# WMHS_MIT_Invy_Circuit_Board.net
KiCad netlist of a schematic drawn in EAGLE
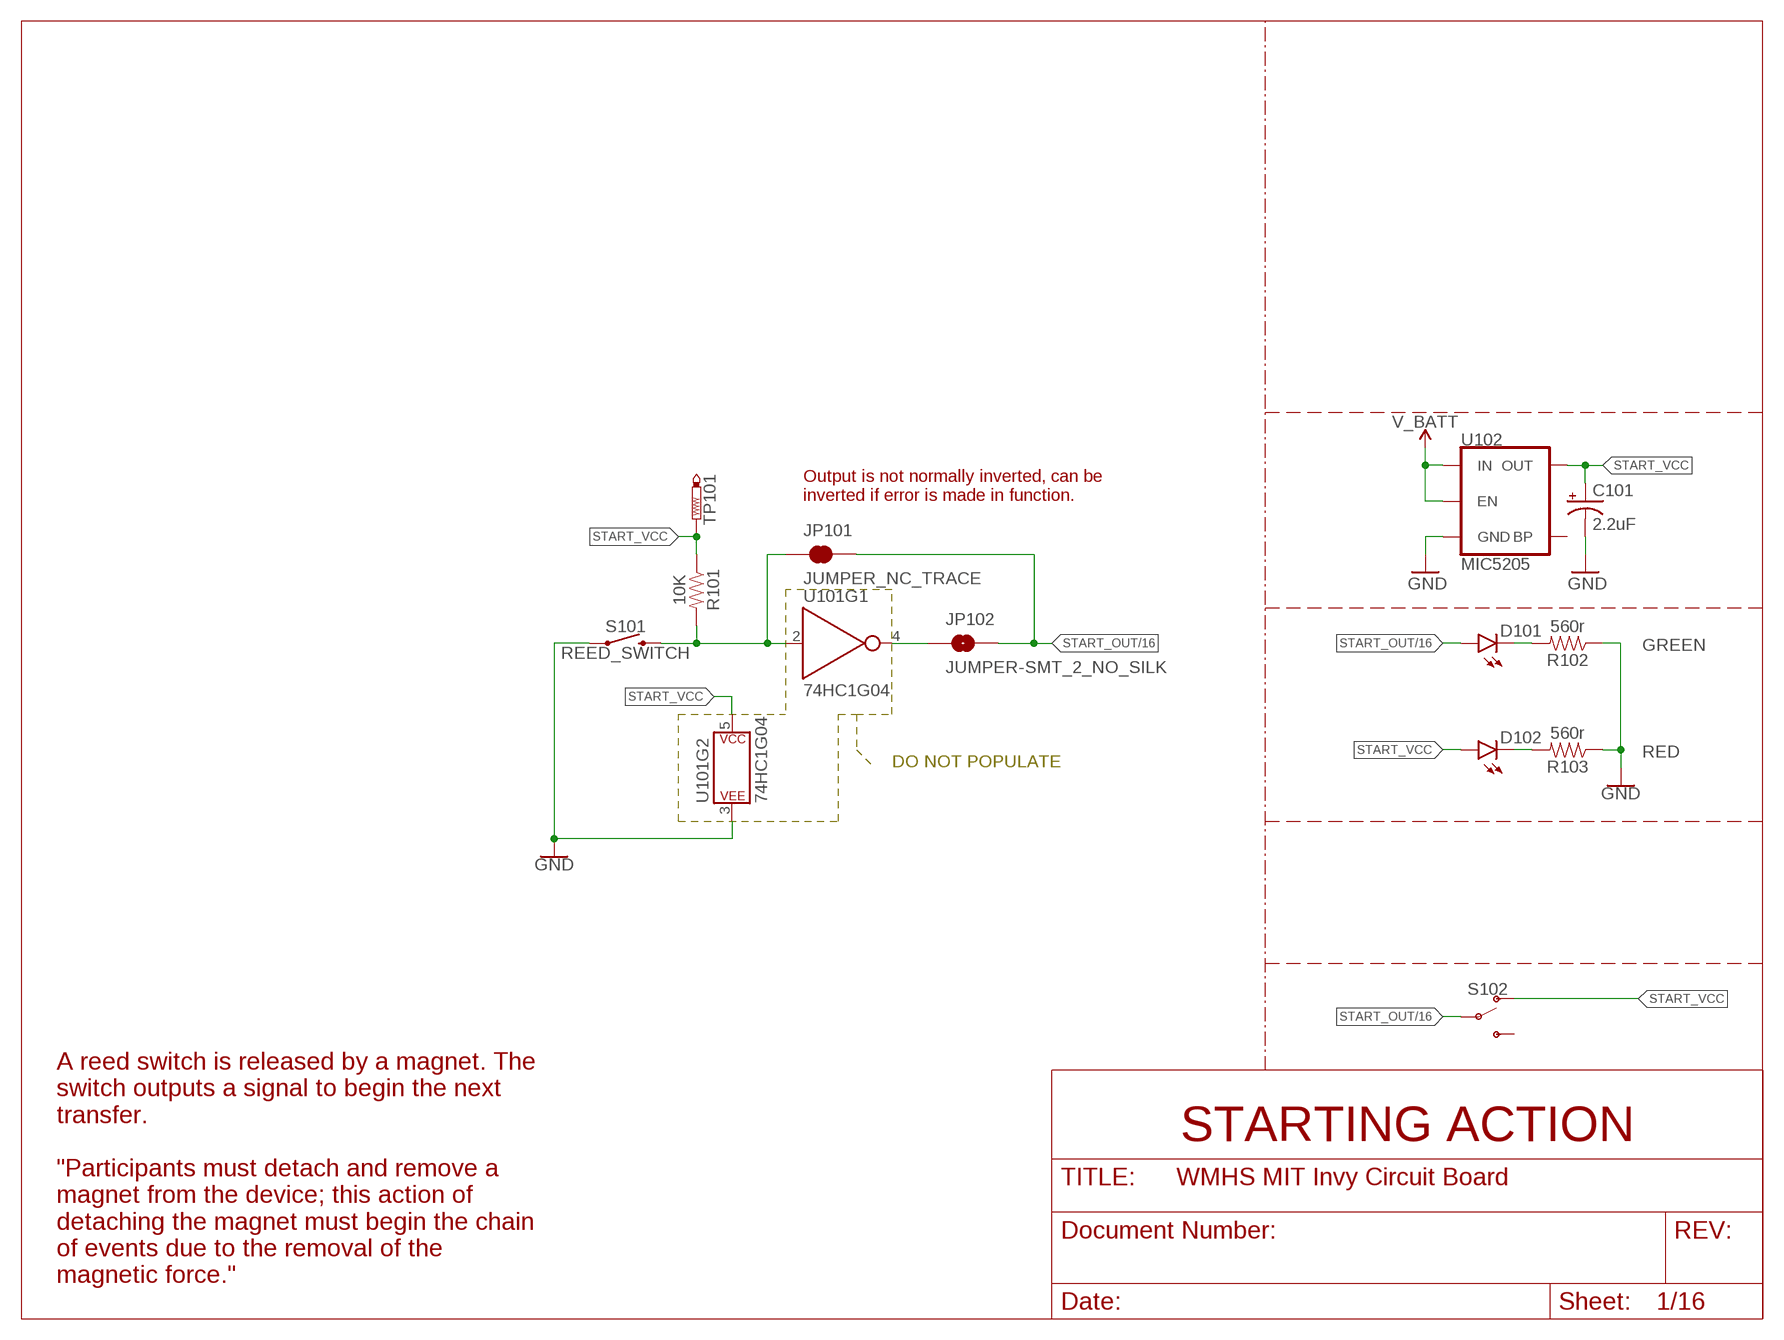
[diagram p0: schematic, sheet 1]
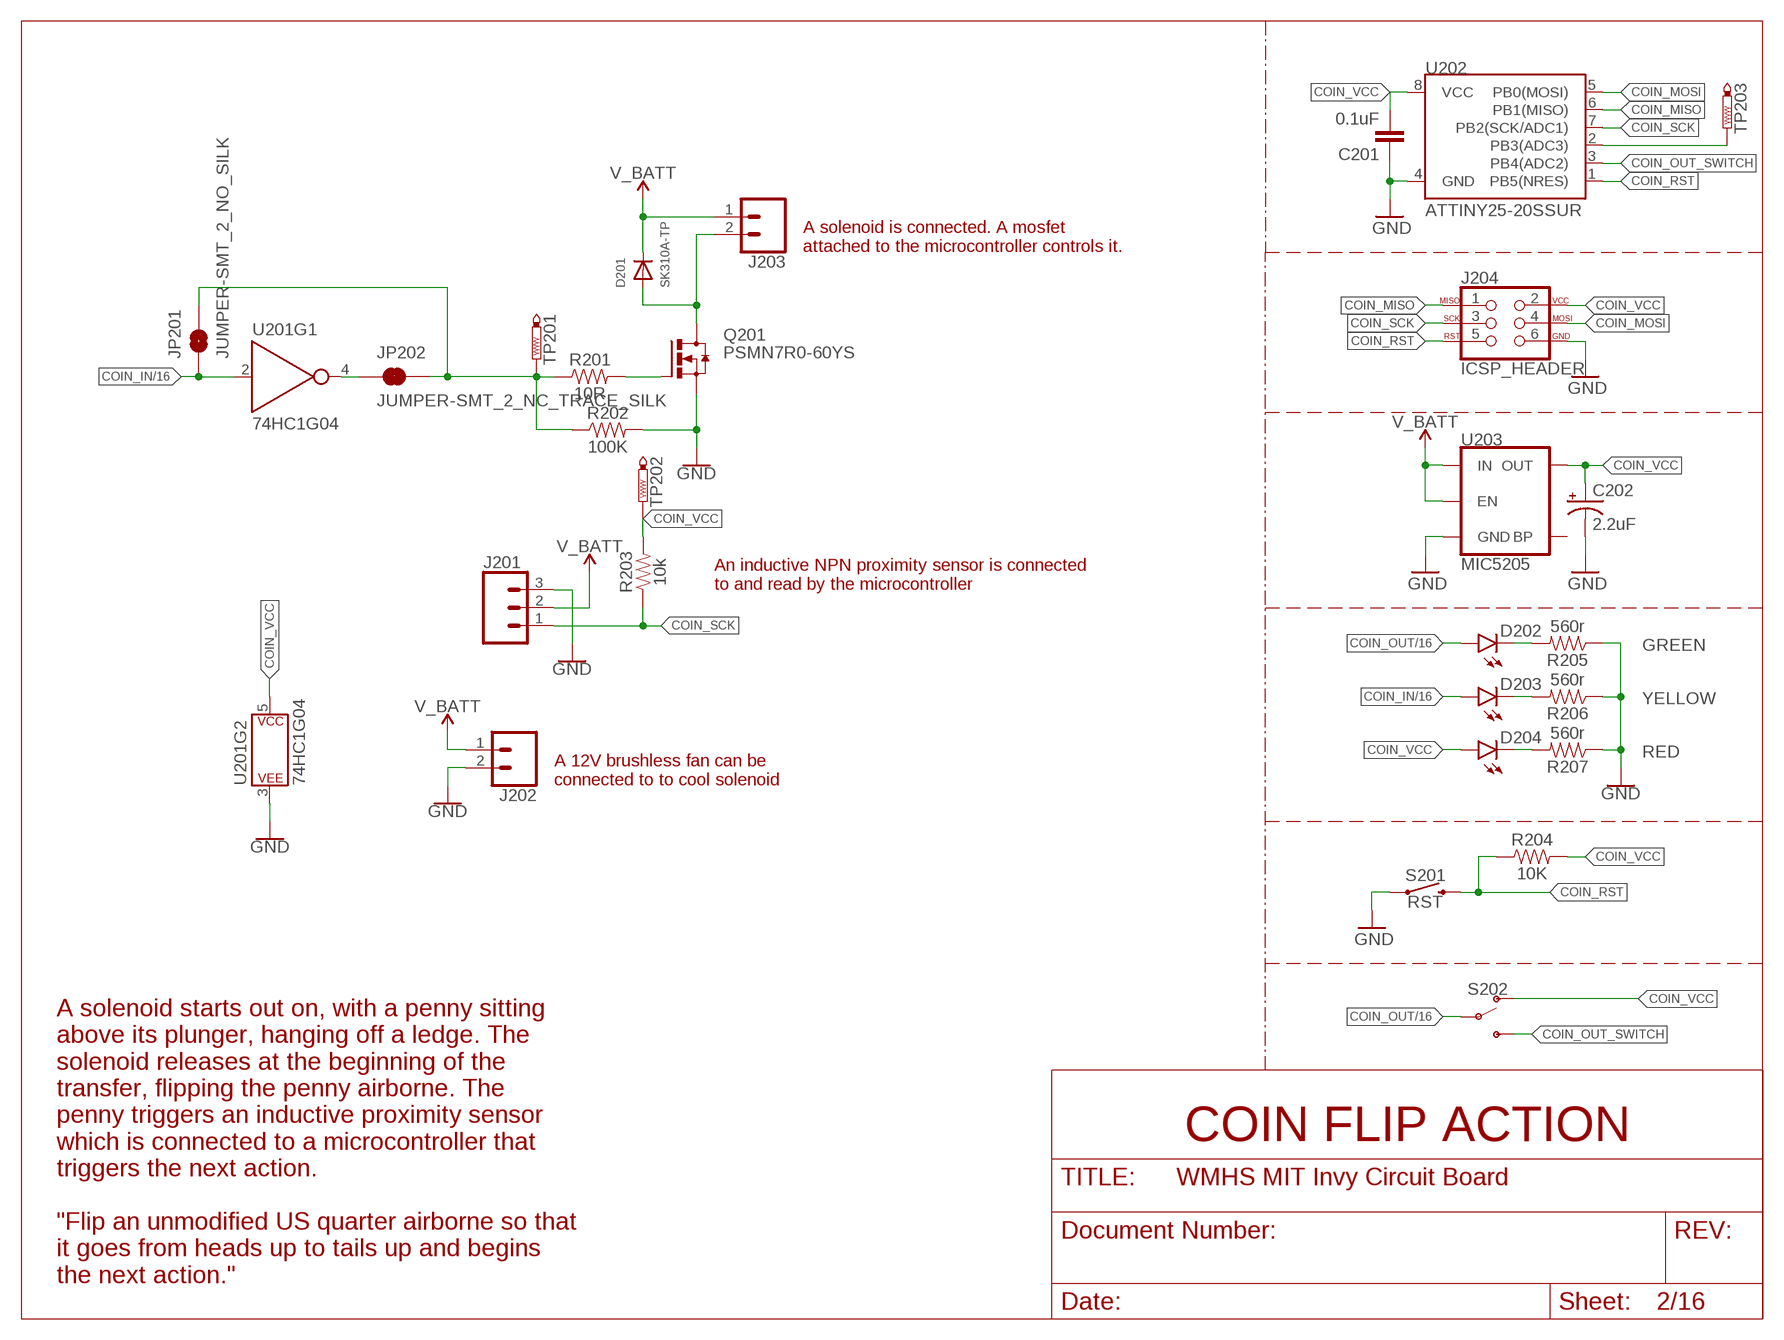
[diagram p1: schematic, sheet 2]
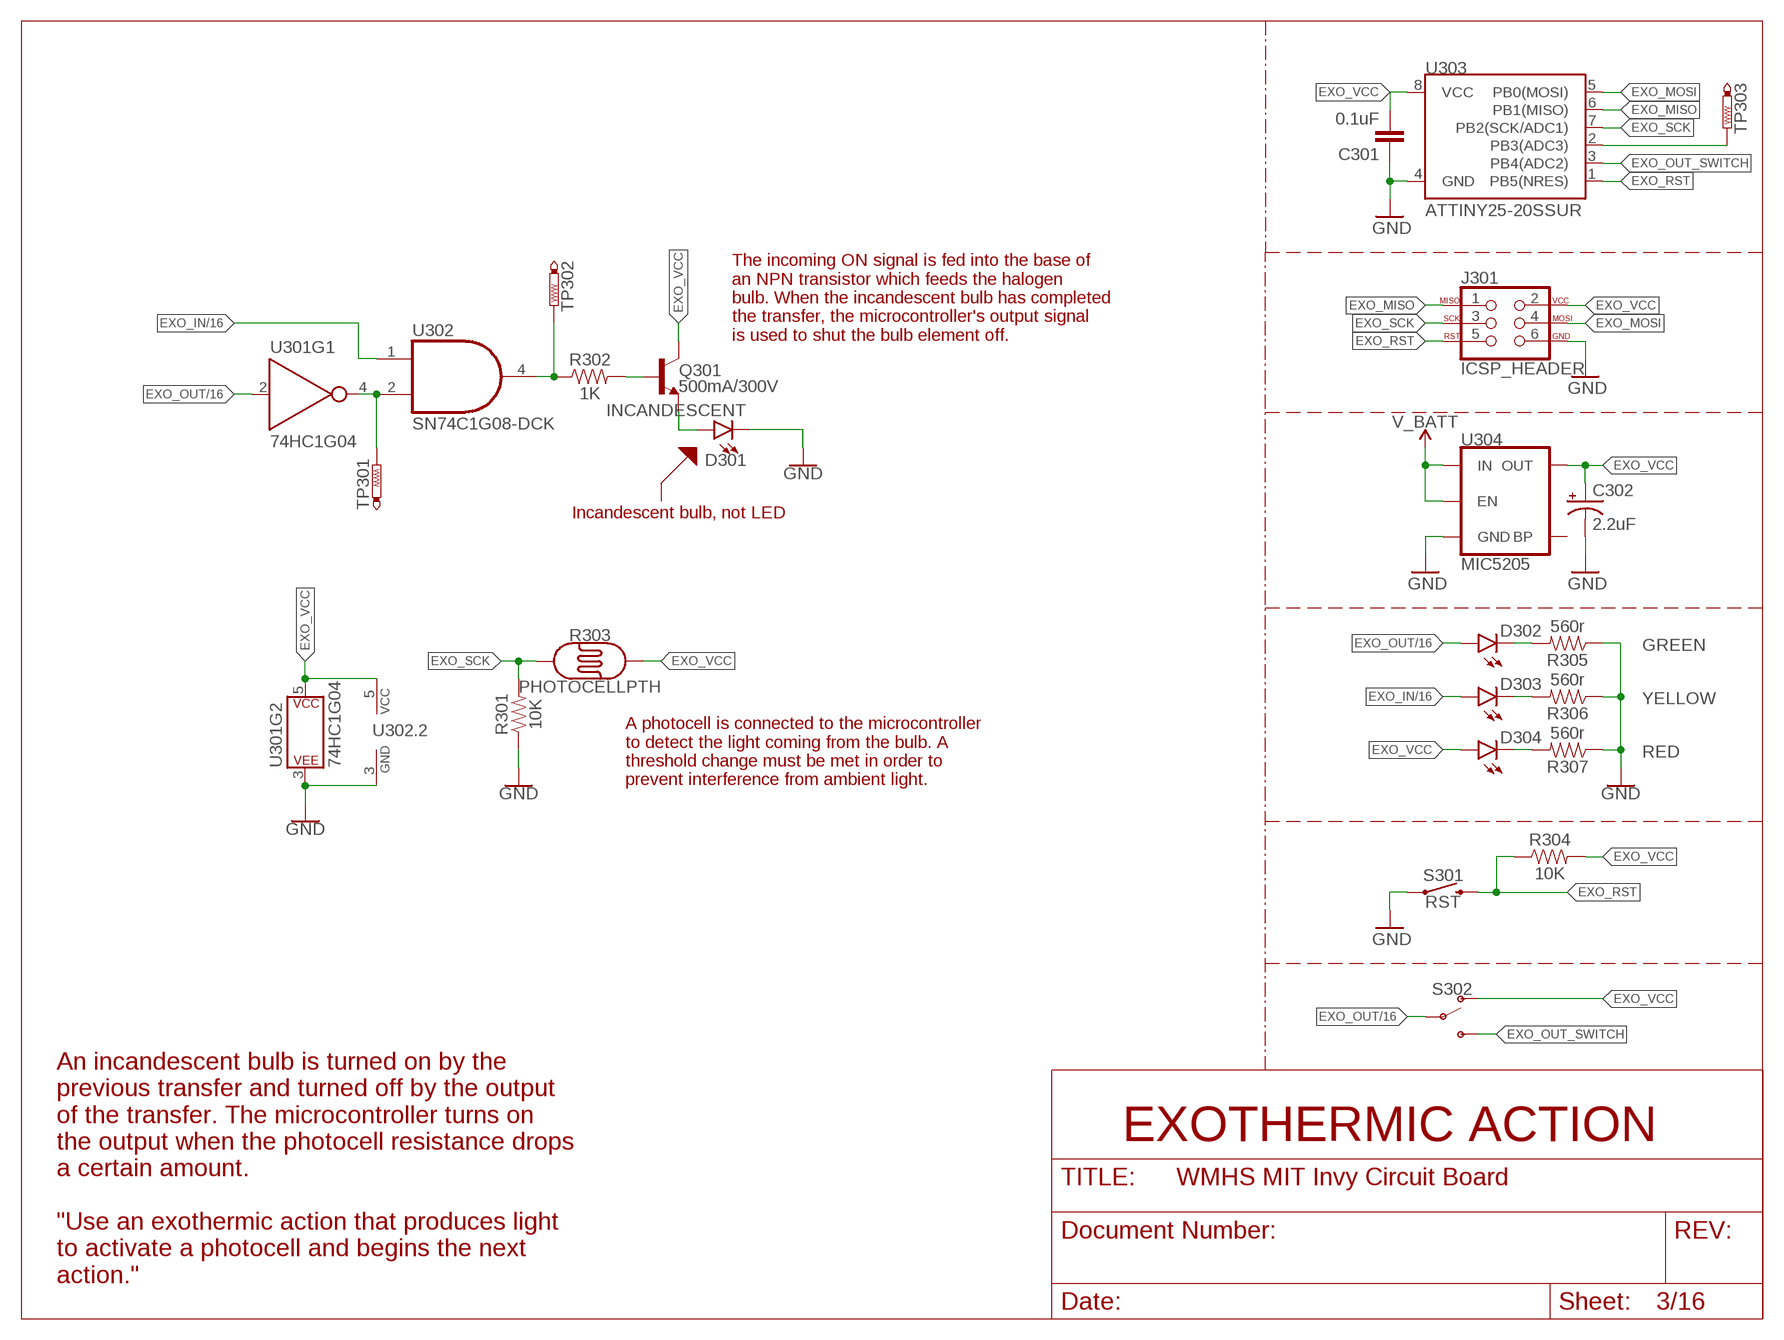
[diagram p2: schematic, sheet 3]
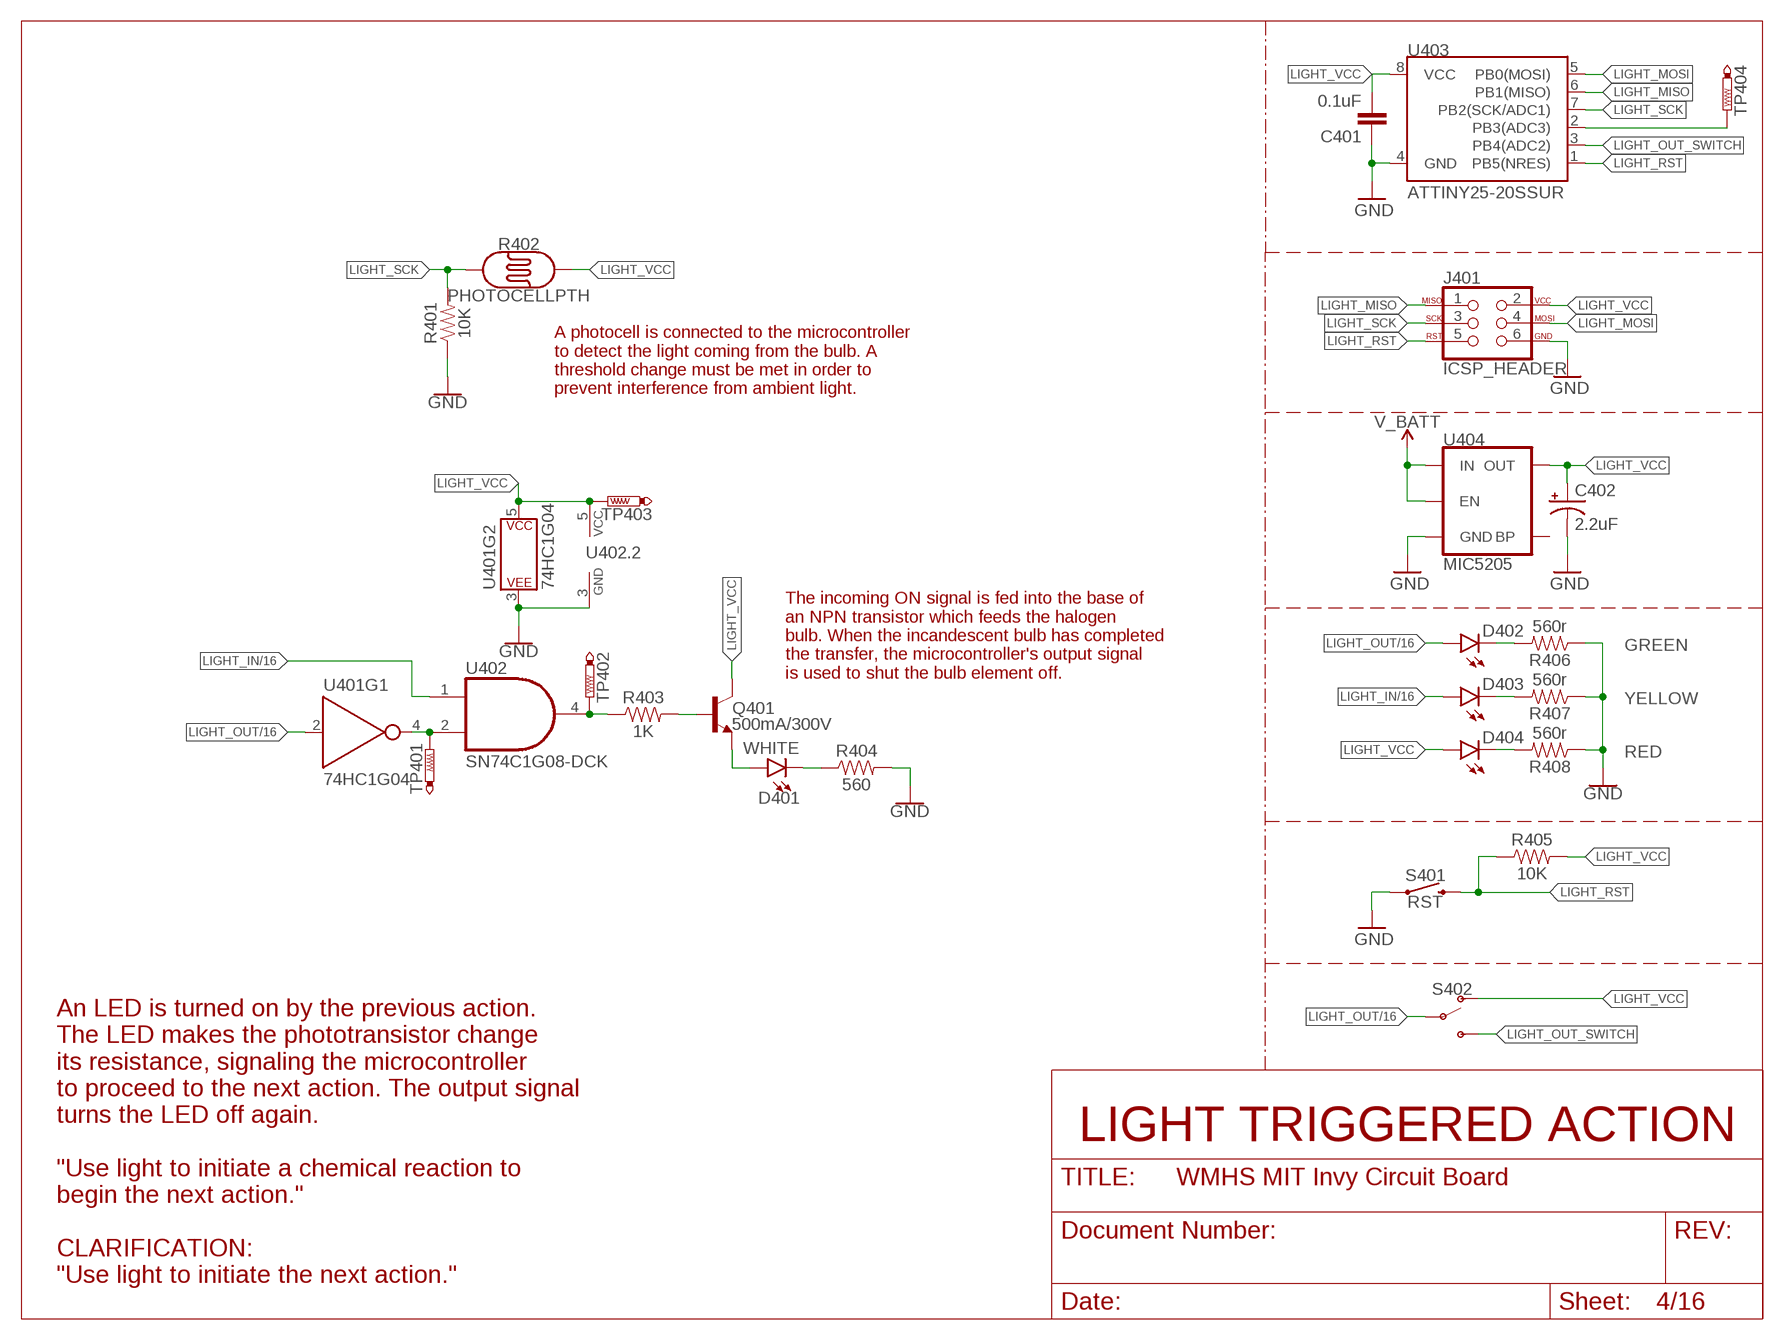
[diagram p3: schematic, sheet 4]
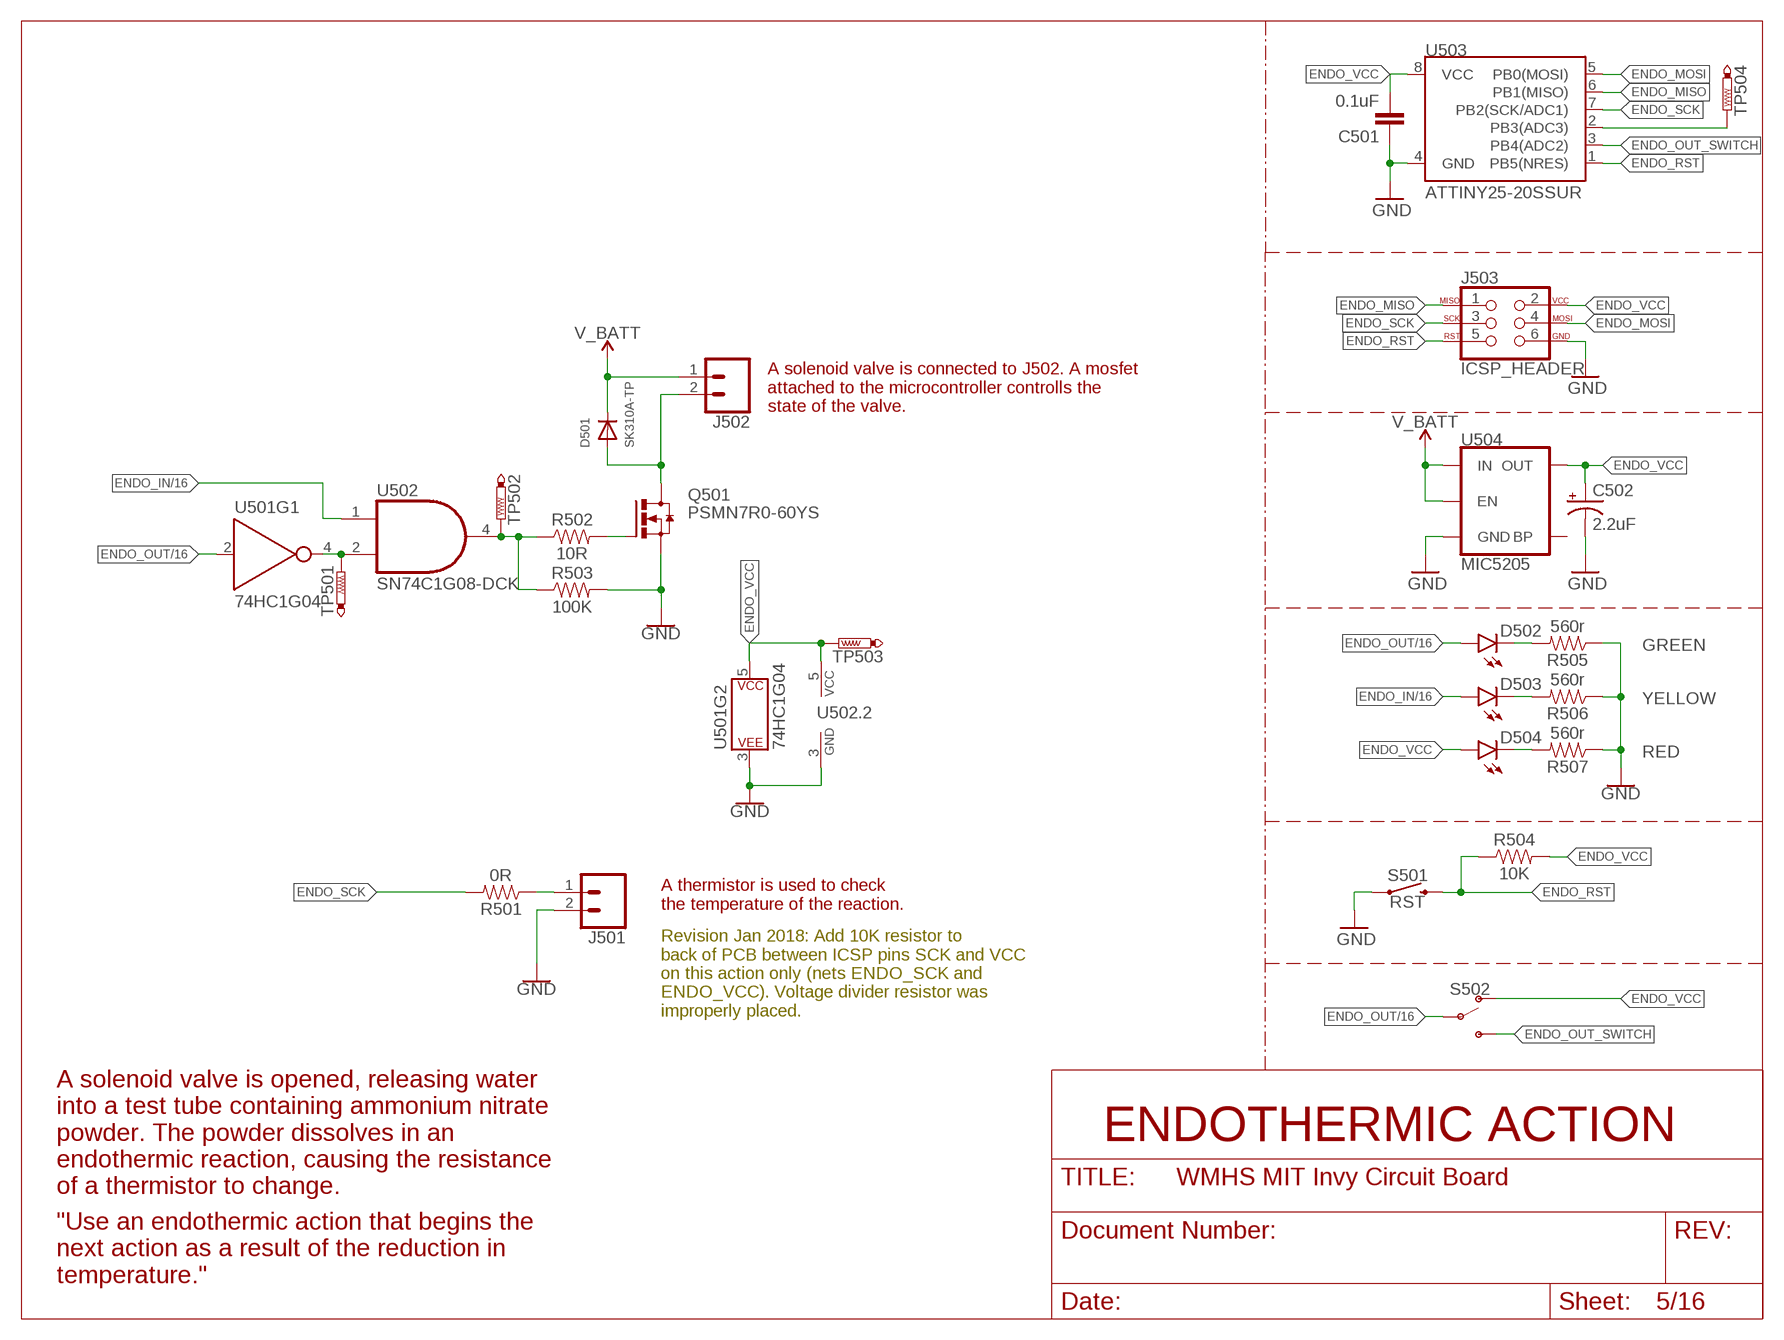
[diagram p4: schematic, sheet 5]
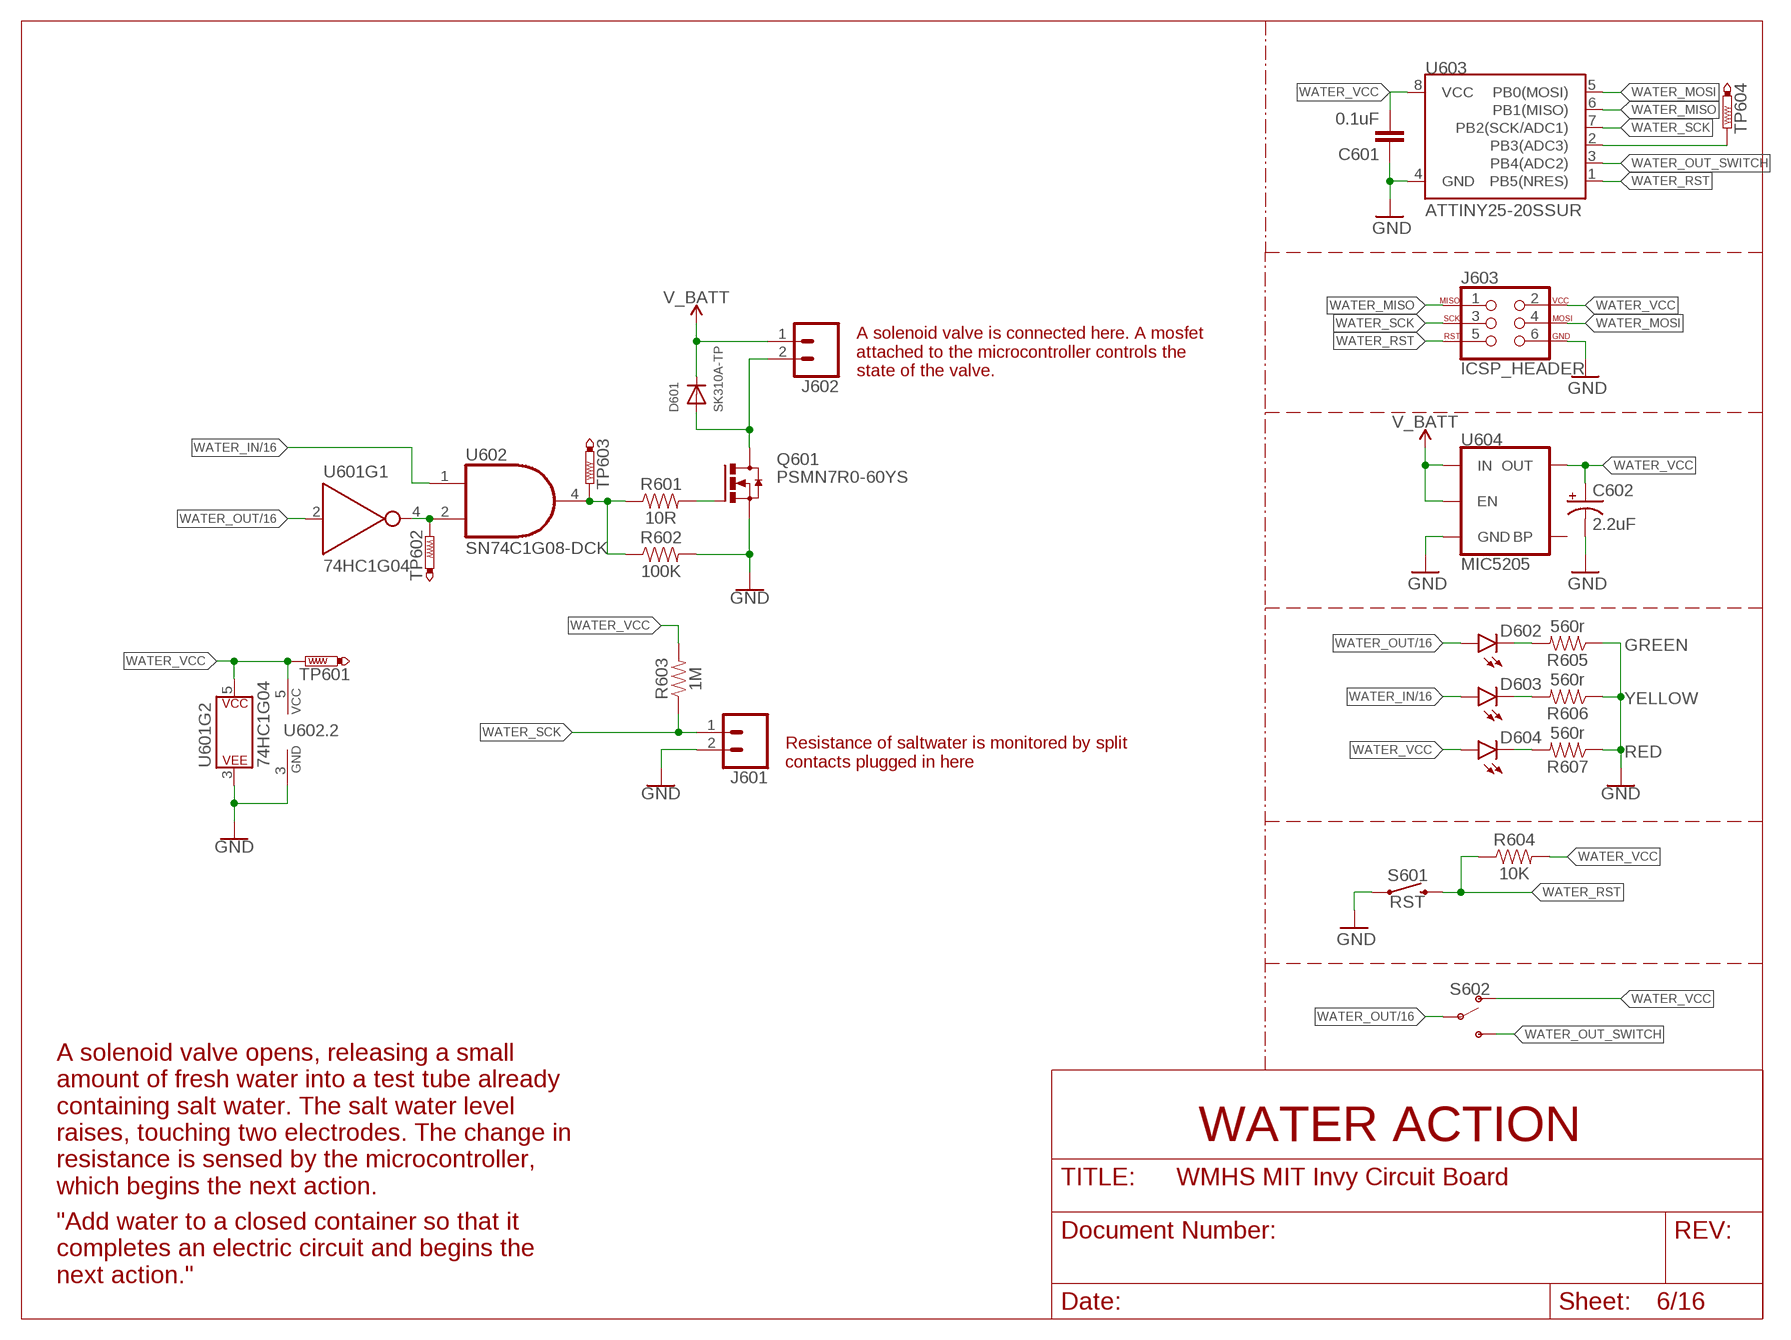
[diagram p5: schematic, sheet 6]
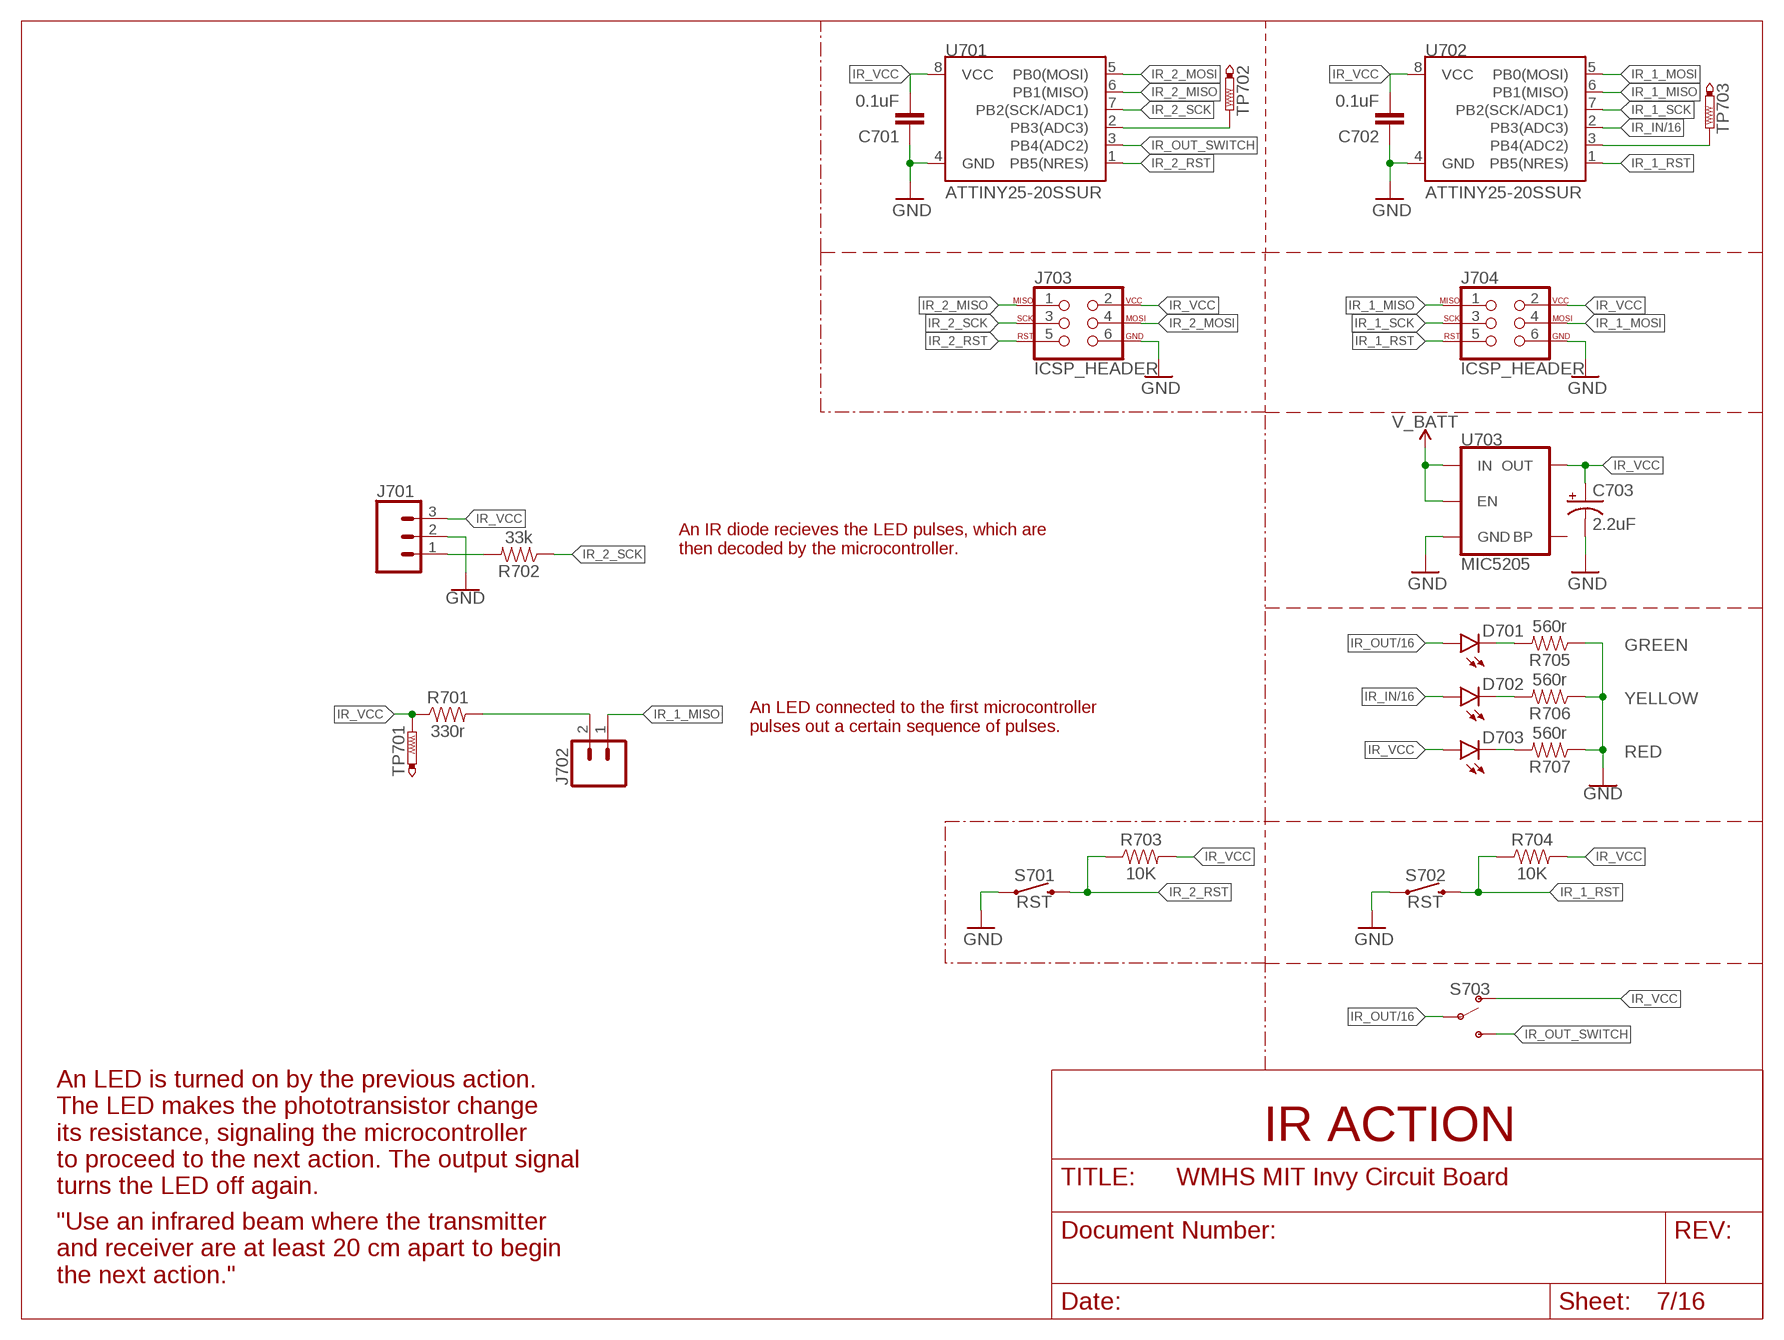
[diagram p6: schematic, sheet 7]
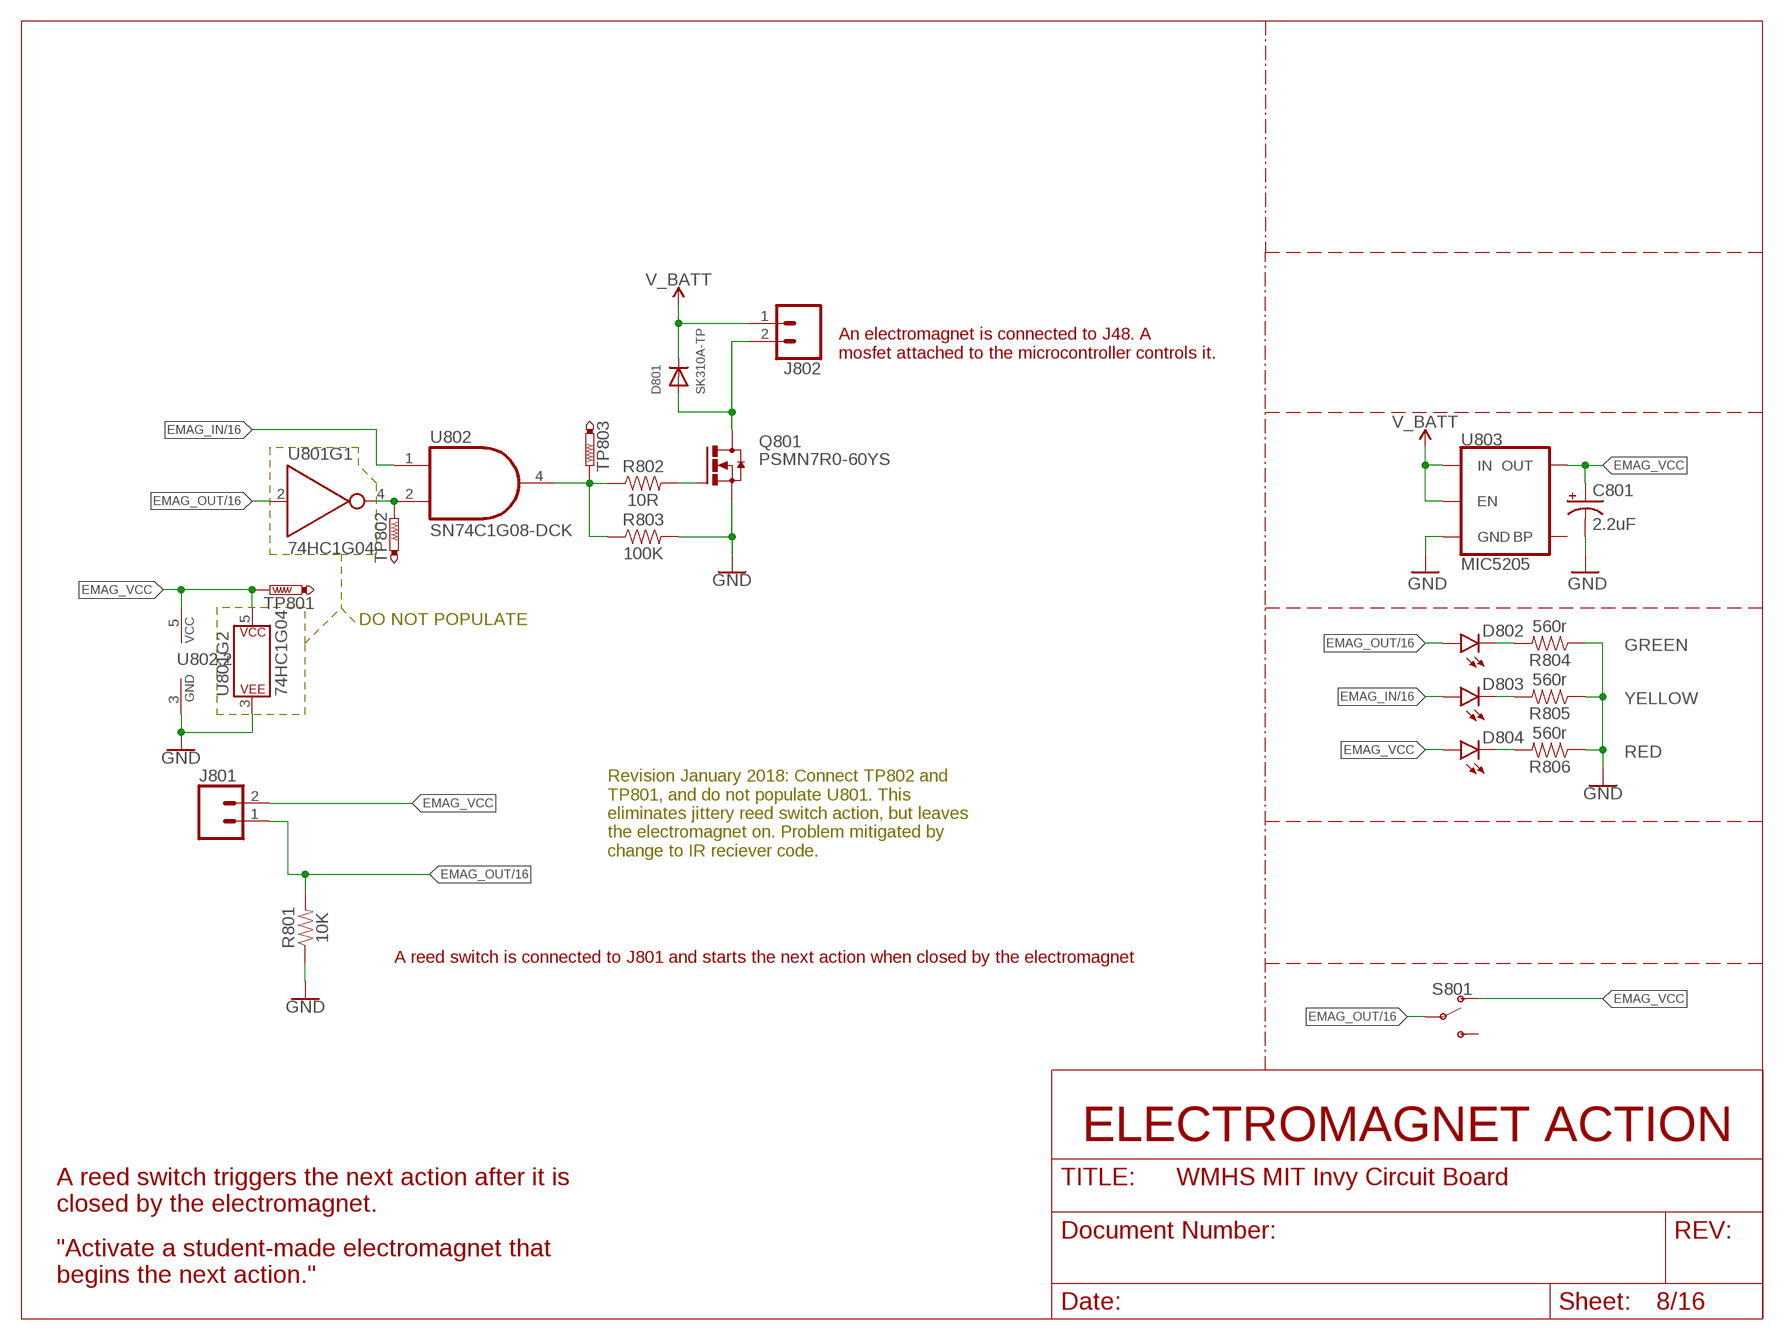
[diagram p7: schematic, sheet 8]
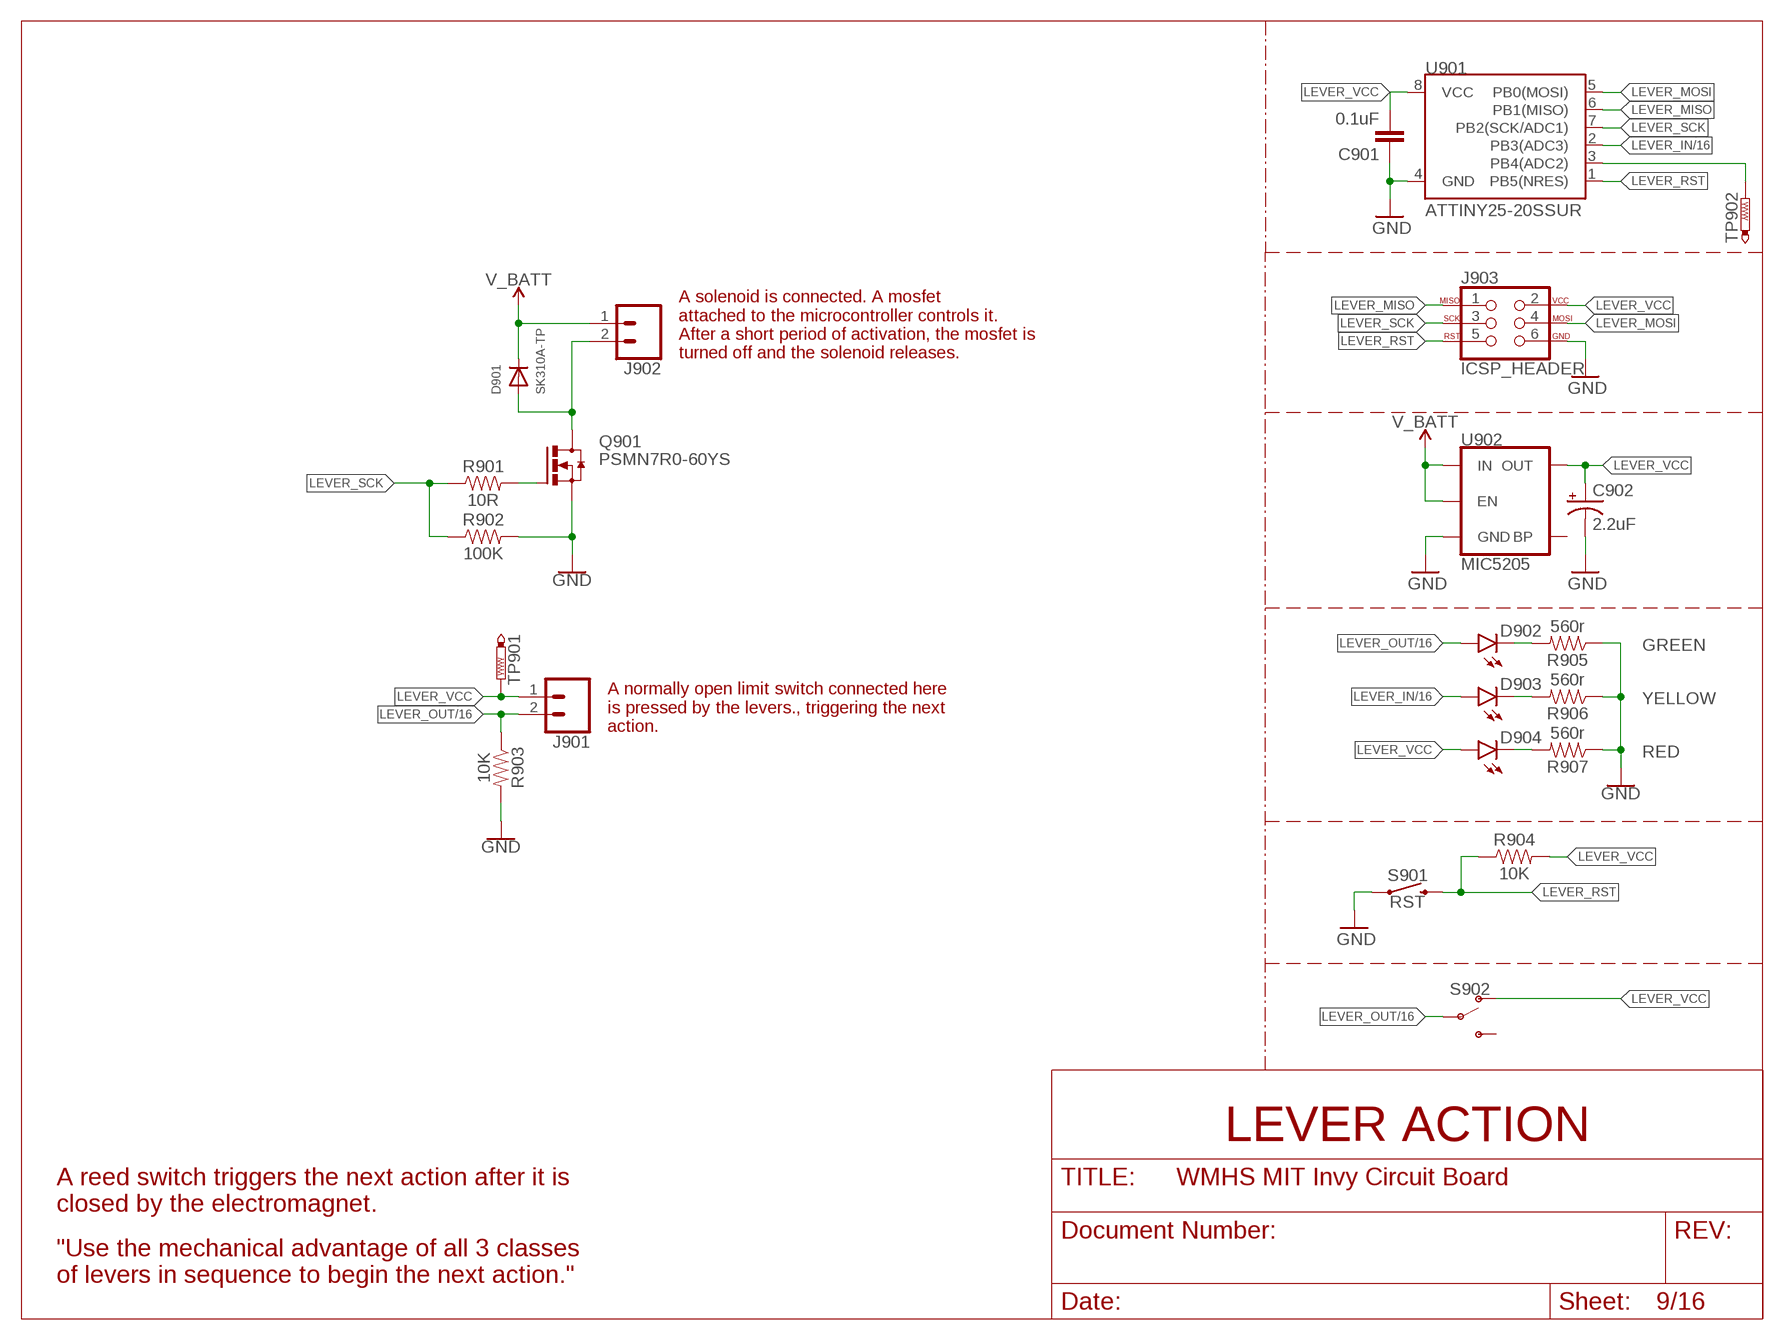
[diagram p8: schematic, sheet 9]
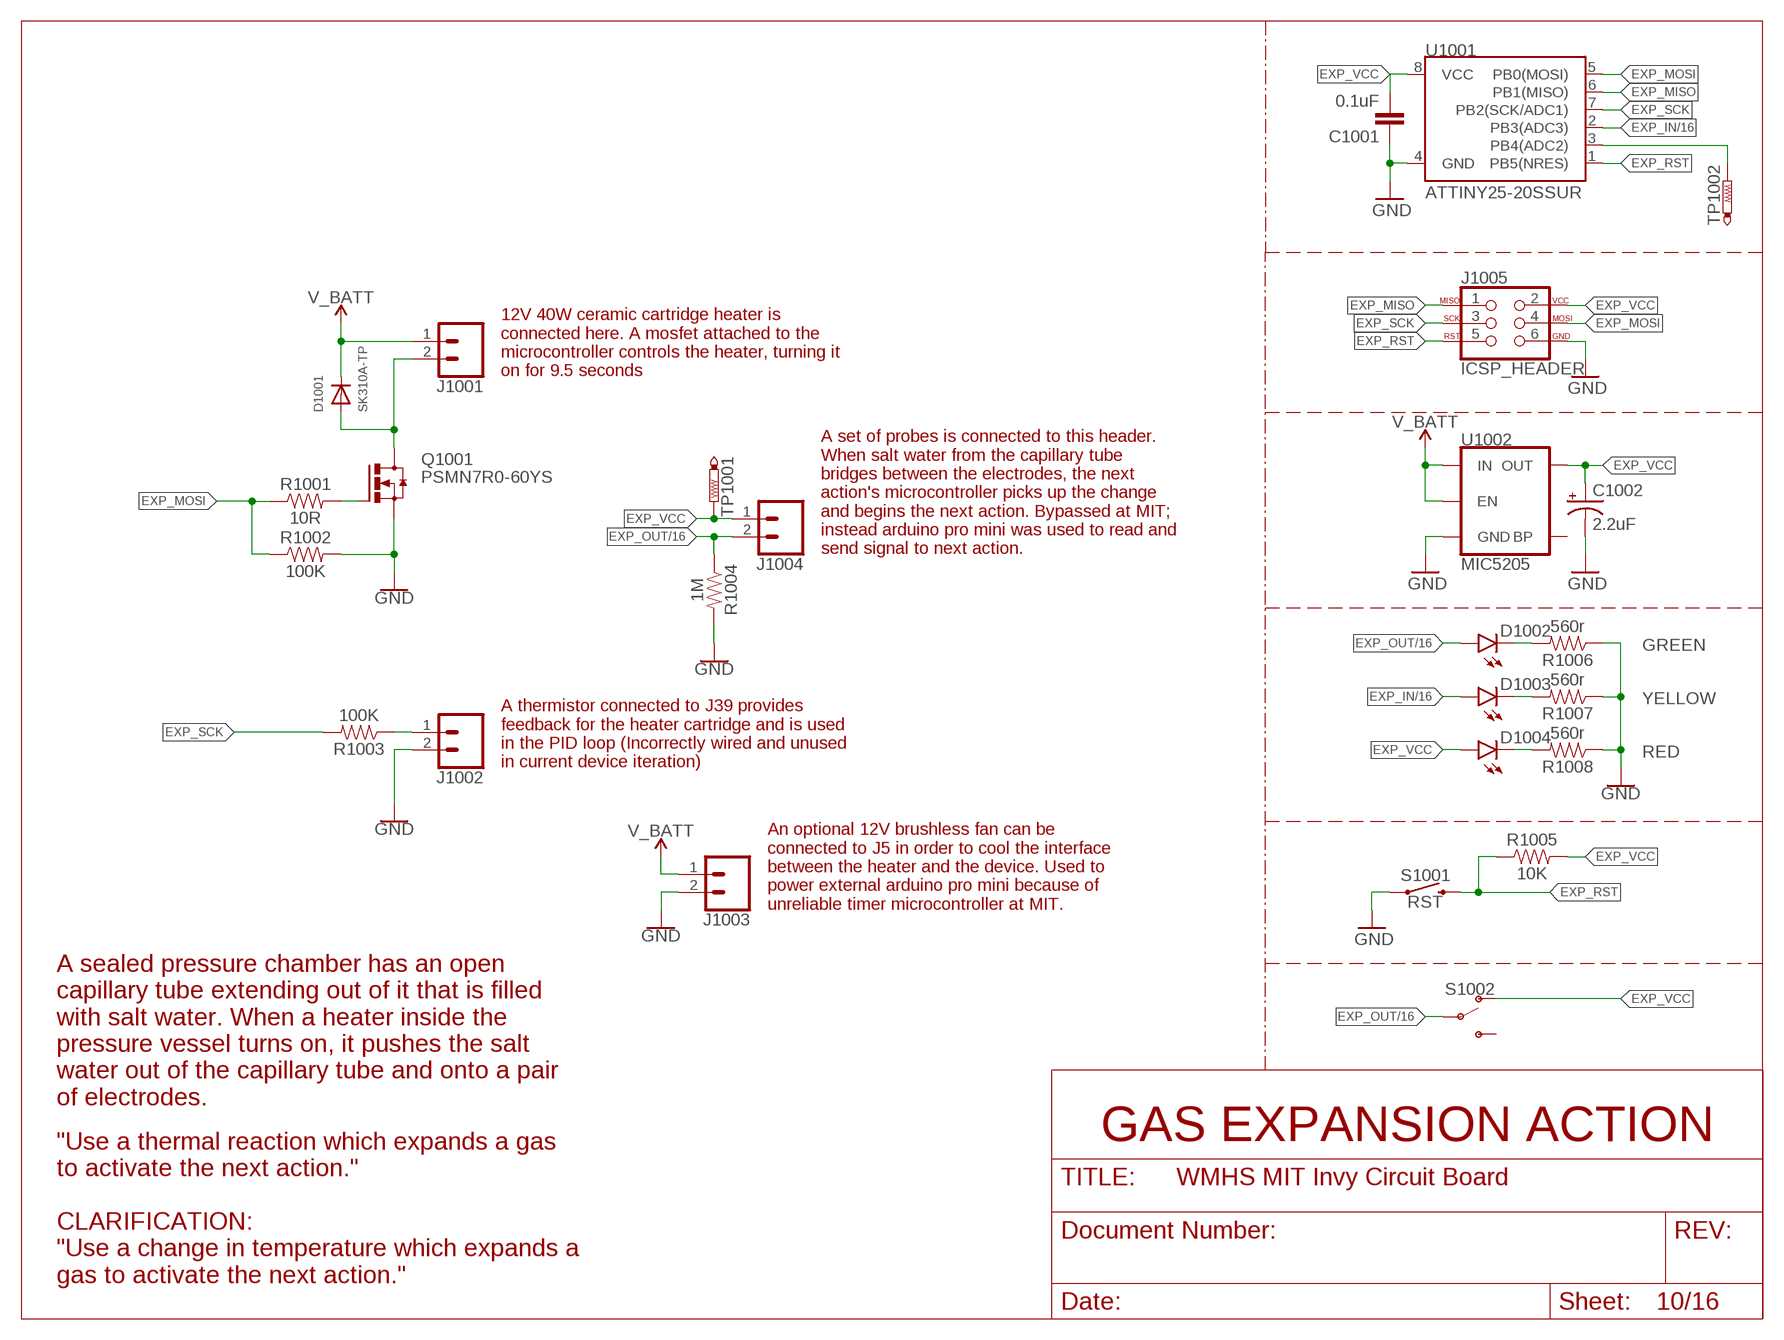
[diagram p9: schematic, sheet 10]
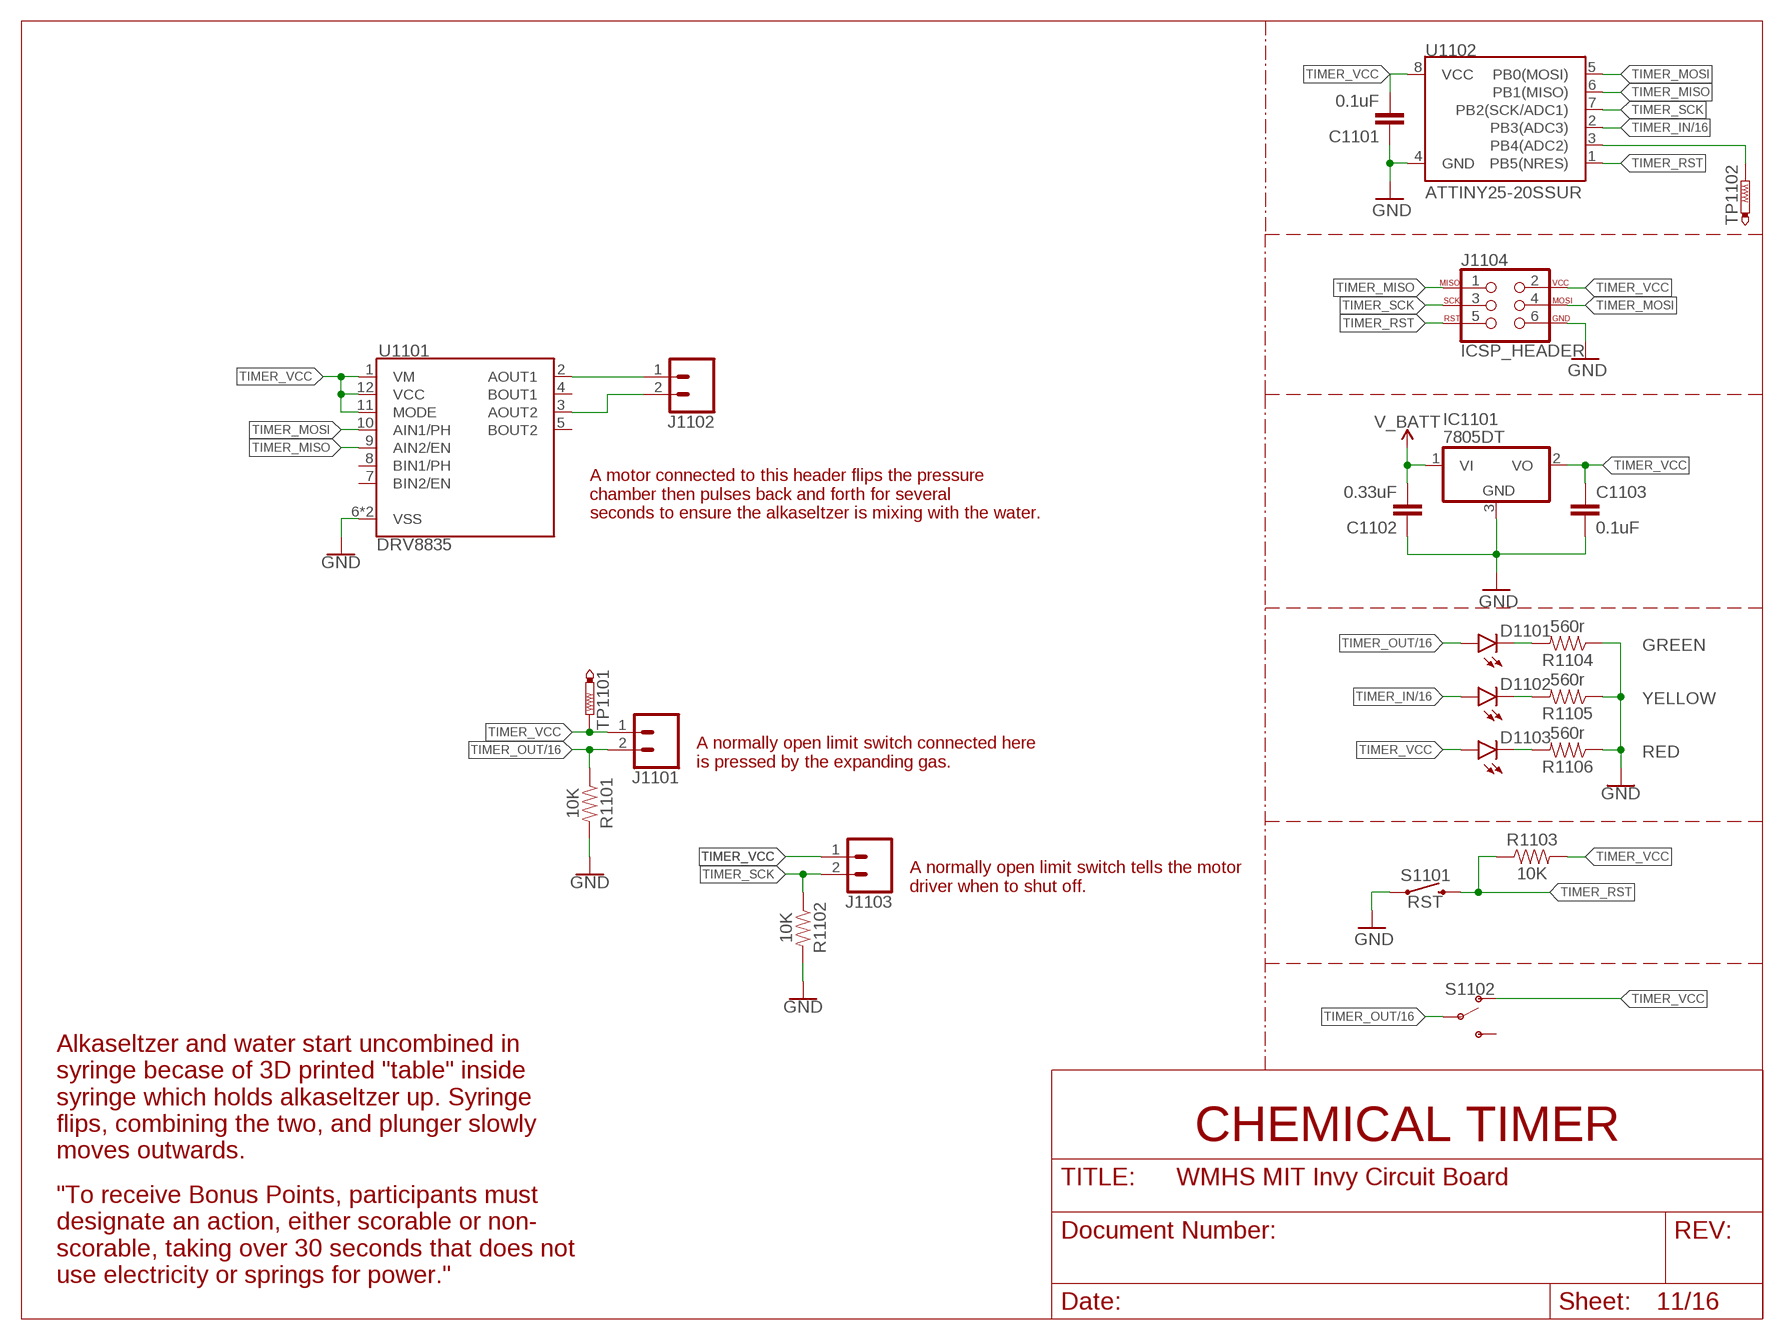
[diagram p10: schematic, sheet 11]
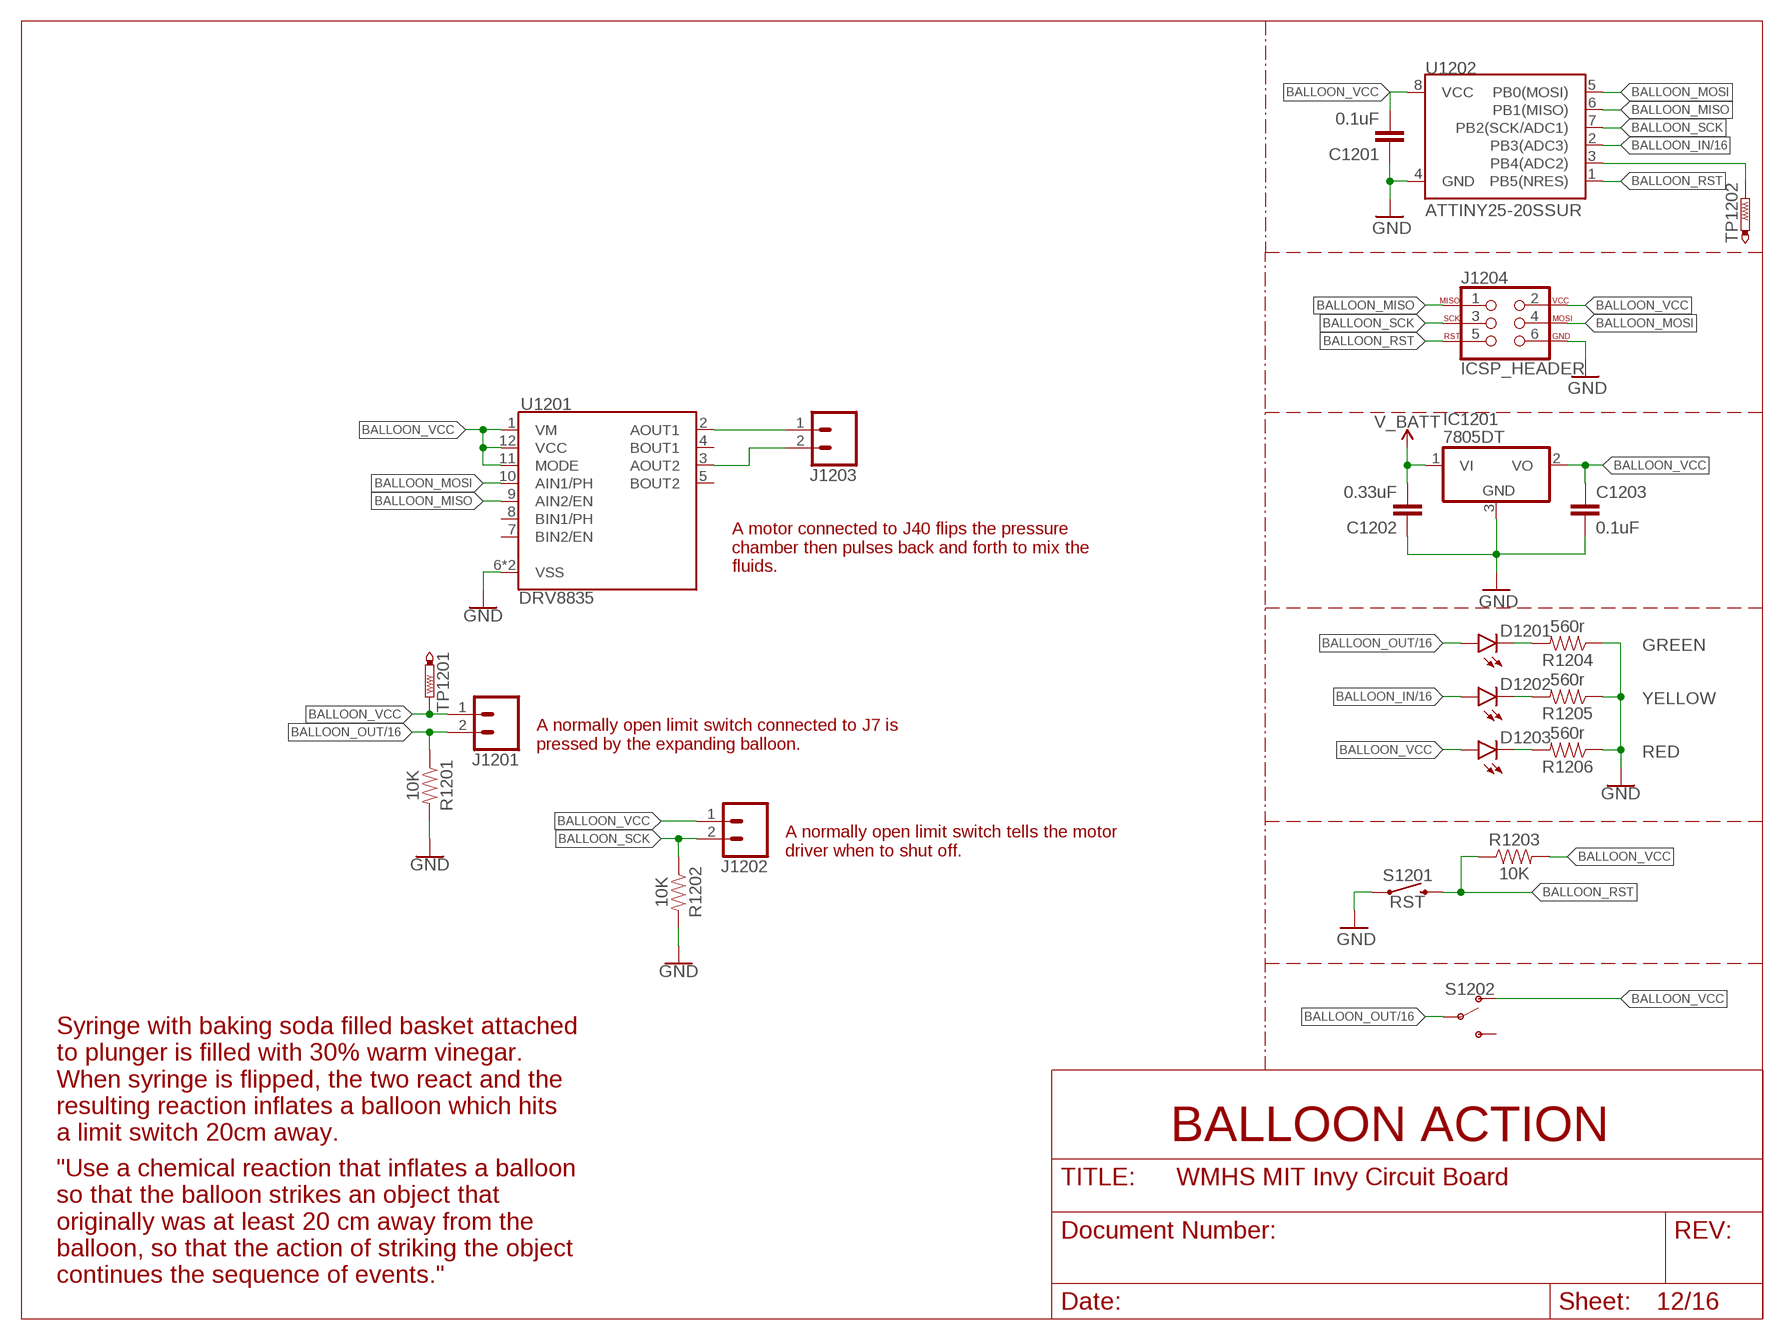
[diagram p11: schematic, sheet 12]
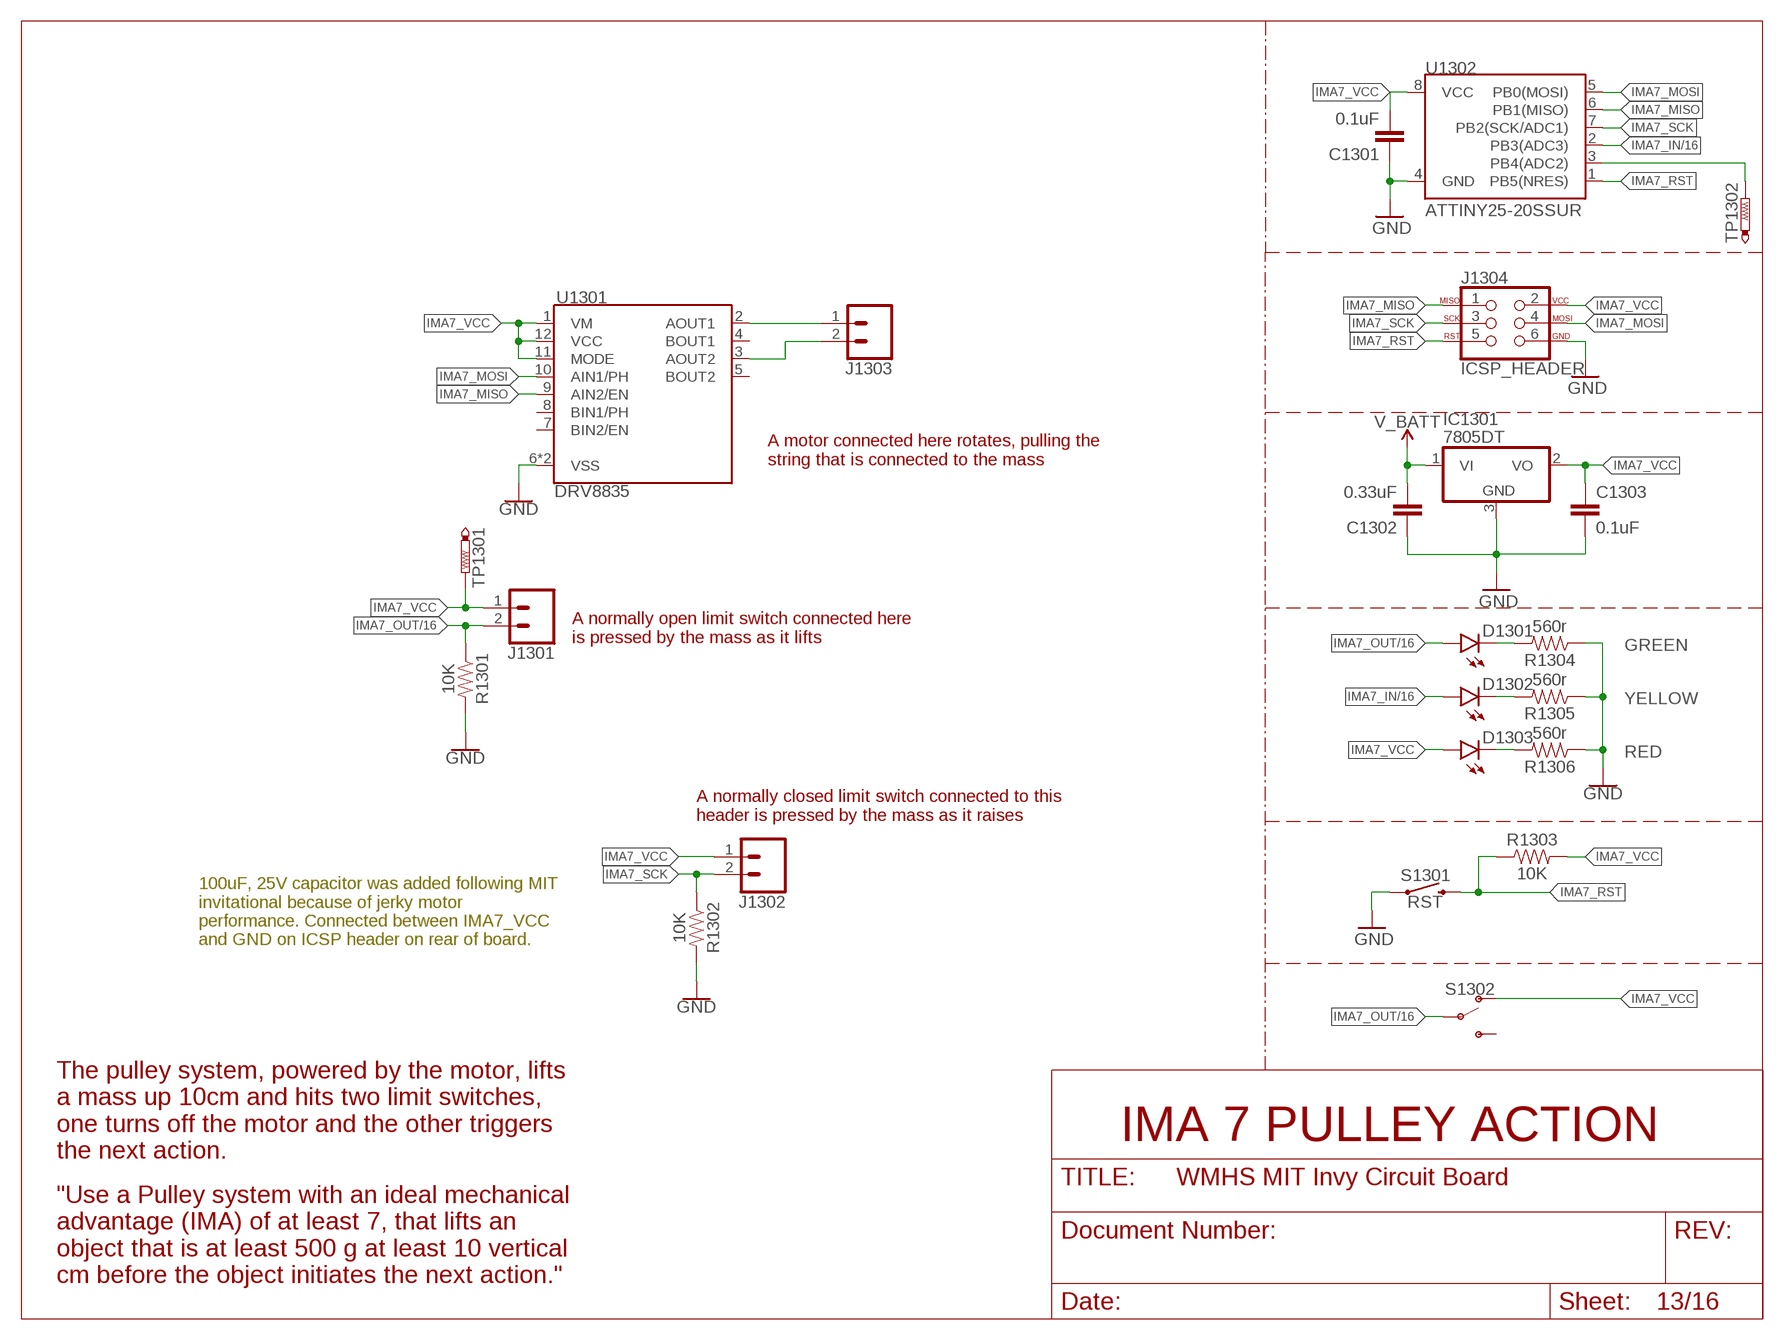
[diagram p12: schematic, sheet 13]
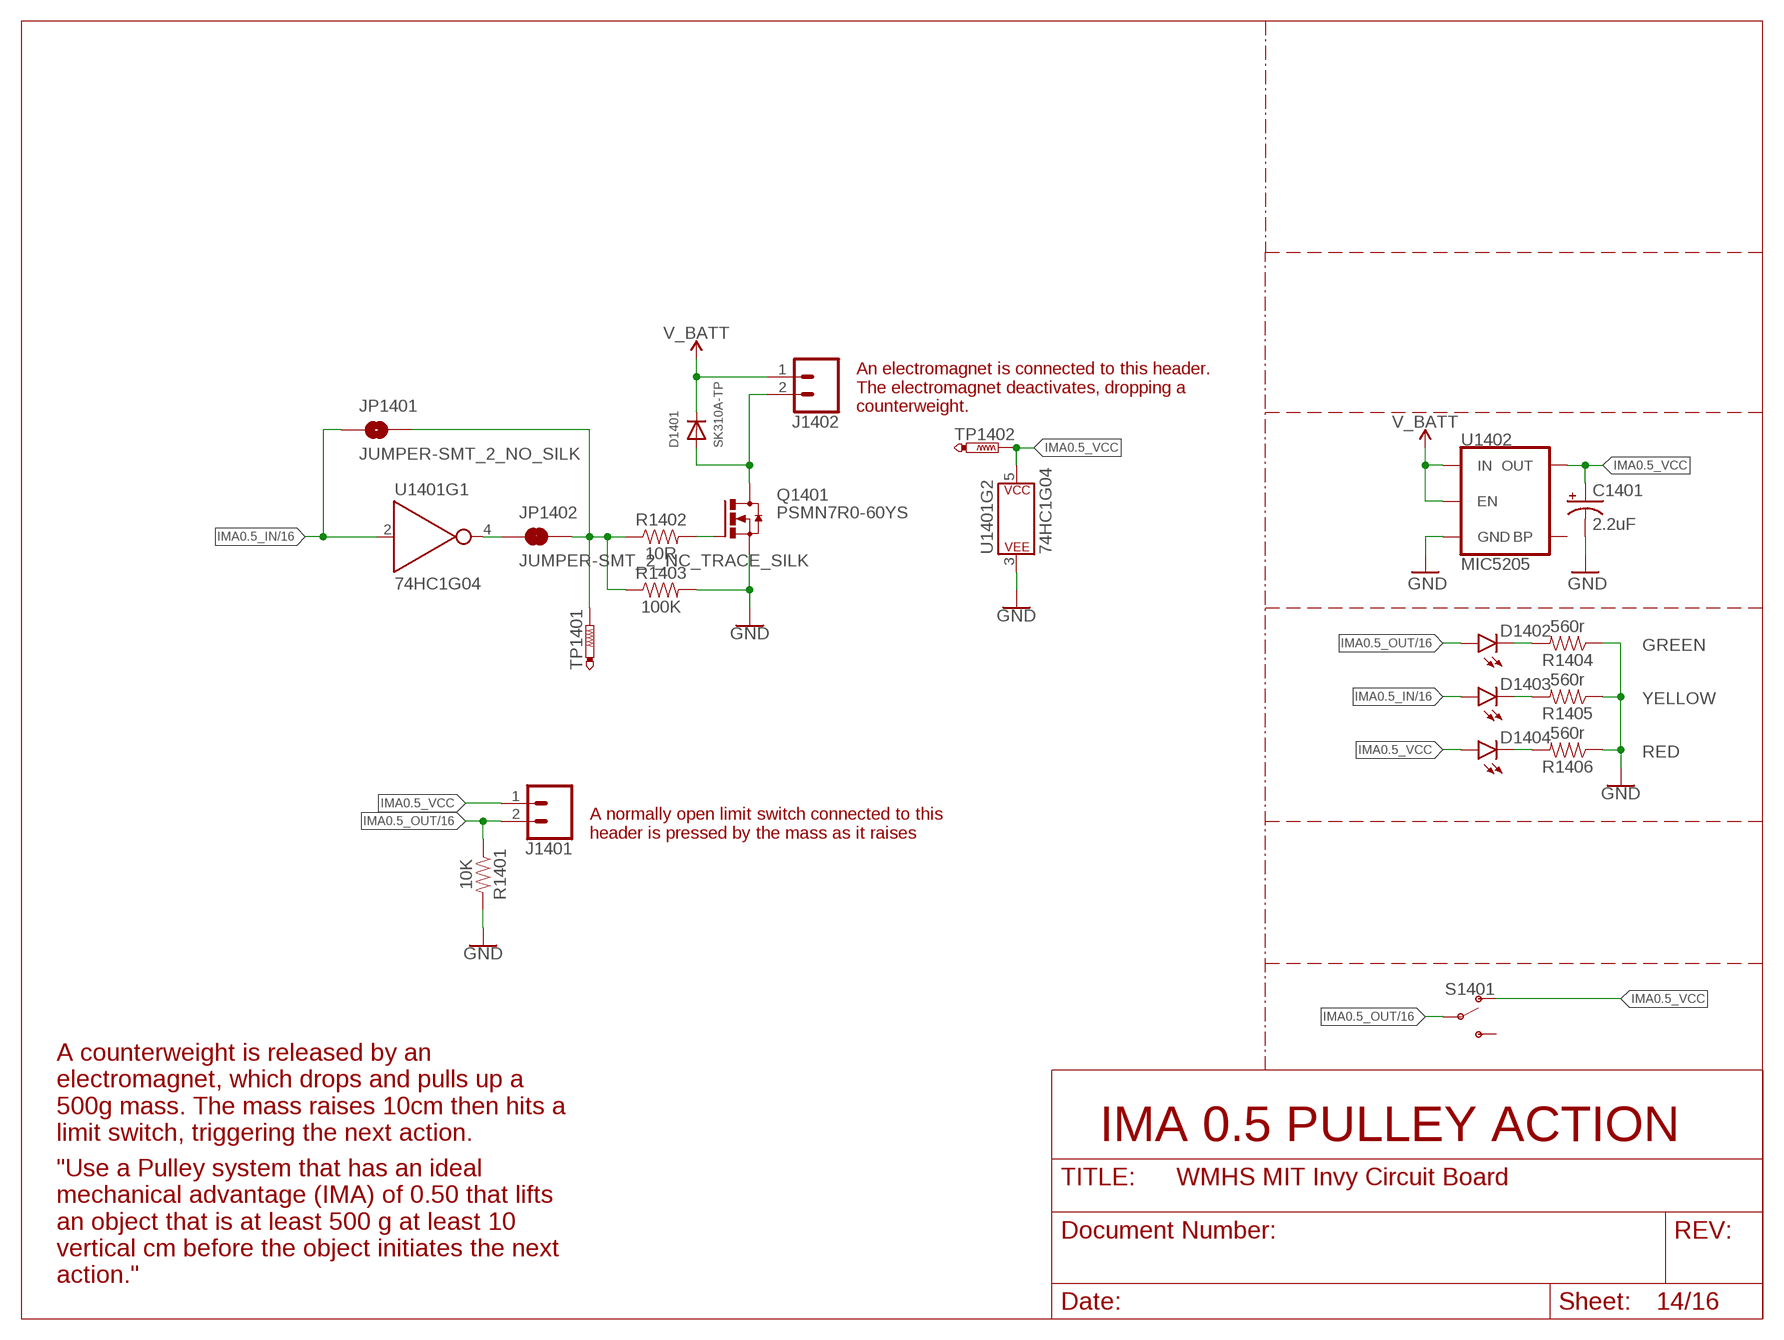
[diagram p13: schematic, sheet 14]
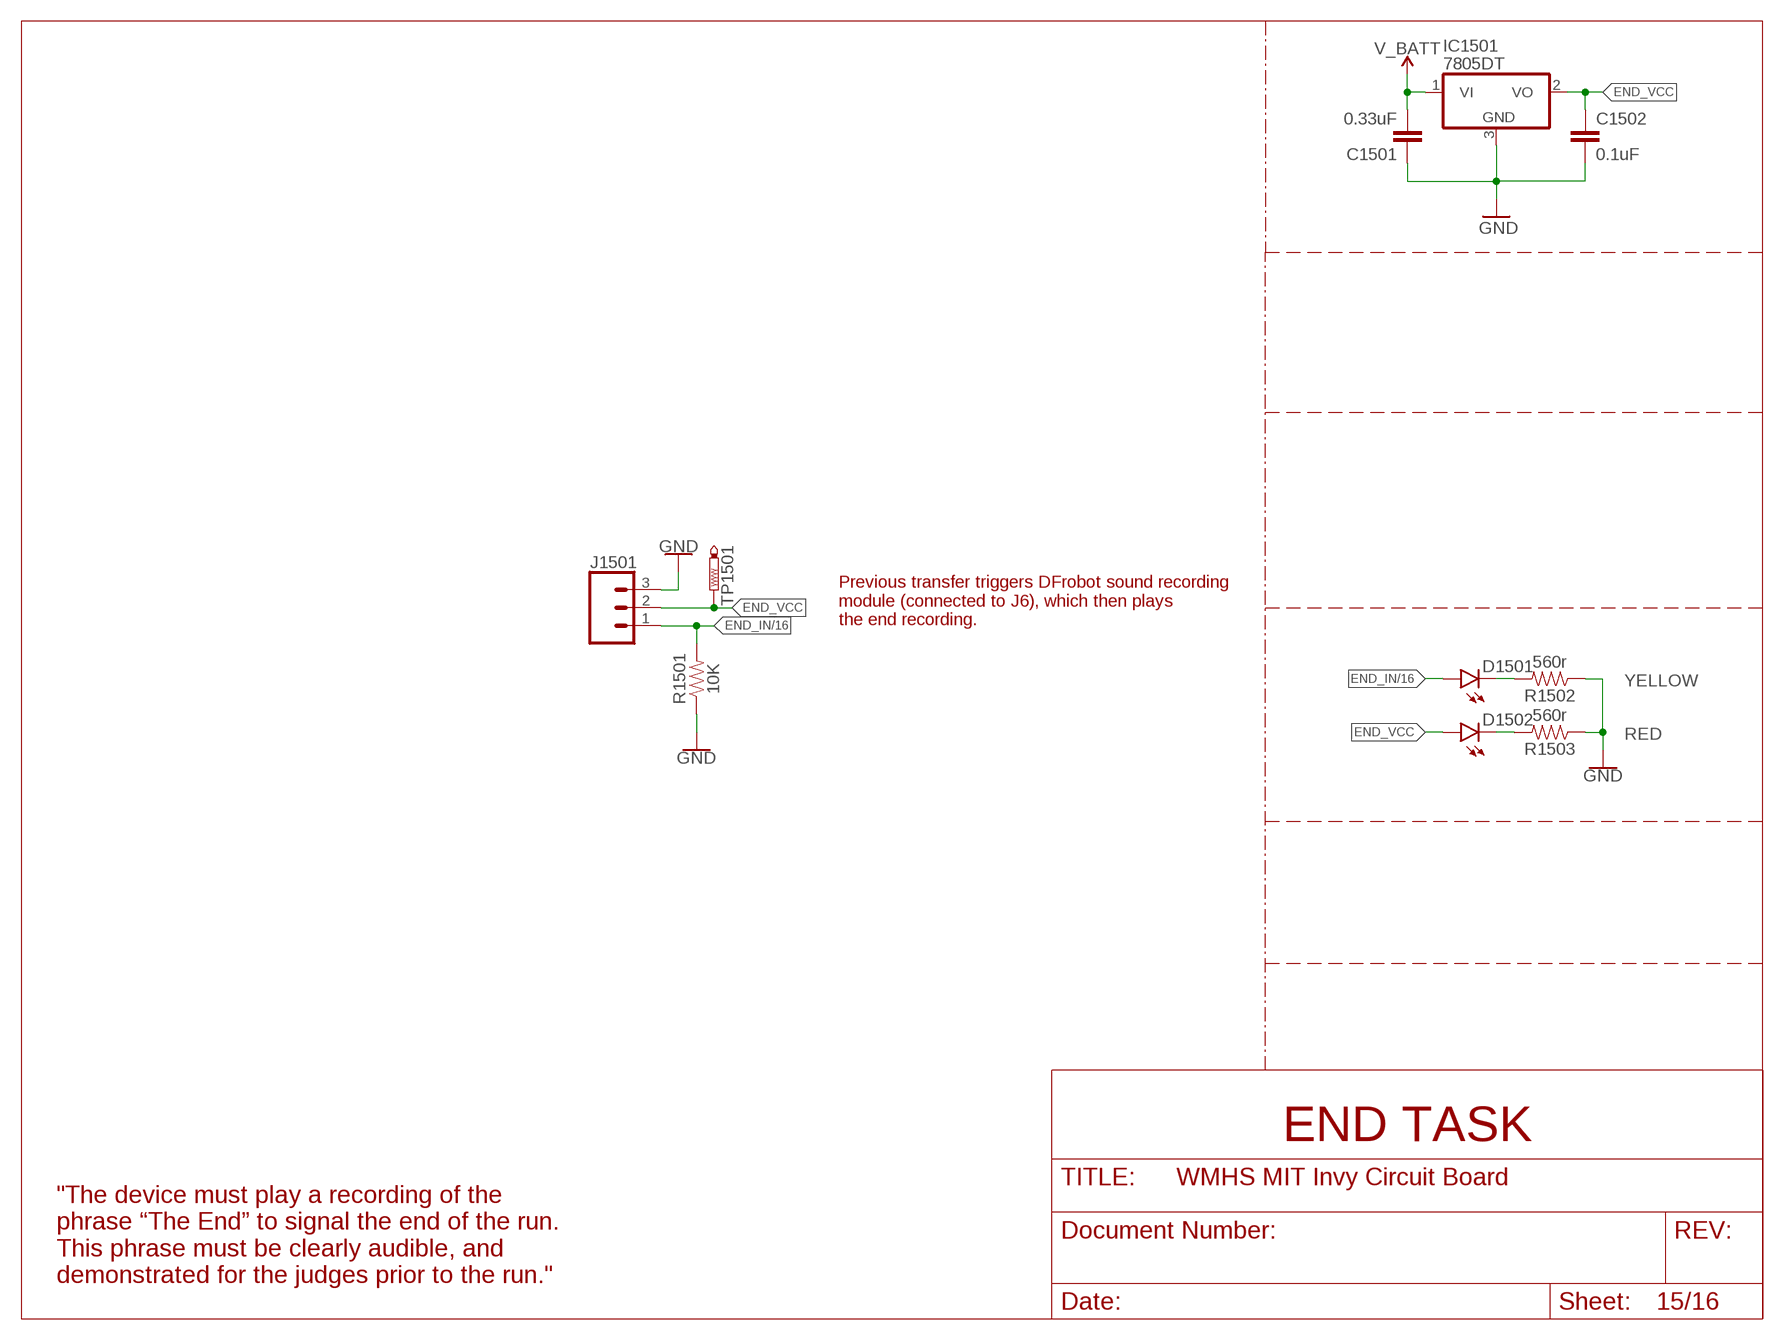
[diagram p14: schematic, sheet 15]
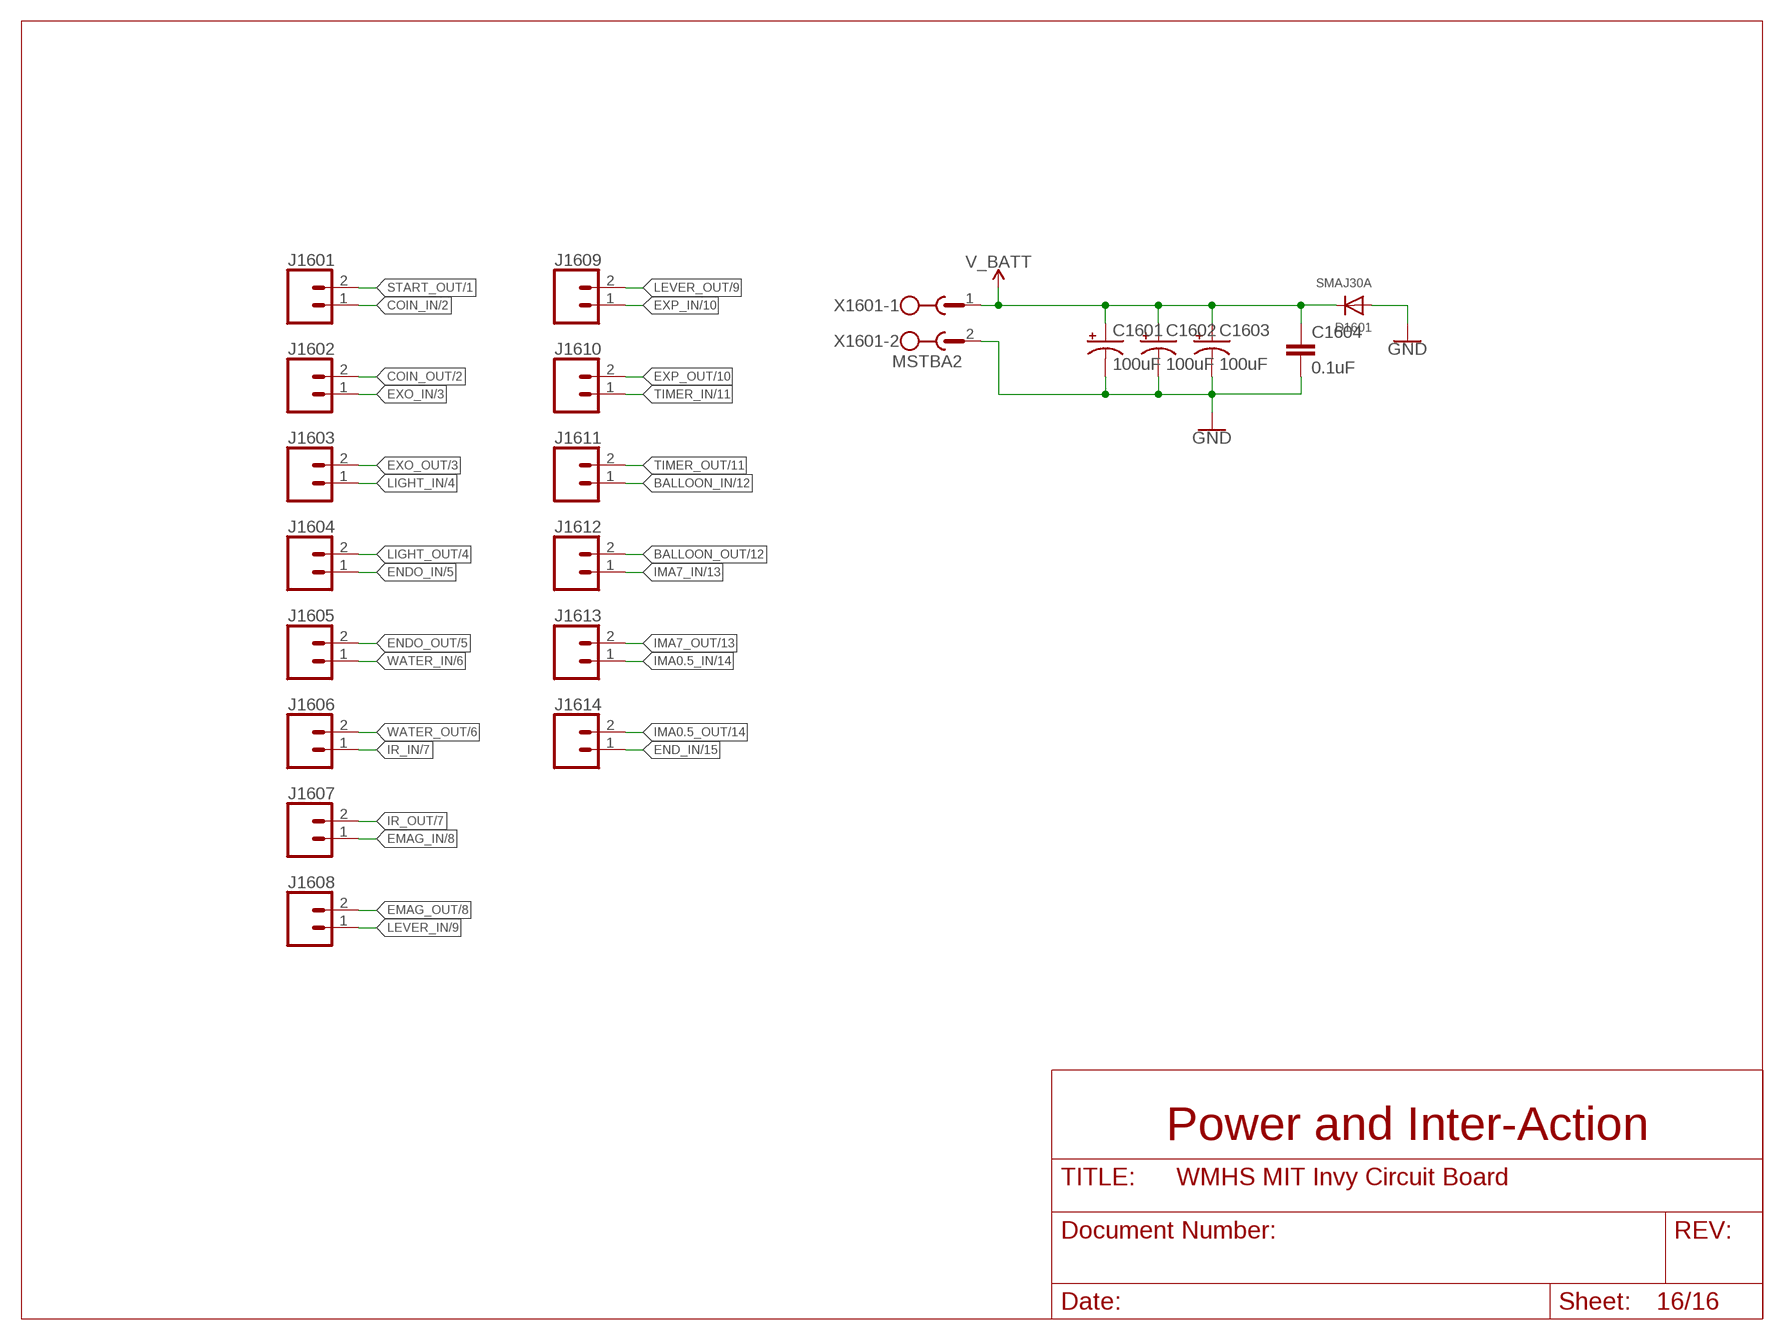
[diagram p15: schematic, sheet 16]

(export (version "E")
  (design (tool "Eeschema 10.0.6"))
  (components
    (comp (ref "C301")
      (value "0.1uF")
      (footprint "eagle-import:0603")
      (libsource (lib "eagle-import") (part "0.1UF-0603-25V-5%"))
    )
    (comp (ref "C302")
      (value "2.2uF")
      (footprint "eagle-import:EIA3216")
      (libsource (lib "eagle-import") (part "10UF-POLAR-EIA3216-16V-10%(TANT)"))
    )
    (comp (ref "D301")
      (value "INCANDESCENT")
      (footprint "eagle-import:LED_3MM")
      (libsource (lib "eagle-import") (part "LED3MM"))
    )
    (comp (ref "D302")
      (value "GREEN")
      (footprint "eagle-import:LED-0603")
      (libsource (lib "eagle-import") (part "LED-GREEN0603"))
    )
    (comp (ref "D303")
      (value "YELLOW")
      (footprint "eagle-import:LED-0603")
      (libsource (lib "eagle-import") (part "LED-YELLOW0603"))
    )
    (comp (ref "D304")
      (value "RED")
      (footprint "eagle-import:LED-0603")
      (libsource (lib "eagle-import") (part "LED-RED0603"))
    )
    (comp (ref "J301")
      (value "ICSP_HEADER")
      (footprint "eagle-import:2X3")
      (libsource (lib "eagle-import") (part "AVR_SPI_PROG_3X2PTH"))
    )
    (comp (ref "Q301")
      (value "500mA/300V")
      (footprint "eagle-import:SOT23-3")
      (libsource (lib "eagle-import") (part "TRANS_NPN-MMBTA42"))
    )
    (comp (ref "R301")
      (value "10K")
      (footprint "eagle-import:0603")
      (libsource (lib "eagle-import") (part "RESISTOR0603"))
    )
    (comp (ref "R302")
      (value "1K")
      (footprint "eagle-import:0603")
      (libsource (lib "eagle-import") (part "RESISTOR0603"))
    )
    (comp (ref "R303")
      (value "PHOTOCELLPTH")
      (footprint "eagle-import:PHOTOCELL")
      (libsource (lib "eagle-import") (part "PHOTOCELLPTH"))
    )
    (comp (ref "R304")
      (value "10K")
      (footprint "eagle-import:0603")
      (libsource (lib "eagle-import") (part "330OHM-0603-1/10W-1%"))
    )
    (comp (ref "R305")
      (value "560r")
      (footprint "eagle-import:0603")
      (libsource (lib "eagle-import") (part "330OHM-0603-1/10W-1%"))
    )
    (comp (ref "R306")
      (value "560r")
      (footprint "eagle-import:0603")
      (libsource (lib "eagle-import") (part "330OHM-0603-1/10W-1%"))
    )
    (comp (ref "R307")
      (value "560r")
      (footprint "eagle-import:0603")
      (libsource (lib "eagle-import") (part "330OHM-0603-1/10W-1%"))
    )
    (comp (ref "S301")
      (value "RST")
      (footprint "eagle-import:TACTILE_SWITCH_SMD_5.2MM")
      (libsource (lib "eagle-import") (part "MOMENTARY-SWITCH-SPST-SMD-5.2-REDUNDANT"))
    )
    (comp (ref "S302")
      (value "SWITCH-SPDT-SMD-AYZ0202")
      (footprint "eagle-import:SWITCH_DPDT_SMD_AYZ0202")
      (libsource (lib "eagle-import") (part "SWITCH-SPDT-SMD-AYZ0202"))
    )
    (comp (ref "TP301")
      (value "PTR1TP20R")
      (footprint "eagle-import:TP20R")
      (libsource (lib "eagle-import") (part "PTR1TP20R"))
    )
    (comp (ref "TP302")
      (value "PTR1TP20R")
      (footprint "eagle-import:TP20R")
      (libsource (lib "eagle-import") (part "PTR1TP20R"))
    )
    (comp (ref "TP303")
      (value "PTR1TP20R")
      (footprint "eagle-import:TP20R")
      (libsource (lib "eagle-import") (part "PTR1TP20R"))
    )
    (comp (ref "U301")
      (value "74HC1G04")
      (footprint "eagle-import:SOT353")
      (libsource (lib "eagle-import") (part "741G04HC"))
    )
    (comp (ref "U302")
      (value "SN74C1G08-DCK")
      (footprint "eagle-import:SC-70-5")
      (libsource (lib "eagle-import") (part "SN74C1G08-DCK"))
    )
    (comp (ref "U303")
      (value "ATTINY25-20SSUR")
      (footprint "eagle-import:SOIC8")
      (libsource (lib "eagle-import") (part "ATTINY45-SMT-NARROW"))
    )
    (comp (ref "U304")
      (value "MIC5205")
      (footprint "eagle-import:SOT23-5")
      (libsource (lib "eagle-import") (part "V_REG_MIC52055V"))
    )
    (comp (ref "C201")
      (value "0.1uF")
      (footprint "eagle-import:0603")
      (libsource (lib "eagle-import") (part "0.1UF-0603-25V-5%"))
    )
    (comp (ref "C202")
      (value "2.2uF")
      (footprint "eagle-import:EIA3216")
      (libsource (lib "eagle-import") (part "10UF-POLAR-EIA3216-16V-10%(TANT)"))
    )
    (comp (ref "D201")
      (value "SK310A-TP")
      (footprint "eagle-import:SMADIODE")
      (libsource (lib "eagle-import") (part "DIODESMA"))
    )
    (comp (ref "D202")
      (value "GREEN")
      (footprint "eagle-import:LED-0603")
      (libsource (lib "eagle-import") (part "LED-GREEN0603"))
    )
    (comp (ref "D203")
      (value "YELLOW")
      (footprint "eagle-import:LED-0603")
      (libsource (lib "eagle-import") (part "LED-YELLOW0603"))
    )
    (comp (ref "D204")
      (value "RED")
      (footprint "eagle-import:LED-0603")
      (libsource (lib "eagle-import") (part "LED-RED0603"))
    )
    (comp (ref "J201")
      (value "CONN_03LOCK")
      (footprint "eagle-import:1X03_LOCK")
      (libsource (lib "eagle-import") (part "CONN_03LOCK"))
    )
    (comp (ref "J202")
      (value "CONN_02LOCK")
      (footprint "eagle-import:1X02_LOCK")
      (libsource (lib "eagle-import") (part "CONN_02LOCK"))
    )
    (comp (ref "J203")
      (value "CONN_023.5MM_LOCK")
      (footprint "eagle-import:SCREWTERMINAL-3.5MM-2_LOCK")
      (libsource (lib "eagle-import") (part "CONN_023.5MM_LOCK"))
    )
    (comp (ref "J204")
      (value "ICSP_HEADER")
      (footprint "eagle-import:2X3")
      (libsource (lib "eagle-import") (part "AVR_SPI_PROG_3X2PTH"))
    )
    (comp (ref "JP201")
      (value "JUMPER-SMT_2_NO_SILK")
      (footprint "eagle-import:SMT-JUMPER_2_NO_SILK")
      (libsource (lib "eagle-import") (part "JUMPER-SMT_2_NO_SILK"))
    )
    (comp (ref "JP202")
      (value "JUMPER-SMT_2_NC_TRACE_SILK")
      (footprint "eagle-import:SMT-JUMPER_2_NC_TRACE_SILK")
      (libsource (lib "eagle-import") (part "JUMPER-SMT_2_NC_TRACE_SILK"))
    )
    (comp (ref "Q201")
      (value "PSMN7R0-60YS")
      (footprint "eagle-import:SOT669")
      (libsource (lib "eagle-import") (part "PSMN7R0-60YS"))
    )
    (comp (ref "R201")
      (value "10R")
      (footprint "eagle-import:0603")
      (libsource (lib "eagle-import") (part "RESISTOR0603"))
    )
    (comp (ref "R202")
      (value "100K")
      (footprint "eagle-import:0603")
      (libsource (lib "eagle-import") (part "RESISTOR0603"))
    )
    (comp (ref "R203")
      (value "10k")
      (footprint "eagle-import:0603")
      (libsource (lib "eagle-import") (part "RESISTOR0603"))
    )
    (comp (ref "R204")
      (value "10K")
      (footprint "eagle-import:0603")
      (libsource (lib "eagle-import") (part "330OHM-0603-1/10W-1%"))
    )
    (comp (ref "R205")
      (value "560r")
      (footprint "eagle-import:0603")
      (libsource (lib "eagle-import") (part "330OHM-0603-1/10W-1%"))
    )
    (comp (ref "R206")
      (value "560r")
      (footprint "eagle-import:0603")
      (libsource (lib "eagle-import") (part "330OHM-0603-1/10W-1%"))
    )
    (comp (ref "R207")
      (value "560r")
      (footprint "eagle-import:0603")
      (libsource (lib "eagle-import") (part "330OHM-0603-1/10W-1%"))
    )
    (comp (ref "S201")
      (value "RST")
      (footprint "eagle-import:TACTILE_SWITCH_SMD_5.2MM")
      (libsource (lib "eagle-import") (part "MOMENTARY-SWITCH-SPST-SMD-5.2-REDUNDANT"))
    )
    (comp (ref "S202")
      (value "SWITCH-SPDT-SMD-AYZ0202")
      (footprint "eagle-import:SWITCH_DPDT_SMD_AYZ0202")
      (libsource (lib "eagle-import") (part "SWITCH-SPDT-SMD-AYZ0202"))
    )
    (comp (ref "TP201")
      (value "PTR1TP20R")
      (footprint "eagle-import:TP20R")
      (libsource (lib "eagle-import") (part "PTR1TP20R"))
    )
    (comp (ref "TP202")
      (value "PTR1TP20R")
      (footprint "eagle-import:TP20R")
      (libsource (lib "eagle-import") (part "PTR1TP20R"))
    )
    (comp (ref "TP203")
      (value "PTR1TP20R")
      (footprint "eagle-import:TP20R")
      (libsource (lib "eagle-import") (part "PTR1TP20R"))
    )
    (comp (ref "U201")
      (value "74HC1G04")
      (footprint "eagle-import:SOT353")
      (libsource (lib "eagle-import") (part "741G04HC"))
    )
    (comp (ref "U202")
      (value "ATTINY25-20SSUR")
      (footprint "eagle-import:SOIC8")
      (libsource (lib "eagle-import") (part "ATTINY45-SMT-NARROW"))
    )
    (comp (ref "U203")
      (value "MIC5205")
      (footprint "eagle-import:SOT23-5")
      (libsource (lib "eagle-import") (part "V_REG_MIC52055V"))
    )
    (comp (ref "C1201")
      (value "0.1uF")
      (footprint "eagle-import:0603")
      (libsource (lib "eagle-import") (part "0.1UF-0603-25V-5%"))
    )
    (comp (ref "C1202")
      (value "0.33uF")
      (footprint "eagle-import:0603")
      (libsource (lib "eagle-import") (part "0.1UF-0603-25V-(+80/-20%)"))
    )
    (comp (ref "C1203")
      (value "0.1uF")
      (footprint "eagle-import:0603")
      (libsource (lib "eagle-import") (part "0.1UF-0603-25V-(+80/-20%)"))
    )
    (comp (ref "D1201")
      (value "GREEN")
      (footprint "eagle-import:LED-0603")
      (libsource (lib "eagle-import") (part "LED-GREEN0603"))
    )
    (comp (ref "D1202")
      (value "YELLOW")
      (footprint "eagle-import:LED-0603")
      (libsource (lib "eagle-import") (part "LED-YELLOW0603"))
    )
    (comp (ref "D1203")
      (value "RED")
      (footprint "eagle-import:LED-0603")
      (libsource (lib "eagle-import") (part "LED-RED0603"))
    )
    (comp (ref "IC1201")
      (value "7805DT")
      (footprint "eagle-import:TO252")
      (libsource (lib "eagle-import") (part "78DT05"))
    )
    (comp (ref "J1201")
      (value "CONN_02LOCK")
      (footprint "eagle-import:1X02_LOCK")
      (libsource (lib "eagle-import") (part "CONN_02LOCK"))
    )
    (comp (ref "J1202")
      (value "CONN_02LOCK")
      (footprint "eagle-import:1X02_LOCK")
      (libsource (lib "eagle-import") (part "CONN_02LOCK"))
    )
    (comp (ref "J1203")
      (value "CONN_02LOCK")
      (footprint "eagle-import:1X02_LOCK")
      (libsource (lib "eagle-import") (part "CONN_02LOCK"))
    )
    (comp (ref "J1204")
      (value "ICSP_HEADER")
      (footprint "eagle-import:2X3")
      (libsource (lib "eagle-import") (part "AVR_SPI_PROG_3X2PTH"))
    )
    (comp (ref "R1201")
      (value "10K")
      (footprint "eagle-import:0603")
      (libsource (lib "eagle-import") (part "RESISTOR0603"))
    )
    (comp (ref "R1202")
      (value "10K")
      (footprint "eagle-import:0603")
      (libsource (lib "eagle-import") (part "RESISTOR0603"))
    )
    (comp (ref "R1203")
      (value "10K")
      (footprint "eagle-import:0603")
      (libsource (lib "eagle-import") (part "330OHM-0603-1/10W-1%"))
    )
    (comp (ref "R1204")
      (value "560r")
      (footprint "eagle-import:0603")
      (libsource (lib "eagle-import") (part "330OHM-0603-1/10W-1%"))
    )
    (comp (ref "R1205")
      (value "560r")
      (footprint "eagle-import:0603")
      (libsource (lib "eagle-import") (part "330OHM-0603-1/10W-1%"))
    )
    (comp (ref "R1206")
      (value "560r")
      (footprint "eagle-import:0603")
      (libsource (lib "eagle-import") (part "330OHM-0603-1/10W-1%"))
    )
    (comp (ref "S1201")
      (value "RST")
      (footprint "eagle-import:TACTILE_SWITCH_SMD_5.2MM")
      (libsource (lib "eagle-import") (part "MOMENTARY-SWITCH-SPST-SMD-5.2-REDUNDANT"))
    )
    (comp (ref "S1202")
      (value "SWITCH-SPDT-SMD-AYZ0202")
      (footprint "eagle-import:SWITCH_DPDT_SMD_AYZ0202")
      (libsource (lib "eagle-import") (part "SWITCH-SPDT-SMD-AYZ0202"))
    )
    (comp (ref "TP1201")
      (value "PTR1TP20R")
      (footprint "eagle-import:TP20R")
      (libsource (lib "eagle-import") (part "PTR1TP20R"))
    )
    (comp (ref "TP1202")
      (value "PTR1TP20R")
      (footprint "eagle-import:TP20R")
      (libsource (lib "eagle-import") (part "PTR1TP20R"))
    )
    (comp (ref "U1201")
      (value "DRV8835")
      (footprint "eagle-import:WSON-12")
      (libsource (lib "eagle-import") (part "DRV883X"))
    )
    (comp (ref "U1202")
      (value "ATTINY25-20SSUR")
      (footprint "eagle-import:SOIC8")
      (libsource (lib "eagle-import") (part "ATTINY45-SMT-NARROW"))
    )
    (comp (ref "C101")
      (value "2.2uF")
      (footprint "eagle-import:EIA3216")
      (libsource (lib "eagle-import") (part "10UF-POLAR-EIA3216-16V-10%(TANT)"))
    )
    (comp (ref "D101")
      (value "GREEN")
      (footprint "eagle-import:LED-0603")
      (libsource (lib "eagle-import") (part "LED-GREEN0603"))
    )
    (comp (ref "D102")
      (value "RED")
      (footprint "eagle-import:LED-0603")
      (libsource (lib "eagle-import") (part "LED-RED0603"))
    )
    (comp (ref "JP101")
      (value "JUMPER_NC_TRACE")
      (footprint "eagle-import:SMT-JUMPER_2_NC_TRACE_SILK")
      (libsource (lib "eagle-import") (part "JUMPER-SMT_2_NC_TRACE_SILK"))
    )
    (comp (ref "JP102")
      (value "JUMPER-SMT_2_NO_SILK")
      (footprint "eagle-import:SMT-JUMPER_2_NO_SILK")
      (libsource (lib "eagle-import") (part "JUMPER-SMT_2_NO_SILK"))
    )
    (comp (ref "R101")
      (value "10K")
      (footprint "eagle-import:0603")
      (libsource (lib "eagle-import") (part "330OHM-0603-1/10W-1%"))
    )
    (comp (ref "R102")
      (value "560r")
      (footprint "eagle-import:0603")
      (libsource (lib "eagle-import") (part "330OHM-0603-1/10W-1%"))
    )
    (comp (ref "R103")
      (value "560r")
      (footprint "eagle-import:0603")
      (libsource (lib "eagle-import") (part "330OHM-0603-1/10W-1%"))
    )
    (comp (ref "S101")
      (value "REED_SWITCH")
      (footprint "eagle-import:AXIAL_GULLWING_REED")
      (libsource (lib "eagle-import") (part "MDSM-10_REED_SWITCH"))
    )
    (comp (ref "S102")
      (value "SWITCH-SPDT-SMD-AYZ0202")
      (footprint "eagle-import:SWITCH_DPDT_SMD_AYZ0202")
      (libsource (lib "eagle-import") (part "SWITCH-SPDT-SMD-AYZ0202"))
    )
    (comp (ref "TP101")
      (value "PTR1TP20R")
      (footprint "eagle-import:TP20R")
      (libsource (lib "eagle-import") (part "PTR1TP20R"))
    )
    (comp (ref "U101")
      (value "74HC1G04")
      (footprint "eagle-import:SOT353")
      (libsource (lib "eagle-import") (part "741G04HC"))
    )
    (comp (ref "U102")
      (value "MIC5205")
      (footprint "eagle-import:SOT23-5")
      (libsource (lib "eagle-import") (part "V_REG_MIC52055V"))
    )
    (comp (ref "C1301")
      (value "0.1uF")
      (footprint "eagle-import:0603")
      (libsource (lib "eagle-import") (part "0.1UF-0603-25V-5%"))
    )
    (comp (ref "C1302")
      (value "0.33uF")
      (footprint "eagle-import:0603")
      (libsource (lib "eagle-import") (part "0.1UF-0603-25V-(+80/-20%)"))
    )
    (comp (ref "C1303")
      (value "0.1uF")
      (footprint "eagle-import:0603")
      (libsource (lib "eagle-import") (part "0.1UF-0603-25V-(+80/-20%)"))
    )
    (comp (ref "D1301")
      (value "GREEN")
      (footprint "eagle-import:LED-0603")
      (libsource (lib "eagle-import") (part "LED-GREEN0603"))
    )
    (comp (ref "D1302")
      (value "YELLOW")
      (footprint "eagle-import:LED-0603")
      (libsource (lib "eagle-import") (part "LED-YELLOW0603"))
    )
    (comp (ref "D1303")
      (value "RED")
      (footprint "eagle-import:LED-0603")
      (libsource (lib "eagle-import") (part "LED-RED0603"))
    )
    (comp (ref "IC1301")
      (value "7805DT")
      (footprint "eagle-import:TO252")
      (libsource (lib "eagle-import") (part "78DT05"))
    )
    (comp (ref "J1301")
      (value "CONN_02LOCK")
      (footprint "eagle-import:1X02_LOCK")
      (libsource (lib "eagle-import") (part "CONN_02LOCK"))
    )
    (comp (ref "J1302")
      (value "CONN_02LOCK")
      (footprint "eagle-import:1X02_LOCK")
      (libsource (lib "eagle-import") (part "CONN_02LOCK"))
    )
    (comp (ref "J1303")
      (value "CONN_02LOCK")
      (footprint "eagle-import:1X02_LOCK")
      (libsource (lib "eagle-import") (part "CONN_02LOCK"))
    )
    (comp (ref "J1304")
      (value "ICSP_HEADER")
      (footprint "eagle-import:2X3")
      (libsource (lib "eagle-import") (part "AVR_SPI_PROG_3X2PTH"))
    )
    (comp (ref "R1301")
      (value "10K")
      (footprint "eagle-import:0603")
      (libsource (lib "eagle-import") (part "RESISTOR0603"))
    )
    (comp (ref "R1302")
      (value "10K")
      (footprint "eagle-import:0603")
      (libsource (lib "eagle-import") (part "RESISTOR0603"))
    )
    (comp (ref "R1303")
      (value "10K")
      (footprint "eagle-import:0603")
      (libsource (lib "eagle-import") (part "330OHM-0603-1/10W-1%"))
    )
    (comp (ref "R1304")
      (value "560r")
      (footprint "eagle-import:0603")
      (libsource (lib "eagle-import") (part "330OHM-0603-1/10W-1%"))
    )
    (comp (ref "R1305")
      (value "560r")
      (footprint "eagle-import:0603")
      (libsource (lib "eagle-import") (part "330OHM-0603-1/10W-1%"))
    )
    (comp (ref "R1306")
      (value "560r")
      (footprint "eagle-import:0603")
      (libsource (lib "eagle-import") (part "330OHM-0603-1/10W-1%"))
    )
    (comp (ref "S1301")
      (value "RST")
      (footprint "eagle-import:TACTILE_SWITCH_SMD_5.2MM")
      (libsource (lib "eagle-import") (part "MOMENTARY-SWITCH-SPST-SMD-5.2-REDUNDANT"))
    )
    (comp (ref "S1302")
      (value "SWITCH-SPDT-SMD-AYZ0202")
      (footprint "eagle-import:SWITCH_DPDT_SMD_AYZ0202")
      (libsource (lib "eagle-import") (part "SWITCH-SPDT-SMD-AYZ0202"))
    )
    (comp (ref "TP1301")
      (value "PTR1TP20R")
      (footprint "eagle-import:TP20R")
      (libsource (lib "eagle-import") (part "PTR1TP20R"))
    )
    (comp (ref "TP1302")
      (value "PTR1TP20R")
      (footprint "eagle-import:TP20R")
      (libsource (lib "eagle-import") (part "PTR1TP20R"))
    )
    (comp (ref "U1301")
      (value "DRV8835")
      (footprint "eagle-import:WSON-12")
      (libsource (lib "eagle-import") (part "DRV883X"))
    )
    (comp (ref "U1302")
      (value "ATTINY25-20SSUR")
      (footprint "eagle-import:SOIC8")
      (libsource (lib "eagle-import") (part "ATTINY45-SMT-NARROW"))
    )
    (comp (ref "C1001")
      (value "0.1uF")
      (footprint "eagle-import:0603")
      (libsource (lib "eagle-import") (part "0.1UF-0603-25V-5%"))
    )
    (comp (ref "C1002")
      (value "2.2uF")
      (footprint "eagle-import:EIA3216")
      (libsource (lib "eagle-import") (part "10UF-POLAR-EIA3216-16V-10%(TANT)"))
    )
    (comp (ref "D1001")
      (value "SK310A-TP")
      (footprint "eagle-import:SMADIODE")
      (libsource (lib "eagle-import") (part "DIODESMA"))
    )
    (comp (ref "D1002")
      (value "GREEN")
      (footprint "eagle-import:LED-0603")
      (libsource (lib "eagle-import") (part "LED-GREEN0603"))
    )
    (comp (ref "D1003")
      (value "YELLOW")
      (footprint "eagle-import:LED-0603")
      (libsource (lib "eagle-import") (part "LED-YELLOW0603"))
    )
    (comp (ref "D1004")
      (value "RED")
      (footprint "eagle-import:LED-0603")
      (libsource (lib "eagle-import") (part "LED-RED0603"))
    )
    (comp (ref "J1001")
      (value "CONN_023.5MM_LOCK")
      (footprint "eagle-import:SCREWTERMINAL-3.5MM-2_LOCK")
      (libsource (lib "eagle-import") (part "CONN_023.5MM_LOCK"))
    )
    (comp (ref "J1002")
      (value "CONN_02LOCK")
      (footprint "eagle-import:1X02_LOCK")
      (libsource (lib "eagle-import") (part "CONN_02LOCK"))
    )
    (comp (ref "J1003")
      (value "CONN_02LOCK")
      (footprint "eagle-import:1X02_LOCK")
      (libsource (lib "eagle-import") (part "CONN_02LOCK"))
    )
    (comp (ref "J1004")
      (value "CONN_02LOCK")
      (footprint "eagle-import:1X02_LOCK")
      (libsource (lib "eagle-import") (part "CONN_02LOCK"))
    )
    (comp (ref "J1005")
      (value "ICSP_HEADER")
      (footprint "eagle-import:2X3")
      (libsource (lib "eagle-import") (part "AVR_SPI_PROG_3X2PTH"))
    )
    (comp (ref "Q1001")
      (value "PSMN7R0-60YS")
      (footprint "eagle-import:SOT669")
      (libsource (lib "eagle-import") (part "PSMN7R0-60YS"))
    )
    (comp (ref "R1001")
      (value "10R")
      (footprint "eagle-import:0603")
      (libsource (lib "eagle-import") (part "RESISTOR0603"))
    )
    (comp (ref "R1002")
      (value "100K")
      (footprint "eagle-import:0603")
      (libsource (lib "eagle-import") (part "RESISTOR0603"))
    )
    (comp (ref "R1003")
      (value "100K")
      (footprint "eagle-import:0603")
      (libsource (lib "eagle-import") (part "RESISTOR0603"))
    )
    (comp (ref "R1004")
      (value "1M")
      (footprint "eagle-import:0603")
      (libsource (lib "eagle-import") (part "RESISTOR0603"))
    )
    (comp (ref "R1005")
      (value "10K")
      (footprint "eagle-import:0603")
      (libsource (lib "eagle-import") (part "330OHM-0603-1/10W-1%"))
    )
    (comp (ref "R1006")
      (value "560r")
      (footprint "eagle-import:0603")
      (libsource (lib "eagle-import") (part "330OHM-0603-1/10W-1%"))
    )
    (comp (ref "R1007")
      (value "560r")
      (footprint "eagle-import:0603")
      (libsource (lib "eagle-import") (part "330OHM-0603-1/10W-1%"))
    )
    (comp (ref "R1008")
      (value "560r")
      (footprint "eagle-import:0603")
      (libsource (lib "eagle-import") (part "330OHM-0603-1/10W-1%"))
    )
    (comp (ref "S1001")
      (value "RST")
      (footprint "eagle-import:TACTILE_SWITCH_SMD_5.2MM")
      (libsource (lib "eagle-import") (part "MOMENTARY-SWITCH-SPST-SMD-5.2-REDUNDANT"))
    )
    (comp (ref "S1002")
      (value "SWITCH-SPDT-SMD-AYZ0202")
      (footprint "eagle-import:SWITCH_DPDT_SMD_AYZ0202")
      (libsource (lib "eagle-import") (part "SWITCH-SPDT-SMD-AYZ0202"))
    )
    (comp (ref "TP1001")
      (value "PTR1TP20R")
      (footprint "eagle-import:TP20R")
      (libsource (lib "eagle-import") (part "PTR1TP20R"))
    )
    (comp (ref "TP1002")
      (value "PTR1TP20R")
      (footprint "eagle-import:TP20R")
      (libsource (lib "eagle-import") (part "PTR1TP20R"))
    )
    (comp (ref "U1001")
      (value "ATTINY25-20SSUR")
      (footprint "eagle-import:SOIC8")
      (libsource (lib "eagle-import") (part "ATTINY45-SMT-NARROW"))
    )
    (comp (ref "U1002")
      (value "MIC5205")
      (footprint "eagle-import:SOT23-5")
      (libsource (lib "eagle-import") (part "V_REG_MIC52055V"))
    )
    (comp (ref "C801")
      (value "2.2uF")
      (footprint "eagle-import:EIA3216")
      (libsource (lib "eagle-import") (part "10UF-POLAR-EIA3216-16V-10%(TANT)"))
    )
    (comp (ref "D801")
      (value "SK310A-TP")
      (footprint "eagle-import:SMADIODE")
      (libsource (lib "eagle-import") (part "DIODESMA"))
    )
    (comp (ref "D802")
      (value "GREEN")
      (footprint "eagle-import:LED-0603")
      (libsource (lib "eagle-import") (part "LED-GREEN0603"))
    )
    (comp (ref "D803")
      (value "YELLOW")
      (footprint "eagle-import:LED-0603")
      (libsource (lib "eagle-import") (part "LED-YELLOW0603"))
    )
    (comp (ref "D804")
      (value "RED")
      (footprint "eagle-import:LED-0603")
      (libsource (lib "eagle-import") (part "LED-RED0603"))
    )
    (comp (ref "J801")
      (value "CONN_02LOCK")
      (footprint "eagle-import:1X02_LOCK")
      (libsource (lib "eagle-import") (part "CONN_02LOCK"))
    )
    (comp (ref "J802")
      (value "CONN_023.5MM_LOCK")
      (footprint "eagle-import:SCREWTERMINAL-3.5MM-2_LOCK")
      (libsource (lib "eagle-import") (part "CONN_023.5MM_LOCK"))
    )
    (comp (ref "Q801")
      (value "PSMN7R0-60YS")
      (footprint "eagle-import:SOT669")
      (libsource (lib "eagle-import") (part "PSMN7R0-60YS"))
    )
    (comp (ref "R801")
      (value "10K")
      (footprint "eagle-import:0603")
      (libsource (lib "eagle-import") (part "RESISTOR0603"))
    )
    (comp (ref "R802")
      (value "10R")
      (footprint "eagle-import:0603")
      (libsource (lib "eagle-import") (part "RESISTOR0603"))
    )
    (comp (ref "R803")
      (value "100K")
      (footprint "eagle-import:0603")
      (libsource (lib "eagle-import") (part "RESISTOR0603"))
    )
    (comp (ref "R804")
      (value "560r")
      (footprint "eagle-import:0603")
      (libsource (lib "eagle-import") (part "330OHM-0603-1/10W-1%"))
    )
    (comp (ref "R805")
      (value "560r")
      (footprint "eagle-import:0603")
      (libsource (lib "eagle-import") (part "330OHM-0603-1/10W-1%"))
    )
    (comp (ref "R806")
      (value "560r")
      (footprint "eagle-import:0603")
      (libsource (lib "eagle-import") (part "330OHM-0603-1/10W-1%"))
    )
    (comp (ref "S801")
      (value "SWITCH-SPDT-SMD-AYZ0202")
      (footprint "eagle-import:SWITCH_DPDT_SMD_AYZ0202")
      (libsource (lib "eagle-import") (part "SWITCH-SPDT-SMD-AYZ0202"))
    )
    (comp (ref "TP801")
      (value "PTR1TP20R")
      (footprint "eagle-import:TP20R")
      (libsource (lib "eagle-import") (part "PTR1TP20R"))
    )
    (comp (ref "TP802")
      (value "PTR1TP20R")
      (footprint "eagle-import:TP20R")
      (libsource (lib "eagle-import") (part "PTR1TP20R"))
    )
    (comp (ref "TP803")
      (value "PTR1TP20R")
      (footprint "eagle-import:TP20R")
      (libsource (lib "eagle-import") (part "PTR1TP20R"))
    )
    (comp (ref "U801")
      (value "74HC1G04")
      (footprint "eagle-import:SOT353")
      (libsource (lib "eagle-import") (part "741G04HC"))
    )
    (comp (ref "U802")
      (value "SN74C1G08-DCK")
      (footprint "eagle-import:SC-70-5")
      (libsource (lib "eagle-import") (part "SN74C1G08-DCK"))
    )
    (comp (ref "U803")
      (value "MIC5205")
      (footprint "eagle-import:SOT23-5")
      (libsource (lib "eagle-import") (part "V_REG_MIC52055V"))
    )
    (comp (ref "C401")
      (value "0.1uF")
      (footprint "eagle-import:0603")
      (libsource (lib "eagle-import") (part "0.1UF-0603-25V-5%"))
    )
    (comp (ref "C402")
      (value "2.2uF")
      (footprint "eagle-import:EIA3216")
      (libsource (lib "eagle-import") (part "10UF-POLAR-EIA3216-16V-10%(TANT)"))
    )
    (comp (ref "D401")
      (value "WHITE")
      (footprint "eagle-import:LED_3MM")
      (libsource (lib "eagle-import") (part "LED3MM"))
    )
    (comp (ref "D402")
      (value "GREEN")
      (footprint "eagle-import:LED-0603")
      (libsource (lib "eagle-import") (part "LED-GREEN0603"))
    )
    (comp (ref "D403")
      (value "YELLOW")
      (footprint "eagle-import:LED-0603")
      (libsource (lib "eagle-import") (part "LED-YELLOW0603"))
    )
    (comp (ref "D404")
      (value "RED")
      (footprint "eagle-import:LED-0603")
      (libsource (lib "eagle-import") (part "LED-RED0603"))
    )
    (comp (ref "J401")
      (value "ICSP_HEADER")
      (footprint "eagle-import:2X3")
      (libsource (lib "eagle-import") (part "AVR_SPI_PROG_3X2PTH"))
    )
    (comp (ref "Q401")
      (value "500mA/300V")
      (footprint "eagle-import:SOT23-3")
      (libsource (lib "eagle-import") (part "TRANS_NPN-MMBTA42"))
    )
    (comp (ref "R401")
      (value "10K")
      (footprint "eagle-import:0603")
      (libsource (lib "eagle-import") (part "RESISTOR0603"))
    )
    (comp (ref "R402")
      (value "PHOTOCELLPTH")
      (footprint "eagle-import:PHOTOCELL")
      (libsource (lib "eagle-import") (part "PHOTOCELLPTH"))
    )
    (comp (ref "R403")
      (value "1K")
      (footprint "eagle-import:0603")
      (libsource (lib "eagle-import") (part "RESISTOR0603"))
    )
    (comp (ref "R404")
      (value "560")
      (footprint "eagle-import:0603")
      (libsource (lib "eagle-import") (part "RESISTOR0603"))
    )
    (comp (ref "R405")
      (value "10K")
      (footprint "eagle-import:0603")
      (libsource (lib "eagle-import") (part "330OHM-0603-1/10W-1%"))
    )
    (comp (ref "R406")
      (value "560r")
      (footprint "eagle-import:0603")
      (libsource (lib "eagle-import") (part "330OHM-0603-1/10W-1%"))
    )
    (comp (ref "R407")
      (value "560r")
      (footprint "eagle-import:0603")
      (libsource (lib "eagle-import") (part "330OHM-0603-1/10W-1%"))
    )
    (comp (ref "R408")
      (value "560r")
      (footprint "eagle-import:0603")
      (libsource (lib "eagle-import") (part "330OHM-0603-1/10W-1%"))
    )
    (comp (ref "S401")
      (value "RST")
      (footprint "eagle-import:TACTILE_SWITCH_SMD_5.2MM")
      (libsource (lib "eagle-import") (part "MOMENTARY-SWITCH-SPST-SMD-5.2-REDUNDANT"))
    )
    (comp (ref "S402")
      (value "SWITCH-SPDT-SMD-AYZ0202")
      (footprint "eagle-import:SWITCH_DPDT_SMD_AYZ0202")
      (libsource (lib "eagle-import") (part "SWITCH-SPDT-SMD-AYZ0202"))
    )
    (comp (ref "TP401")
      (value "PTR1TP20R")
      (footprint "eagle-import:TP20R")
      (libsource (lib "eagle-import") (part "PTR1TP20R"))
    )
    (comp (ref "TP402")
      (value "PTR1TP20R")
      (footprint "eagle-import:TP20R")
      (libsource (lib "eagle-import") (part "PTR1TP20R"))
    )
    (comp (ref "TP403")
      (value "PTR1TP20R")
      (footprint "eagle-import:TP20R")
      (libsource (lib "eagle-import") (part "PTR1TP20R"))
    )
    (comp (ref "TP404")
      (value "PTR1TP20R")
      (footprint "eagle-import:TP20R")
      (libsource (lib "eagle-import") (part "PTR1TP20R"))
    )
    (comp (ref "U401")
      (value "74HC1G04")
      (footprint "eagle-import:SOT353")
      (libsource (lib "eagle-import") (part "741G04HC"))
    )
    (comp (ref "U402")
      (value "SN74C1G08-DCK")
      (footprint "eagle-import:SC-70-5")
      (libsource (lib "eagle-import") (part "SN74C1G08-DCK"))
    )
    (comp (ref "U403")
      (value "ATTINY25-20SSUR")
      (footprint "eagle-import:SOIC8")
      (libsource (lib "eagle-import") (part "ATTINY45-SMT-NARROW"))
    )
    (comp (ref "U404")
      (value "MIC5205")
      (footprint "eagle-import:SOT23-5")
      (libsource (lib "eagle-import") (part "V_REG_MIC52055V"))
    )
    (comp (ref "C501")
      (value "0.1uF")
      (footprint "eagle-import:0603")
      (libsource (lib "eagle-import") (part "0.1UF-0603-25V-5%"))
    )
    (comp (ref "C502")
      (value "2.2uF")
      (footprint "eagle-import:EIA3216")
      (libsource (lib "eagle-import") (part "10UF-POLAR-EIA3216-16V-10%(TANT)"))
    )
    (comp (ref "D501")
      (value "SK310A-TP")
      (footprint "eagle-import:SMADIODE")
      (libsource (lib "eagle-import") (part "DIODESMA"))
    )
    (comp (ref "D502")
      (value "GREEN")
      (footprint "eagle-import:LED-0603")
      (libsource (lib "eagle-import") (part "LED-GREEN0603"))
    )
    (comp (ref "D503")
      (value "YELLOW")
      (footprint "eagle-import:LED-0603")
      (libsource (lib "eagle-import") (part "LED-YELLOW0603"))
    )
    (comp (ref "D504")
      (value "RED")
      (footprint "eagle-import:LED-0603")
      (libsource (lib "eagle-import") (part "LED-RED0603"))
    )
    (comp (ref "J501")
      (value "CONN_02LOCK")
      (footprint "eagle-import:1X02_LOCK")
      (libsource (lib "eagle-import") (part "CONN_02LOCK"))
    )
    (comp (ref "J502")
      (value "CONN_023.5MM_LOCK")
      (footprint "eagle-import:SCREWTERMINAL-3.5MM-2_LOCK")
      (libsource (lib "eagle-import") (part "CONN_023.5MM_LOCK"))
    )
    (comp (ref "J503")
      (value "ICSP_HEADER")
      (footprint "eagle-import:2X3")
      (libsource (lib "eagle-import") (part "AVR_SPI_PROG_3X2PTH"))
    )
    (comp (ref "Q501")
      (value "PSMN7R0-60YS")
      (footprint "eagle-import:SOT669")
      (libsource (lib "eagle-import") (part "PSMN7R0-60YS"))
    )
    (comp (ref "R501")
      (value "0R")
      (footprint "eagle-import:0603")
      (libsource (lib "eagle-import") (part "RESISTOR0603"))
    )
    (comp (ref "R502")
      (value "10R")
      (footprint "eagle-import:0603")
      (libsource (lib "eagle-import") (part "RESISTOR0603"))
    )
    (comp (ref "R503")
      (value "100K")
      (footprint "eagle-import:0603")
      (libsource (lib "eagle-import") (part "RESISTOR0603"))
    )
    (comp (ref "R504")
      (value "10K")
      (footprint "eagle-import:0603")
      (libsource (lib "eagle-import") (part "330OHM-0603-1/10W-1%"))
    )
    (comp (ref "R505")
      (value "560r")
      (footprint "eagle-import:0603")
      (libsource (lib "eagle-import") (part "330OHM-0603-1/10W-1%"))
    )
    (comp (ref "R506")
      (value "560r")
      (footprint "eagle-import:0603")
      (libsource (lib "eagle-import") (part "330OHM-0603-1/10W-1%"))
    )
    (comp (ref "R507")
      (value "560r")
      (footprint "eagle-import:0603")
      (libsource (lib "eagle-import") (part "330OHM-0603-1/10W-1%"))
    )
    (comp (ref "S501")
      (value "RST")
      (footprint "eagle-import:TACTILE_SWITCH_SMD_5.2MM")
      (libsource (lib "eagle-import") (part "MOMENTARY-SWITCH-SPST-SMD-5.2-REDUNDANT"))
    )
    (comp (ref "S502")
      (value "SWITCH-SPDT-SMD-AYZ0202")
      (footprint "eagle-import:SWITCH_DPDT_SMD_AYZ0202")
      (libsource (lib "eagle-import") (part "SWITCH-SPDT-SMD-AYZ0202"))
    )
    (comp (ref "TP501")
      (value "PTR1TP20R")
      (footprint "eagle-import:TP20R")
      (libsource (lib "eagle-import") (part "PTR1TP20R"))
    )
    (comp (ref "TP502")
      (value "PTR1TP20R")
      (footprint "eagle-import:TP20R")
      (libsource (lib "eagle-import") (part "PTR1TP20R"))
    )
    (comp (ref "TP503")
      (value "PTR1TP20R")
      (footprint "eagle-import:TP20R")
      (libsource (lib "eagle-import") (part "PTR1TP20R"))
    )
    (comp (ref "TP504")
      (value "PTR1TP20R")
      (footprint "eagle-import:TP20R")
      (libsource (lib "eagle-import") (part "PTR1TP20R"))
    )
    (comp (ref "U501")
      (value "74HC1G04")
      (footprint "eagle-import:SOT353")
      (libsource (lib "eagle-import") (part "741G04HC"))
    )
    (comp (ref "U502")
      (value "SN74C1G08-DCK")
      (footprint "eagle-import:SC-70-5")
      (libsource (lib "eagle-import") (part "SN74C1G08-DCK"))
    )
    (comp (ref "U503")
      (value "ATTINY25-20SSUR")
      (footprint "eagle-import:SOIC8")
      (libsource (lib "eagle-import") (part "ATTINY45-SMT-NARROW"))
    )
    (comp (ref "U504")
      (value "MIC5205")
      (footprint "eagle-import:SOT23-5")
      (libsource (lib "eagle-import") (part "V_REG_MIC52055V"))
    )
    (comp (ref "C1401")
      (value "2.2uF")
      (footprint "eagle-import:EIA3216")
      (libsource (lib "eagle-import") (part "10UF-POLAR-EIA3216-16V-10%(TANT)"))
    )
    (comp (ref "D1401")
      (value "SK310A-TP")
      (footprint "eagle-import:SMADIODE")
      (libsource (lib "eagle-import") (part "DIODESMA"))
    )
    (comp (ref "D1402")
      (value "GREEN")
      (footprint "eagle-import:LED-0603")
      (libsource (lib "eagle-import") (part "LED-GREEN0603"))
    )
    (comp (ref "D1403")
      (value "YELLOW")
      (footprint "eagle-import:LED-0603")
      (libsource (lib "eagle-import") (part "LED-YELLOW0603"))
    )
    (comp (ref "D1404")
      (value "RED")
      (footprint "eagle-import:LED-0603")
      (libsource (lib "eagle-import") (part "LED-RED0603"))
    )
    (comp (ref "J1401")
      (value "CONN_02LOCK")
      (footprint "eagle-import:1X02_LOCK")
      (libsource (lib "eagle-import") (part "CONN_02LOCK"))
    )
    (comp (ref "J1402")
      (value "CONN_023.5MM_LOCK")
      (footprint "eagle-import:SCREWTERMINAL-3.5MM-2_LOCK")
      (libsource (lib "eagle-import") (part "CONN_023.5MM_LOCK"))
    )
    (comp (ref "JP1401")
      (value "JUMPER-SMT_2_NO_SILK")
      (footprint "eagle-import:SMT-JUMPER_2_NO_SILK")
      (libsource (lib "eagle-import") (part "JUMPER-SMT_2_NO_SILK"))
    )
    (comp (ref "JP1402")
      (value "JUMPER-SMT_2_NC_TRACE_SILK")
      (footprint "eagle-import:SMT-JUMPER_2_NC_TRACE_SILK")
      (libsource (lib "eagle-import") (part "JUMPER-SMT_2_NC_TRACE_SILK"))
    )
    (comp (ref "Q1401")
      (value "PSMN7R0-60YS")
      (footprint "eagle-import:SOT669")
      (libsource (lib "eagle-import") (part "PSMN7R0-60YS"))
    )
    (comp (ref "R1401")
      (value "10K")
      (footprint "eagle-import:0603")
      (libsource (lib "eagle-import") (part "RESISTOR0603"))
    )
    (comp (ref "R1402")
      (value "10R")
      (footprint "eagle-import:0603")
      (libsource (lib "eagle-import") (part "RESISTOR0603"))
    )
    (comp (ref "R1403")
      (value "100K")
      (footprint "eagle-import:0603")
      (libsource (lib "eagle-import") (part "RESISTOR0603"))
    )
    (comp (ref "R1404")
      (value "560r")
      (footprint "eagle-import:0603")
      (libsource (lib "eagle-import") (part "330OHM-0603-1/10W-1%"))
    )
    (comp (ref "R1405")
      (value "560r")
      (footprint "eagle-import:0603")
      (libsource (lib "eagle-import") (part "330OHM-0603-1/10W-1%"))
    )
    (comp (ref "R1406")
      (value "560r")
      (footprint "eagle-import:0603")
      (libsource (lib "eagle-import") (part "330OHM-0603-1/10W-1%"))
    )
    (comp (ref "S1401")
      (value "SWITCH-SPDT-SMD-AYZ0202")
      (footprint "eagle-import:SWITCH_DPDT_SMD_AYZ0202")
      (libsource (lib "eagle-import") (part "SWITCH-SPDT-SMD-AYZ0202"))
    )
    (comp (ref "TP1401")
      (value "PTR1TP20R")
      (footprint "eagle-import:TP20R")
      (libsource (lib "eagle-import") (part "PTR1TP20R"))
    )
    (comp (ref "TP1402")
      (value "PTR1TP20R")
      (footprint "eagle-import:TP20R")
      (libsource (lib "eagle-import") (part "PTR1TP20R"))
    )
    (comp (ref "U1401")
      (value "74HC1G04")
      (footprint "eagle-import:SOT353")
      (libsource (lib "eagle-import") (part "741G04HC"))
    )
    (comp (ref "U1402")
      (value "MIC5205")
      (footprint "eagle-import:SOT23-5")
      (libsource (lib "eagle-import") (part "V_REG_MIC52055V"))
    )
    (comp (ref "C601")
      (value "0.1uF")
      (footprint "eagle-import:0603")
      (libsource (lib "eagle-import") (part "0.1UF-0603-25V-5%"))
    )
    (comp (ref "C602")
      (value "2.2uF")
      (footprint "eagle-import:EIA3216")
      (libsource (lib "eagle-import") (part "10UF-POLAR-EIA3216-16V-10%(TANT)"))
    )
    (comp (ref "D601")
      (value "SK310A-TP")
      (footprint "eagle-import:SMADIODE")
      (libsource (lib "eagle-import") (part "DIODESMA"))
    )
    (comp (ref "D602")
      (value "GREEN")
      (footprint "eagle-import:LED-0603")
      (libsource (lib "eagle-import") (part "LED-GREEN0603"))
    )
    (comp (ref "D603")
      (value "YELLOW")
      (footprint "eagle-import:LED-0603")
      (libsource (lib "eagle-import") (part "LED-YELLOW0603"))
    )
    (comp (ref "D604")
      (value "RED")
      (footprint "eagle-import:LED-0603")
      (libsource (lib "eagle-import") (part "LED-RED0603"))
    )
    (comp (ref "J601")
      (value "CONN_02LOCK")
      (footprint "eagle-import:1X02_LOCK")
      (libsource (lib "eagle-import") (part "CONN_02LOCK"))
    )
    (comp (ref "J602")
      (value "CONN_023.5MM_LOCK")
      (footprint "eagle-import:SCREWTERMINAL-3.5MM-2_LOCK")
      (libsource (lib "eagle-import") (part "CONN_023.5MM_LOCK"))
    )
    (comp (ref "J603")
      (value "ICSP_HEADER")
      (footprint "eagle-import:2X3")
      (libsource (lib "eagle-import") (part "AVR_SPI_PROG_3X2PTH"))
    )
    (comp (ref "Q601")
      (value "PSMN7R0-60YS")
      (footprint "eagle-import:SOT669")
      (libsource (lib "eagle-import") (part "PSMN7R0-60YS"))
    )
    (comp (ref "R601")
      (value "10R")
      (footprint "eagle-import:0603")
      (libsource (lib "eagle-import") (part "RESISTOR0603"))
    )
    (comp (ref "R602")
      (value "100K")
      (footprint "eagle-import:0603")
      (libsource (lib "eagle-import") (part "RESISTOR0603"))
    )
    (comp (ref "R603")
      (value "1M")
      (footprint "eagle-import:0603")
      (libsource (lib "eagle-import") (part "RESISTOR0603"))
    )
    (comp (ref "R604")
      (value "10K")
      (footprint "eagle-import:0603")
      (libsource (lib "eagle-import") (part "330OHM-0603-1/10W-1%"))
    )
    (comp (ref "R605")
      (value "560r")
      (footprint "eagle-import:0603")
      (libsource (lib "eagle-import") (part "330OHM-0603-1/10W-1%"))
    )
    (comp (ref "R606")
      (value "560r")
      (footprint "eagle-import:0603")
      (libsource (lib "eagle-import") (part "330OHM-0603-1/10W-1%"))
    )
    (comp (ref "R607")
      (value "560r")
      (footprint "eagle-import:0603")
      (libsource (lib "eagle-import") (part "330OHM-0603-1/10W-1%"))
    )
    (comp (ref "S601")
      (value "RST")
      (footprint "eagle-import:TACTILE_SWITCH_SMD_5.2MM")
      (libsource (lib "eagle-import") (part "MOMENTARY-SWITCH-SPST-SMD-5.2-REDUNDANT"))
    )
    (comp (ref "S602")
      (value "SWITCH-SPDT-SMD-AYZ0202")
      (footprint "eagle-import:SWITCH_DPDT_SMD_AYZ0202")
      (libsource (lib "eagle-import") (part "SWITCH-SPDT-SMD-AYZ0202"))
    )
    (comp (ref "TP601")
      (value "PTR1TP20R")
      (footprint "eagle-import:TP20R")
      (libsource (lib "eagle-import") (part "PTR1TP20R"))
    )
    (comp (ref "TP602")
      (value "PTR1TP20R")
      (footprint "eagle-import:TP20R")
      (libsource (lib "eagle-import") (part "PTR1TP20R"))
    )
    (comp (ref "TP603")
      (value "PTR1TP20R")
      (footprint "eagle-import:TP20R")
      (libsource (lib "eagle-import") (part "PTR1TP20R"))
    )
    (comp (ref "TP604")
      (value "PTR1TP20R")
      (footprint "eagle-import:TP20R")
      (libsource (lib "eagle-import") (part "PTR1TP20R"))
    )
    (comp (ref "U601")
      (value "74HC1G04")
      (footprint "eagle-import:SOT353")
      (libsource (lib "eagle-import") (part "741G04HC"))
    )
    (comp (ref "U602")
      (value "SN74C1G08-DCK")
      (footprint "eagle-import:SC-70-5")
      (libsource (lib "eagle-import") (part "SN74C1G08-DCK"))
    )
    (comp (ref "U603")
      (value "ATTINY25-20SSUR")
      (footprint "eagle-import:SOIC8")
      (libsource (lib "eagle-import") (part "ATTINY45-SMT-NARROW"))
    )
    (comp (ref "U604")
      (value "MIC5205")
      (footprint "eagle-import:SOT23-5")
      (libsource (lib "eagle-import") (part "V_REG_MIC52055V"))
    )
    (comp (ref "C1601")
      (value "100uF")
      (footprint "eagle-import:PANASONIC_D")
      (libsource (lib "eagle-import") (part "100UF-POLAR-25V-20%(ELEC)"))
    )
    (comp (ref "C1602")
      (value "100uF")
      (footprint "eagle-import:PANASONIC_D")
      (libsource (lib "eagle-import") (part "100UF-POLAR-25V-20%(ELEC)"))
    )
    (comp (ref "C1603")
      (value "100uF")
      (footprint "eagle-import:PANASONIC_D")
      (libsource (lib "eagle-import") (part "100UF-POLAR-25V-20%(ELEC)"))
    )
    (comp (ref "C1604")
      (value "0.1uF")
      (footprint "eagle-import:0603")
      (libsource (lib "eagle-import") (part "0.1UF-0603-25V-5%"))
    )
    (comp (ref "D1601")
      (value "SMAJ30A")
      (footprint "eagle-import:SMADIODE")
      (libsource (lib "eagle-import") (part "DIODESMA"))
    )
    (comp (ref "J1601")
      (value "CONN_02")
      (footprint "eagle-import:1X02")
      (libsource (lib "eagle-import") (part "CONN_02"))
    )
    (comp (ref "J1602")
      (value "CONN_02")
      (footprint "eagle-import:1X02")
      (libsource (lib "eagle-import") (part "CONN_02"))
    )
    (comp (ref "J1603")
      (value "CONN_02")
      (footprint "eagle-import:1X02")
      (libsource (lib "eagle-import") (part "CONN_02"))
    )
    (comp (ref "J1604")
      (value "CONN_02")
      (footprint "eagle-import:1X02")
      (libsource (lib "eagle-import") (part "CONN_02"))
    )
    (comp (ref "J1605")
      (value "CONN_02")
      (footprint "eagle-import:1X02")
      (libsource (lib "eagle-import") (part "CONN_02"))
    )
    (comp (ref "J1606")
      (value "CONN_02")
      (footprint "eagle-import:1X02")
      (libsource (lib "eagle-import") (part "CONN_02"))
    )
    (comp (ref "J1607")
      (value "CONN_02")
      (footprint "eagle-import:1X02")
      (libsource (lib "eagle-import") (part "CONN_02"))
    )
    (comp (ref "J1608")
      (value "CONN_02")
      (footprint "eagle-import:1X02")
      (libsource (lib "eagle-import") (part "CONN_02"))
    )
    (comp (ref "J1609")
      (value "CONN_02")
      (footprint "eagle-import:1X02")
      (libsource (lib "eagle-import") (part "CONN_02"))
    )
    (comp (ref "J1610")
      (value "CONN_02")
      (footprint "eagle-import:1X02")
      (libsource (lib "eagle-import") (part "CONN_02"))
    )
    (comp (ref "J1611")
      (value "CONN_02")
      (footprint "eagle-import:1X02")
      (libsource (lib "eagle-import") (part "CONN_02"))
    )
    (comp (ref "J1612")
      (value "CONN_02")
      (footprint "eagle-import:1X02")
      (libsource (lib "eagle-import") (part "CONN_02"))
    )
    (comp (ref "J1613")
      (value "CONN_02")
      (footprint "eagle-import:1X02")
      (libsource (lib "eagle-import") (part "CONN_02"))
    )
    (comp (ref "J1614")
      (value "CONN_02")
      (footprint "eagle-import:1X02")
      (libsource (lib "eagle-import") (part "CONN_02"))
    )
    (comp (ref "X1601")
      (value "MSTBA2")
      (footprint "eagle-import:MSTBA2")
      (fields (field (name "MF") "FARNELL") (field (name "MPN") "1757242"))
      (libsource (lib "eagle-import") (part "MSTBA2"))
    )
    (comp (ref "C1101")
      (value "0.1uF")
      (footprint "eagle-import:0603")
      (libsource (lib "eagle-import") (part "0.1UF-0603-25V-5%"))
    )
    (comp (ref "C1102")
      (value "0.33uF")
      (footprint "eagle-import:0603")
      (libsource (lib "eagle-import") (part "0.1UF-0603-25V-(+80/-20%)"))
    )
    (comp (ref "C1103")
      (value "0.1uF")
      (footprint "eagle-import:0603")
      (libsource (lib "eagle-import") (part "0.1UF-0603-100V-10%"))
    )
    (comp (ref "D1101")
      (value "GREEN")
      (footprint "eagle-import:LED-0603")
      (libsource (lib "eagle-import") (part "LED-GREEN0603"))
    )
    (comp (ref "D1102")
      (value "YELLOW")
      (footprint "eagle-import:LED-0603")
      (libsource (lib "eagle-import") (part "LED-YELLOW0603"))
    )
    (comp (ref "D1103")
      (value "RED")
      (footprint "eagle-import:LED-0603")
      (libsource (lib "eagle-import") (part "LED-RED0603"))
    )
    (comp (ref "IC1101")
      (value "7805DT")
      (footprint "eagle-import:TO252")
      (libsource (lib "eagle-import") (part "78DT05"))
    )
    (comp (ref "J1101")
      (value "CONN_02LOCK")
      (footprint "eagle-import:1X02_LOCK")
      (libsource (lib "eagle-import") (part "CONN_02LOCK"))
    )
    (comp (ref "J1102")
      (value "CONN_02LOCK")
      (footprint "eagle-import:1X02_LOCK")
      (libsource (lib "eagle-import") (part "CONN_02LOCK"))
    )
    (comp (ref "J1103")
      (value "CONN_02LOCK")
      (footprint "eagle-import:1X02_LOCK")
      (libsource (lib "eagle-import") (part "CONN_02LOCK"))
    )
    (comp (ref "J1104")
      (value "ICSP_HEADER")
      (footprint "eagle-import:2X3")
      (libsource (lib "eagle-import") (part "AVR_SPI_PROG_3X2PTH"))
    )
    (comp (ref "R1101")
      (value "10K")
      (footprint "eagle-import:0603")
      (libsource (lib "eagle-import") (part "RESISTOR0603"))
    )
    (comp (ref "R1102")
      (value "10K")
      (footprint "eagle-import:0603")
      (libsource (lib "eagle-import") (part "RESISTOR0603"))
    )
    (comp (ref "R1103")
      (value "10K")
      (footprint "eagle-import:0603")
      (libsource (lib "eagle-import") (part "330OHM-0603-1/10W-1%"))
    )
    (comp (ref "R1104")
      (value "560r")
      (footprint "eagle-import:0603")
      (libsource (lib "eagle-import") (part "330OHM-0603-1/10W-1%"))
    )
    (comp (ref "R1105")
      (value "560r")
      (footprint "eagle-import:0603")
      (libsource (lib "eagle-import") (part "330OHM-0603-1/10W-1%"))
    )
    (comp (ref "R1106")
      (value "560r")
      (footprint "eagle-import:0603")
      (libsource (lib "eagle-import") (part "330OHM-0603-1/10W-1%"))
    )
    (comp (ref "S1101")
      (value "RST")
      (footprint "eagle-import:TACTILE_SWITCH_SMD_5.2MM")
      (libsource (lib "eagle-import") (part "MOMENTARY-SWITCH-SPST-SMD-5.2-REDUNDANT"))
    )
    (comp (ref "S1102")
      (value "SWITCH-SPDT-SMD-AYZ0202")
      (footprint "eagle-import:SWITCH_DPDT_SMD_AYZ0202")
      (libsource (lib "eagle-import") (part "SWITCH-SPDT-SMD-AYZ0202"))
    )
    (comp (ref "TP1101")
      (value "PTR1TP20R")
      (footprint "eagle-import:TP20R")
      (libsource (lib "eagle-import") (part "PTR1TP20R"))
    )
    (comp (ref "TP1102")
      (value "PTR1TP20R")
      (footprint "eagle-import:TP20R")
      (libsource (lib "eagle-import") (part "PTR1TP20R"))
    )
    (comp (ref "U1101")
      (value "DRV8835")
      (footprint "eagle-import:WSON-12")
      (libsource (lib "eagle-import") (part "DRV883X"))
    )
    (comp (ref "U1102")
      (value "ATTINY25-20SSUR")
      (footprint "eagle-import:SOIC8")
      (libsource (lib "eagle-import") (part "ATTINY45-SMT-NARROW"))
    )
    (comp (ref "C1501")
      (value "0.33uF")
      (footprint "eagle-import:0603")
      (libsource (lib "eagle-import") (part "0.1UF-0603-25V-(+80/-20%)"))
    )
    (comp (ref "C1502")
      (value "0.1uF")
      (footprint "eagle-import:0603")
      (libsource (lib "eagle-import") (part "0.1UF-0603-25V-(+80/-20%)"))
    )
    (comp (ref "D1501")
      (value "YELLOW")
      (footprint "eagle-import:LED-0603")
      (libsource (lib "eagle-import") (part "LED-YELLOW0603"))
    )
    (comp (ref "D1502")
      (value "RED")
      (footprint "eagle-import:LED-0603")
      (libsource (lib "eagle-import") (part "LED-RED0603"))
    )
    (comp (ref "IC1501")
      (value "7805DT")
      (footprint "eagle-import:TO252")
      (libsource (lib "eagle-import") (part "78DT05"))
    )
    (comp (ref "J1501")
      (value "CONN_03LOCK")
      (footprint "eagle-import:1X03_LOCK")
      (libsource (lib "eagle-import") (part "CONN_03LOCK"))
    )
    (comp (ref "R1501")
      (value "10K")
      (footprint "eagle-import:0603")
      (libsource (lib "eagle-import") (part "RESISTOR0603"))
    )
    (comp (ref "R1502")
      (value "560r")
      (footprint "eagle-import:0603")
      (libsource (lib "eagle-import") (part "330OHM-0603-1/10W-1%"))
    )
    (comp (ref "R1503")
      (value "560r")
      (footprint "eagle-import:0603")
      (libsource (lib "eagle-import") (part "330OHM-0603-1/10W-1%"))
    )
    (comp (ref "TP1501")
      (value "PTR1TP20R")
      (footprint "eagle-import:TP20R")
      (libsource (lib "eagle-import") (part "PTR1TP20R"))
    )
    (comp (ref "C701")
      (value "0.1uF")
      (footprint "eagle-import:0603")
      (libsource (lib "eagle-import") (part "0.1UF-0603-25V-5%"))
    )
    (comp (ref "C702")
      (value "0.1uF")
      (footprint "eagle-import:0603")
      (libsource (lib "eagle-import") (part "0.1UF-0603-25V-5%"))
    )
    (comp (ref "C703")
      (value "2.2uF")
      (footprint "eagle-import:EIA3216")
      (libsource (lib "eagle-import") (part "10UF-POLAR-EIA3216-16V-10%(TANT)"))
    )
    (comp (ref "D701")
      (value "GREEN")
      (footprint "eagle-import:LED-0603")
      (libsource (lib "eagle-import") (part "LED-GREEN0603"))
    )
    (comp (ref "D702")
      (value "YELLOW")
      (footprint "eagle-import:LED-0603")
      (libsource (lib "eagle-import") (part "LED-YELLOW0603"))
    )
    (comp (ref "D703")
      (value "RED")
      (footprint "eagle-import:LED-0603")
      (libsource (lib "eagle-import") (part "LED-RED0603"))
    )
    (comp (ref "J701")
      (value "CONN_03")
      (footprint "eagle-import:1X03")
      (libsource (lib "eagle-import") (part "CONN_03"))
    )
    (comp (ref "J702")
      (value "CONN_02LOCK")
      (footprint "eagle-import:1X02_LOCK")
      (libsource (lib "eagle-import") (part "CONN_02LOCK"))
    )
    (comp (ref "J703")
      (value "ICSP_HEADER")
      (footprint "eagle-import:2X3")
      (libsource (lib "eagle-import") (part "AVR_SPI_PROG_3X2PTH"))
    )
    (comp (ref "J704")
      (value "ICSP_HEADER")
      (footprint "eagle-import:2X3")
      (libsource (lib "eagle-import") (part "AVR_SPI_PROG_3X2PTH"))
    )
    (comp (ref "R701")
      (value "330r")
      (footprint "eagle-import:0603")
      (libsource (lib "eagle-import") (part "RESISTOR0603"))
    )
    (comp (ref "R702")
      (value "33k")
      (footprint "eagle-import:0603")
      (libsource (lib "eagle-import") (part "RESISTOR0603"))
    )
    (comp (ref "R703")
      (value "10K")
      (footprint "eagle-import:0603")
      (libsource (lib "eagle-import") (part "330OHM-0603-1/10W-1%"))
    )
    (comp (ref "R704")
      (value "10K")
      (footprint "eagle-import:0603")
      (libsource (lib "eagle-import") (part "330OHM-0603-1/10W-1%"))
    )
    (comp (ref "R705")
      (value "560r")
      (footprint "eagle-import:0603")
      (libsource (lib "eagle-import") (part "330OHM-0603-1/10W-1%"))
    )
    (comp (ref "R706")
      (value "560r")
      (footprint "eagle-import:0603")
      (libsource (lib "eagle-import") (part "330OHM-0603-1/10W-1%"))
    )
    (comp (ref "R707")
      (value "560r")
      (footprint "eagle-import:0603")
      (libsource (lib "eagle-import") (part "330OHM-0603-1/10W-1%"))
    )
    (comp (ref "S701")
      (value "RST")
      (footprint "eagle-import:TACTILE_SWITCH_SMD_5.2MM")
      (libsource (lib "eagle-import") (part "MOMENTARY-SWITCH-SPST-SMD-5.2-REDUNDANT"))
    )
    (comp (ref "S702")
      (value "RST")
      (footprint "eagle-import:TACTILE_SWITCH_SMD_5.2MM")
      (libsource (lib "eagle-import") (part "MOMENTARY-SWITCH-SPST-SMD-5.2-REDUNDANT"))
    )
    (comp (ref "S703")
      (value "SWITCH-SPDT-SMD-AYZ0202")
      (footprint "eagle-import:SWITCH_DPDT_SMD_AYZ0202")
      (libsource (lib "eagle-import") (part "SWITCH-SPDT-SMD-AYZ0202"))
    )
    (comp (ref "TP701")
      (value "PTR1TP20R")
      (footprint "eagle-import:TP20R")
      (libsource (lib "eagle-import") (part "PTR1TP20R"))
    )
    (comp (ref "TP702")
      (value "PTR1TP20R")
      (footprint "eagle-import:TP20R")
      (libsource (lib "eagle-import") (part "PTR1TP20R"))
    )
    (comp (ref "TP703")
      (value "PTR1TP20R")
      (footprint "eagle-import:TP20R")
      (libsource (lib "eagle-import") (part "PTR1TP20R"))
    )
    (comp (ref "U701")
      (value "ATTINY25-20SSUR")
      (footprint "eagle-import:SOIC8")
      (libsource (lib "eagle-import") (part "ATTINY45-SMT-NARROW"))
    )
    (comp (ref "U702")
      (value "ATTINY25-20SSUR")
      (footprint "eagle-import:SOIC8")
      (libsource (lib "eagle-import") (part "ATTINY45-SMT-NARROW"))
    )
    (comp (ref "U703")
      (value "MIC5205")
      (footprint "eagle-import:SOT23-5")
      (libsource (lib "eagle-import") (part "V_REG_MIC52055V"))
    )
    (comp (ref "C901")
      (value "0.1uF")
      (footprint "eagle-import:0603")
      (libsource (lib "eagle-import") (part "0.1UF-0603-25V-5%"))
    )
    (comp (ref "C902")
      (value "2.2uF")
      (footprint "eagle-import:EIA3216")
      (libsource (lib "eagle-import") (part "10UF-POLAR-EIA3216-16V-10%(TANT)"))
    )
    (comp (ref "D901")
      (value "SK310A-TP")
      (footprint "eagle-import:SMADIODE")
      (libsource (lib "eagle-import") (part "DIODESMA"))
    )
    (comp (ref "D902")
      (value "GREEN")
      (footprint "eagle-import:LED-0603")
      (libsource (lib "eagle-import") (part "LED-GREEN0603"))
    )
    (comp (ref "D903")
      (value "YELLOW")
      (footprint "eagle-import:LED-0603")
      (libsource (lib "eagle-import") (part "LED-YELLOW0603"))
    )
    (comp (ref "D904")
      (value "RED")
      (footprint "eagle-import:LED-0603")
      (libsource (lib "eagle-import") (part "LED-RED0603"))
    )
    (comp (ref "J901")
      (value "CONN_02LOCK")
      (footprint "eagle-import:1X02_LOCK")
      (libsource (lib "eagle-import") (part "CONN_02LOCK"))
    )
    (comp (ref "J902")
      (value "CONN_023.5MM_LOCK")
      (footprint "eagle-import:SCREWTERMINAL-3.5MM-2_LOCK")
      (libsource (lib "eagle-import") (part "CONN_023.5MM_LOCK"))
    )
    (comp (ref "J903")
      (value "ICSP_HEADER")
      (footprint "eagle-import:2X3")
      (libsource (lib "eagle-import") (part "AVR_SPI_PROG_3X2PTH"))
    )
    (comp (ref "Q901")
      (value "PSMN7R0-60YS")
      (footprint "eagle-import:SOT669")
      (libsource (lib "eagle-import") (part "PSMN7R0-60YS"))
    )
    (comp (ref "R901")
      (value "10R")
      (footprint "eagle-import:0603")
      (libsource (lib "eagle-import") (part "RESISTOR0603"))
    )
    (comp (ref "R902")
      (value "100K")
      (footprint "eagle-import:0603")
      (libsource (lib "eagle-import") (part "RESISTOR0603"))
    )
    (comp (ref "R903")
      (value "10K")
      (footprint "eagle-import:0603")
      (libsource (lib "eagle-import") (part "RESISTOR0603"))
    )
    (comp (ref "R904")
      (value "10K")
      (footprint "eagle-import:0603")
      (libsource (lib "eagle-import") (part "330OHM-0603-1/10W-1%"))
    )
    (comp (ref "R905")
      (value "560r")
      (footprint "eagle-import:0603")
      (libsource (lib "eagle-import") (part "330OHM-0603-1/10W-1%"))
    )
    (comp (ref "R906")
      (value "560r")
      (footprint "eagle-import:0603")
      (libsource (lib "eagle-import") (part "330OHM-0603-1/10W-1%"))
    )
    (comp (ref "R907")
      (value "560r")
      (footprint "eagle-import:0603")
      (libsource (lib "eagle-import") (part "330OHM-0603-1/10W-1%"))
    )
    (comp (ref "S901")
      (value "RST")
      (footprint "eagle-import:TACTILE_SWITCH_SMD_5.2MM")
      (libsource (lib "eagle-import") (part "MOMENTARY-SWITCH-SPST-SMD-5.2-REDUNDANT"))
    )
    (comp (ref "S902")
      (value "SWITCH-SPDT-SMD-AYZ0202")
      (footprint "eagle-import:SWITCH_DPDT_SMD_AYZ0202")
      (libsource (lib "eagle-import") (part "SWITCH-SPDT-SMD-AYZ0202"))
    )
    (comp (ref "TP901")
      (value "PTR1TP20R")
      (footprint "eagle-import:TP20R")
      (libsource (lib "eagle-import") (part "PTR1TP20R"))
    )
    (comp (ref "TP902")
      (value "PTR1TP20R")
      (footprint "eagle-import:TP20R")
      (libsource (lib "eagle-import") (part "PTR1TP20R"))
    )
    (comp (ref "U901")
      (value "ATTINY25-20SSUR")
      (footprint "eagle-import:SOIC8")
      (libsource (lib "eagle-import") (part "ATTINY45-SMT-NARROW"))
    )
    (comp (ref "U902")
      (value "MIC5205")
      (footprint "eagle-import:SOT23-5")
      (libsource (lib "eagle-import") (part "V_REG_MIC52055V"))
    )
  )
  (nets
    (net (code "1") (name "BALLOON_IN") (class "Default")
      (node (ref "D1202") (pin "A") (pinfunction "A_A") (pintype "passive"))
      (node (ref "J1611") (pin "1") (pinfunction "1_1") (pintype "passive"))
      (node (ref "U1202") (pin "2") (pinfunction "PB3(ADC3)_2") (pintype "bidirectional"))
    )
    (net (code "2") (name "BALLOON_MISO") (class "Default")
      (node (ref "J1204") (pin "1") (pinfunction "1_1") (pintype "passive"))
      (node (ref "U1201") (pin "9") (pinfunction "AIN2/EN_9") (pintype "bidirectional"))
      (node (ref "U1202") (pin "6") (pinfunction "PB1(MISO)_6") (pintype "bidirectional"))
    )
    (net (code "3") (name "BALLOON_MOSI") (class "Default")
      (node (ref "J1204") (pin "4") (pinfunction "4_4") (pintype "passive"))
      (node (ref "U1201") (pin "10") (pinfunction "AIN1/PH_10") (pintype "bidirectional"))
      (node (ref "U1202") (pin "5") (pinfunction "PB0(MOSI)_5") (pintype "bidirectional"))
    )
    (net (code "4") (name "BALLOON_OUT") (class "Default")
      (node (ref "D1201") (pin "A") (pinfunction "A_A") (pintype "passive"))
      (node (ref "J1201") (pin "2") (pinfunction "2_2") (pintype "passive"))
      (node (ref "J1612") (pin "2") (pinfunction "2_2") (pintype "passive"))
      (node (ref "R1201") (pin "1") (pinfunction "1_1") (pintype "passive"))
      (node (ref "S1202") (pin "2") (pinfunction "P_2") (pintype "passive"))
    )
    (net (code "5") (name "BALLOON_RST") (class "Default")
      (node (ref "J1204") (pin "5") (pinfunction "5_5") (pintype "passive"))
      (node (ref "R1203") (pin "1") (pinfunction "1_1") (pintype "passive"))
      (node (ref "S1201") (pin "3") (pinfunction "2_3") (pintype "passive"))
      (node (ref "S1201") (pin "4") (pinfunction "2_4") (pintype "passive"))
      (node (ref "U1202") (pin "1") (pinfunction "PB5(NRES)_1") (pintype "bidirectional"))
    )
    (net (code "6") (name "BALLOON_SCK") (class "Default")
      (node (ref "J1202") (pin "2") (pinfunction "2_2") (pintype "passive"))
      (node (ref "J1204") (pin "3") (pinfunction "3_3") (pintype "passive"))
      (node (ref "R1202") (pin "1") (pinfunction "1_1") (pintype "passive"))
      (node (ref "U1202") (pin "7") (pinfunction "PB2(SCK/ADC1)_7") (pintype "bidirectional"))
    )
    (net (code "7") (name "BALLOON_VCC") (class "Default")
      (node (ref "C1201") (pin "2") (pinfunction "2_2") (pintype "passive"))
      (node (ref "C1203") (pin "1") (pinfunction "1_1") (pintype "passive"))
      (node (ref "D1203") (pin "A") (pinfunction "A_A") (pintype "passive"))
      (node (ref "IC1201") (pin "2") (pinfunction "VO_2") (pintype "passive"))
      (node (ref "J1201") (pin "1") (pinfunction "1_1") (pintype "passive"))
      (node (ref "J1202") (pin "1") (pinfunction "1_1") (pintype "passive"))
      (node (ref "J1204") (pin "2") (pinfunction "2_2") (pintype "passive"))
      (node (ref "R1203") (pin "2") (pinfunction "2_2") (pintype "passive"))
      (node (ref "S1202") (pin "1") (pinfunction "O_1") (pintype "passive"))
      (node (ref "TP1201") (pin "TP") (pinfunction "TP_TP") (pintype "input"))
      (node (ref "U1201") (pin "1") (pinfunction "VM_1") (pintype "bidirectional"))
      (node (ref "U1201") (pin "11") (pinfunction "MODE_11") (pintype "bidirectional"))
      (node (ref "U1201") (pin "12") (pinfunction "VCC_12") (pintype "bidirectional"))
      (node (ref "U1202") (pin "8") (pinfunction "VCC_8") (pintype "bidirectional"))
    )
    (net (code "8") (name "COIN_IN") (class "Default")
      (node (ref "D203") (pin "A") (pinfunction "A_A") (pintype "passive"))
      (node (ref "J1601") (pin "1") (pinfunction "1_1") (pintype "passive"))
      (node (ref "JP201") (pin "1") (pinfunction "1_1") (pintype "passive"))
      (node (ref "U201") (pin "2") (pinfunction "A_2") (pintype "bidirectional"))
    )
    (net (code "9") (name "COIN_MISO") (class "Default")
      (node (ref "J204") (pin "1") (pinfunction "1_1") (pintype "passive"))
      (node (ref "U202") (pin "6") (pinfunction "PB1(MISO)_6") (pintype "bidirectional"))
    )
    (net (code "10") (name "COIN_MOSI") (class "Default")
      (node (ref "J204") (pin "4") (pinfunction "4_4") (pintype "passive"))
      (node (ref "U202") (pin "5") (pinfunction "PB0(MOSI)_5") (pintype "bidirectional"))
    )
    (net (code "11") (name "COIN_OUT") (class "Default")
      (node (ref "D202") (pin "A") (pinfunction "A_A") (pintype "passive"))
      (node (ref "J1602") (pin "2") (pinfunction "2_2") (pintype "passive"))
      (node (ref "S202") (pin "2") (pinfunction "P_2") (pintype "passive"))
    )
    (net (code "12") (name "COIN_OUT_SWITCH") (class "Default")
      (node (ref "S202") (pin "3") (pinfunction "S_3") (pintype "passive"))
      (node (ref "U202") (pin "3") (pinfunction "PB4(ADC2)_3") (pintype "bidirectional"))
    )
    (net (code "13") (name "COIN_RST") (class "Default")
      (node (ref "J204") (pin "5") (pinfunction "5_5") (pintype "passive"))
      (node (ref "R204") (pin "1") (pinfunction "1_1") (pintype "passive"))
      (node (ref "S201") (pin "3") (pinfunction "2_3") (pintype "passive"))
      (node (ref "S201") (pin "4") (pinfunction "2_4") (pintype "passive"))
      (node (ref "U202") (pin "1") (pinfunction "PB5(NRES)_1") (pintype "bidirectional"))
    )
    (net (code "14") (name "COIN_SCK") (class "Default")
      (node (ref "J201") (pin "1") (pinfunction "1_1") (pintype "passive"))
      (node (ref "J204") (pin "3") (pinfunction "3_3") (pintype "passive"))
      (node (ref "R203") (pin "1") (pinfunction "1_1") (pintype "passive"))
      (node (ref "U202") (pin "7") (pinfunction "PB2(SCK/ADC1)_7") (pintype "bidirectional"))
    )
    (net (code "15") (name "COIN_VCC") (class "Default")
      (node (ref "C201") (pin "2") (pinfunction "2_2") (pintype "passive"))
      (node (ref "C202") (pin "+") (pinfunction "+_+") (pintype "passive"))
      (node (ref "D204") (pin "A") (pinfunction "A_A") (pintype "passive"))
      (node (ref "J204") (pin "2") (pinfunction "2_2") (pintype "passive"))
      (node (ref "R203") (pin "2") (pinfunction "2_2") (pintype "passive"))
      (node (ref "R204") (pin "2") (pinfunction "2_2") (pintype "passive"))
      (node (ref "S202") (pin "1") (pinfunction "O_1") (pintype "passive"))
      (node (ref "TP202") (pin "TP") (pinfunction "TP_TP") (pintype "input"))
      (node (ref "U201") (pin "5") (pinfunction "P$V+_5") (pintype "bidirectional"))
      (node (ref "U202") (pin "8") (pinfunction "VCC_8") (pintype "bidirectional"))
      (node (ref "U203") (pin "5") (pinfunction "OUT_5") (pintype "passive"))
    )
    (net (code "16") (name "EMAG_IN") (class "Default")
      (node (ref "D803") (pin "A") (pinfunction "A_A") (pintype "passive"))
      (node (ref "J1607") (pin "1") (pinfunction "1_1") (pintype "passive"))
      (node (ref "U802") (pin "1") (pinfunction "A_1") (pintype "input"))
    )
    (net (code "17") (name "EMAG_OUT") (class "Default")
      (node (ref "D802") (pin "A") (pinfunction "A_A") (pintype "passive"))
      (node (ref "J1608") (pin "2") (pinfunction "2_2") (pintype "passive"))
      (node (ref "J801") (pin "1") (pinfunction "1_1") (pintype "passive"))
      (node (ref "R801") (pin "2") (pinfunction "2_2") (pintype "passive"))
      (node (ref "S801") (pin "2") (pinfunction "P_2") (pintype "passive"))
      (node (ref "U801") (pin "2") (pinfunction "A_2") (pintype "bidirectional"))
    )
    (net (code "18") (name "EMAG_VCC") (class "Default")
      (node (ref "C801") (pin "+") (pinfunction "+_+") (pintype "passive"))
      (node (ref "D804") (pin "A") (pinfunction "A_A") (pintype "passive"))
      (node (ref "J801") (pin "2") (pinfunction "2_2") (pintype "passive"))
      (node (ref "S801") (pin "1") (pinfunction "O_1") (pintype "passive"))
      (node (ref "TP801") (pin "TP") (pinfunction "TP_TP") (pintype "input"))
      (node (ref "U801") (pin "5") (pinfunction "P$V+_5") (pintype "bidirectional"))
      (node (ref "U802") (pin "5") (pinfunction "VCC_5") (pintype "power_in"))
      (node (ref "U803") (pin "5") (pinfunction "OUT_5") (pintype "passive"))
    )
    (net (code "19") (name "ENDO_IN") (class "Default")
      (node (ref "D503") (pin "A") (pinfunction "A_A") (pintype "passive"))
      (node (ref "J1604") (pin "1") (pinfunction "1_1") (pintype "passive"))
      (node (ref "U502") (pin "1") (pinfunction "A_1") (pintype "input"))
    )
    (net (code "20") (name "ENDO_MISO") (class "Default")
      (node (ref "J503") (pin "1") (pinfunction "1_1") (pintype "passive"))
      (node (ref "U503") (pin "6") (pinfunction "PB1(MISO)_6") (pintype "bidirectional"))
    )
    (net (code "21") (name "ENDO_MOSI") (class "Default")
      (node (ref "J503") (pin "4") (pinfunction "4_4") (pintype "passive"))
      (node (ref "U503") (pin "5") (pinfunction "PB0(MOSI)_5") (pintype "bidirectional"))
    )
    (net (code "22") (name "ENDO_OUT") (class "Default")
      (node (ref "D502") (pin "A") (pinfunction "A_A") (pintype "passive"))
      (node (ref "J1605") (pin "2") (pinfunction "2_2") (pintype "passive"))
      (node (ref "S502") (pin "2") (pinfunction "P_2") (pintype "passive"))
      (node (ref "U501") (pin "2") (pinfunction "A_2") (pintype "bidirectional"))
    )
    (net (code "23") (name "ENDO_OUT_SWITCH") (class "Default")
      (node (ref "S502") (pin "3") (pinfunction "S_3") (pintype "passive"))
      (node (ref "U503") (pin "3") (pinfunction "PB4(ADC2)_3") (pintype "bidirectional"))
    )
    (net (code "24") (name "ENDO_RST") (class "Default")
      (node (ref "J503") (pin "5") (pinfunction "5_5") (pintype "passive"))
      (node (ref "R504") (pin "1") (pinfunction "1_1") (pintype "passive"))
      (node (ref "S501") (pin "3") (pinfunction "2_3") (pintype "passive"))
      (node (ref "S501") (pin "4") (pinfunction "2_4") (pintype "passive"))
      (node (ref "U503") (pin "1") (pinfunction "PB5(NRES)_1") (pintype "bidirectional"))
    )
    (net (code "25") (name "ENDO_SCK") (class "Default")
      (node (ref "J503") (pin "3") (pinfunction "3_3") (pintype "passive"))
      (node (ref "R501") (pin "2") (pinfunction "2_2") (pintype "passive"))
      (node (ref "U503") (pin "7") (pinfunction "PB2(SCK/ADC1)_7") (pintype "bidirectional"))
    )
    (net (code "26") (name "ENDO_VCC") (class "Default")
      (node (ref "C501") (pin "2") (pinfunction "2_2") (pintype "passive"))
      (node (ref "C502") (pin "+") (pinfunction "+_+") (pintype "passive"))
      (node (ref "D504") (pin "A") (pinfunction "A_A") (pintype "passive"))
      (node (ref "J503") (pin "2") (pinfunction "2_2") (pintype "passive"))
      (node (ref "R504") (pin "2") (pinfunction "2_2") (pintype "passive"))
      (node (ref "S502") (pin "1") (pinfunction "O_1") (pintype "passive"))
      (node (ref "TP503") (pin "TP") (pinfunction "TP_TP") (pintype "input"))
      (node (ref "U501") (pin "5") (pinfunction "P$V+_5") (pintype "bidirectional"))
      (node (ref "U502") (pin "5") (pinfunction "VCC_5") (pintype "power_in"))
      (node (ref "U503") (pin "8") (pinfunction "VCC_8") (pintype "bidirectional"))
      (node (ref "U504") (pin "5") (pinfunction "OUT_5") (pintype "passive"))
    )
    (net (code "27") (name "END_IN") (class "Default")
      (node (ref "D1501") (pin "A") (pinfunction "A_A") (pintype "passive"))
      (node (ref "J1501") (pin "1") (pinfunction "1_1") (pintype "passive"))
      (node (ref "J1614") (pin "1") (pinfunction "1_1") (pintype "passive"))
      (node (ref "R1501") (pin "2") (pinfunction "2_2") (pintype "passive"))
    )
    (net (code "28") (name "END_VCC") (class "Default")
      (node (ref "C1502") (pin "1") (pinfunction "1_1") (pintype "passive"))
      (node (ref "D1502") (pin "A") (pinfunction "A_A") (pintype "passive"))
      (node (ref "IC1501") (pin "2") (pinfunction "VO_2") (pintype "passive"))
      (node (ref "J1501") (pin "2") (pinfunction "2_2") (pintype "passive"))
      (node (ref "TP1501") (pin "TP") (pinfunction "TP_TP") (pintype "input"))
    )
    (net (code "29") (name "EXO_IN") (class "Default")
      (node (ref "D303") (pin "A") (pinfunction "A_A") (pintype "passive"))
      (node (ref "J1602") (pin "1") (pinfunction "1_1") (pintype "passive"))
      (node (ref "U302") (pin "1") (pinfunction "A_1") (pintype "input"))
    )
    (net (code "30") (name "EXO_MISO") (class "Default")
      (node (ref "J301") (pin "1") (pinfunction "1_1") (pintype "passive"))
      (node (ref "U303") (pin "6") (pinfunction "PB1(MISO)_6") (pintype "bidirectional"))
    )
    (net (code "31") (name "EXO_MOSI") (class "Default")
      (node (ref "J301") (pin "4") (pinfunction "4_4") (pintype "passive"))
      (node (ref "U303") (pin "5") (pinfunction "PB0(MOSI)_5") (pintype "bidirectional"))
    )
    (net (code "32") (name "EXO_OUT") (class "Default")
      (node (ref "D302") (pin "A") (pinfunction "A_A") (pintype "passive"))
      (node (ref "J1603") (pin "2") (pinfunction "2_2") (pintype "passive"))
      (node (ref "S302") (pin "2") (pinfunction "P_2") (pintype "passive"))
      (node (ref "U301") (pin "2") (pinfunction "A_2") (pintype "bidirectional"))
    )
    (net (code "33") (name "EXO_OUT_SWITCH") (class "Default")
      (node (ref "S302") (pin "3") (pinfunction "S_3") (pintype "passive"))
      (node (ref "U303") (pin "3") (pinfunction "PB4(ADC2)_3") (pintype "bidirectional"))
    )
    (net (code "34") (name "EXO_RST") (class "Default")
      (node (ref "J301") (pin "5") (pinfunction "5_5") (pintype "passive"))
      (node (ref "R304") (pin "1") (pinfunction "1_1") (pintype "passive"))
      (node (ref "S301") (pin "3") (pinfunction "2_3") (pintype "passive"))
      (node (ref "S301") (pin "4") (pinfunction "2_4") (pintype "passive"))
      (node (ref "U303") (pin "1") (pinfunction "PB5(NRES)_1") (pintype "bidirectional"))
    )
    (net (code "35") (name "EXO_SCK") (class "Default")
      (node (ref "J301") (pin "3") (pinfunction "3_3") (pintype "passive"))
      (node (ref "R301") (pin "2") (pinfunction "2_2") (pintype "passive"))
      (node (ref "R303") (pin "1") (pinfunction "P$1_1") (pintype "bidirectional"))
      (node (ref "U303") (pin "7") (pinfunction "PB2(SCK/ADC1)_7") (pintype "bidirectional"))
    )
    (net (code "36") (name "EXO_VCC") (class "Default")
      (node (ref "C301") (pin "2") (pinfunction "2_2") (pintype "passive"))
      (node (ref "C302") (pin "+") (pinfunction "+_+") (pintype "passive"))
      (node (ref "D304") (pin "A") (pinfunction "A_A") (pintype "passive"))
      (node (ref "J301") (pin "2") (pinfunction "2_2") (pintype "passive"))
      (node (ref "Q301") (pin "3") (pinfunction "C_3") (pintype "passive"))
      (node (ref "R303") (pin "2") (pinfunction "P$2_2") (pintype "bidirectional"))
      (node (ref "R304") (pin "2") (pinfunction "2_2") (pintype "passive"))
      (node (ref "S302") (pin "1") (pinfunction "O_1") (pintype "passive"))
      (node (ref "U301") (pin "5") (pinfunction "P$V+_5") (pintype "bidirectional"))
      (node (ref "U302") (pin "5") (pinfunction "VCC_5") (pintype "power_in"))
      (node (ref "U303") (pin "8") (pinfunction "VCC_8") (pintype "bidirectional"))
      (node (ref "U304") (pin "5") (pinfunction "OUT_5") (pintype "passive"))
    )
    (net (code "37") (name "EXP_IN") (class "Default")
      (node (ref "D1003") (pin "A") (pinfunction "A_A") (pintype "passive"))
      (node (ref "J1609") (pin "1") (pinfunction "1_1") (pintype "passive"))
      (node (ref "U1001") (pin "2") (pinfunction "PB3(ADC3)_2") (pintype "bidirectional"))
    )
    (net (code "38") (name "EXP_MISO") (class "Default")
      (node (ref "J1005") (pin "1") (pinfunction "1_1") (pintype "passive"))
      (node (ref "U1001") (pin "6") (pinfunction "PB1(MISO)_6") (pintype "bidirectional"))
    )
    (net (code "39") (name "EXP_MOSI") (class "Default")
      (node (ref "J1005") (pin "4") (pinfunction "4_4") (pintype "passive"))
      (node (ref "R1001") (pin "1") (pinfunction "1_1") (pintype "passive"))
      (node (ref "R1002") (pin "1") (pinfunction "1_1") (pintype "passive"))
      (node (ref "U1001") (pin "5") (pinfunction "PB0(MOSI)_5") (pintype "bidirectional"))
    )
    (net (code "40") (name "EXP_OUT") (class "Default")
      (node (ref "D1002") (pin "A") (pinfunction "A_A") (pintype "passive"))
      (node (ref "J1004") (pin "2") (pinfunction "2_2") (pintype "passive"))
      (node (ref "J1610") (pin "2") (pinfunction "2_2") (pintype "passive"))
      (node (ref "R1004") (pin "1") (pinfunction "1_1") (pintype "passive"))
      (node (ref "S1002") (pin "2") (pinfunction "P_2") (pintype "passive"))
    )
    (net (code "41") (name "EXP_RST") (class "Default")
      (node (ref "J1005") (pin "5") (pinfunction "5_5") (pintype "passive"))
      (node (ref "R1005") (pin "1") (pinfunction "1_1") (pintype "passive"))
      (node (ref "S1001") (pin "3") (pinfunction "2_3") (pintype "passive"))
      (node (ref "S1001") (pin "4") (pinfunction "2_4") (pintype "passive"))
      (node (ref "U1001") (pin "1") (pinfunction "PB5(NRES)_1") (pintype "bidirectional"))
    )
    (net (code "42") (name "EXP_SCK") (class "Default")
      (node (ref "J1005") (pin "3") (pinfunction "3_3") (pintype "passive"))
      (node (ref "R1003") (pin "2") (pinfunction "2_2") (pintype "passive"))
      (node (ref "U1001") (pin "7") (pinfunction "PB2(SCK/ADC1)_7") (pintype "bidirectional"))
    )
    (net (code "43") (name "EXP_VCC") (class "Default")
      (node (ref "C1001") (pin "2") (pinfunction "2_2") (pintype "passive"))
      (node (ref "C1002") (pin "+") (pinfunction "+_+") (pintype "passive"))
      (node (ref "D1004") (pin "A") (pinfunction "A_A") (pintype "passive"))
      (node (ref "J1004") (pin "1") (pinfunction "1_1") (pintype "passive"))
      (node (ref "J1005") (pin "2") (pinfunction "2_2") (pintype "passive"))
      (node (ref "R1005") (pin "2") (pinfunction "2_2") (pintype "passive"))
      (node (ref "S1002") (pin "1") (pinfunction "O_1") (pintype "passive"))
      (node (ref "TP1001") (pin "TP") (pinfunction "TP_TP") (pintype "input"))
      (node (ref "U1001") (pin "8") (pinfunction "VCC_8") (pintype "bidirectional"))
      (node (ref "U1002") (pin "5") (pinfunction "OUT_5") (pintype "passive"))
    )
    (net (code "44") (name "GND") (class "Default")
      (node (ref "C1001") (pin "1") (pinfunction "1_1") (pintype "passive"))
      (node (ref "C1002") (pin "-") (pinfunction "-_-") (pintype "passive"))
      (node (ref "C101") (pin "-") (pinfunction "-_-") (pintype "passive"))
      (node (ref "C1101") (pin "1") (pinfunction "1_1") (pintype "passive"))
      (node (ref "C1102") (pin "1") (pinfunction "1_1") (pintype "passive"))
      (node (ref "C1103") (pin "2") (pinfunction "2_2") (pintype "passive"))
      (node (ref "C1201") (pin "1") (pinfunction "1_1") (pintype "passive"))
      (node (ref "C1202") (pin "1") (pinfunction "1_1") (pintype "passive"))
      (node (ref "C1203") (pin "2") (pinfunction "2_2") (pintype "passive"))
      (node (ref "C1301") (pin "1") (pinfunction "1_1") (pintype "passive"))
      (node (ref "C1302") (pin "1") (pinfunction "1_1") (pintype "passive"))
      (node (ref "C1303") (pin "2") (pinfunction "2_2") (pintype "passive"))
      (node (ref "C1401") (pin "-") (pinfunction "-_-") (pintype "passive"))
      (node (ref "C1501") (pin "1") (pinfunction "1_1") (pintype "passive"))
      (node (ref "C1502") (pin "2") (pinfunction "2_2") (pintype "passive"))
      (node (ref "C1601") (pin "-") (pinfunction "-_-") (pintype "passive"))
      (node (ref "C1602") (pin "-") (pinfunction "-_-") (pintype "passive"))
      (node (ref "C1603") (pin "-") (pinfunction "-_-") (pintype "passive"))
      (node (ref "C1604") (pin "2") (pinfunction "2_2") (pintype "passive"))
      (node (ref "C201") (pin "1") (pinfunction "1_1") (pintype "passive"))
      (node (ref "C202") (pin "-") (pinfunction "-_-") (pintype "passive"))
      (node (ref "C301") (pin "1") (pinfunction "1_1") (pintype "passive"))
      (node (ref "C302") (pin "-") (pinfunction "-_-") (pintype "passive"))
      (node (ref "C401") (pin "1") (pinfunction "1_1") (pintype "passive"))
      (node (ref "C402") (pin "-") (pinfunction "-_-") (pintype "passive"))
      (node (ref "C501") (pin "1") (pinfunction "1_1") (pintype "passive"))
      (node (ref "C502") (pin "-") (pinfunction "-_-") (pintype "passive"))
      (node (ref "C601") (pin "1") (pinfunction "1_1") (pintype "passive"))
      (node (ref "C602") (pin "-") (pinfunction "-_-") (pintype "passive"))
      (node (ref "C701") (pin "1") (pinfunction "1_1") (pintype "passive"))
      (node (ref "C702") (pin "1") (pinfunction "1_1") (pintype "passive"))
      (node (ref "C703") (pin "-") (pinfunction "-_-") (pintype "passive"))
      (node (ref "C801") (pin "-") (pinfunction "-_-") (pintype "passive"))
      (node (ref "C901") (pin "1") (pinfunction "1_1") (pintype "passive"))
      (node (ref "C902") (pin "-") (pinfunction "-_-") (pintype "passive"))
      (node (ref "D1601") (pin "A") (pinfunction "A_A") (pintype "passive"))
      (node (ref "D301") (pin "K") (pinfunction "C_K") (pintype "passive"))
      (node (ref "IC1101") (pin "3") (pinfunction "GND_3") (pintype "passive"))
      (node (ref "IC1201") (pin "3") (pinfunction "GND_3") (pintype "passive"))
      (node (ref "IC1301") (pin "3") (pinfunction "GND_3") (pintype "passive"))
      (node (ref "IC1501") (pin "3") (pinfunction "GND_3") (pintype "passive"))
      (node (ref "J1002") (pin "2") (pinfunction "2_2") (pintype "passive"))
      (node (ref "J1003") (pin "2") (pinfunction "2_2") (pintype "passive"))
      (node (ref "J1005") (pin "6") (pinfunction "6_6") (pintype "passive"))
      (node (ref "J1104") (pin "6") (pinfunction "6_6") (pintype "passive"))
      (node (ref "J1204") (pin "6") (pinfunction "6_6") (pintype "passive"))
      (node (ref "J1304") (pin "6") (pinfunction "6_6") (pintype "passive"))
      (node (ref "J1501") (pin "3") (pinfunction "3_3") (pintype "passive"))
      (node (ref "J201") (pin "3") (pinfunction "3_3") (pintype "passive"))
      (node (ref "J202") (pin "2") (pinfunction "2_2") (pintype "passive"))
      (node (ref "J204") (pin "6") (pinfunction "6_6") (pintype "passive"))
      (node (ref "J301") (pin "6") (pinfunction "6_6") (pintype "passive"))
      (node (ref "J401") (pin "6") (pinfunction "6_6") (pintype "passive"))
      (node (ref "J501") (pin "2") (pinfunction "2_2") (pintype "passive"))
      (node (ref "J503") (pin "6") (pinfunction "6_6") (pintype "passive"))
      (node (ref "J601") (pin "2") (pinfunction "2_2") (pintype "passive"))
      (node (ref "J603") (pin "6") (pinfunction "6_6") (pintype "passive"))
      (node (ref "J701") (pin "2") (pinfunction "2_2") (pintype "passive"))
      (node (ref "J703") (pin "6") (pinfunction "6_6") (pintype "passive"))
      (node (ref "J704") (pin "6") (pinfunction "6_6") (pintype "passive"))
      (node (ref "J903") (pin "6") (pinfunction "6_6") (pintype "passive"))
      (node (ref "Q1001") (pin "1") (pinfunction "S_1") (pintype "passive"))
      (node (ref "Q1001") (pin "2") (pinfunction "S_2") (pintype "passive"))
      (node (ref "Q1001") (pin "3") (pinfunction "S_3") (pintype "passive"))
      (node (ref "Q1401") (pin "1") (pinfunction "S_1") (pintype "passive"))
      (node (ref "Q1401") (pin "2") (pinfunction "S_2") (pintype "passive"))
      (node (ref "Q1401") (pin "3") (pinfunction "S_3") (pintype "passive"))
      (node (ref "Q201") (pin "1") (pinfunction "S_1") (pintype "passive"))
      (node (ref "Q201") (pin "2") (pinfunction "S_2") (pintype "passive"))
      (node (ref "Q201") (pin "3") (pinfunction "S_3") (pintype "passive"))
      (node (ref "Q501") (pin "1") (pinfunction "S_1") (pintype "passive"))
      (node (ref "Q501") (pin "2") (pinfunction "S_2") (pintype "passive"))
      (node (ref "Q501") (pin "3") (pinfunction "S_3") (pintype "passive"))
      (node (ref "Q601") (pin "1") (pinfunction "S_1") (pintype "passive"))
      (node (ref "Q601") (pin "2") (pinfunction "S_2") (pintype "passive"))
      (node (ref "Q601") (pin "3") (pinfunction "S_3") (pintype "passive"))
      (node (ref "Q801") (pin "1") (pinfunction "S_1") (pintype "passive"))
      (node (ref "Q801") (pin "2") (pinfunction "S_2") (pintype "passive"))
      (node (ref "Q801") (pin "3") (pinfunction "S_3") (pintype "passive"))
      (node (ref "Q901") (pin "1") (pinfunction "S_1") (pintype "passive"))
      (node (ref "Q901") (pin "2") (pinfunction "S_2") (pintype "passive"))
      (node (ref "Q901") (pin "3") (pinfunction "S_3") (pintype "passive"))
      (node (ref "R1002") (pin "2") (pinfunction "2_2") (pintype "passive"))
      (node (ref "R1004") (pin "2") (pinfunction "2_2") (pintype "passive"))
      (node (ref "R1006") (pin "1") (pinfunction "1_1") (pintype "passive"))
      (node (ref "R1007") (pin "1") (pinfunction "1_1") (pintype "passive"))
      (node (ref "R1008") (pin "1") (pinfunction "1_1") (pintype "passive"))
      (node (ref "R102") (pin "1") (pinfunction "1_1") (pintype "passive"))
      (node (ref "R103") (pin "1") (pinfunction "1_1") (pintype "passive"))
      (node (ref "R1101") (pin "2") (pinfunction "2_2") (pintype "passive"))
      (node (ref "R1102") (pin "2") (pinfunction "2_2") (pintype "passive"))
      (node (ref "R1104") (pin "1") (pinfunction "1_1") (pintype "passive"))
      (node (ref "R1105") (pin "1") (pinfunction "1_1") (pintype "passive"))
      (node (ref "R1106") (pin "1") (pinfunction "1_1") (pintype "passive"))
      (node (ref "R1201") (pin "2") (pinfunction "2_2") (pintype "passive"))
      (node (ref "R1202") (pin "2") (pinfunction "2_2") (pintype "passive"))
      (node (ref "R1204") (pin "1") (pinfunction "1_1") (pintype "passive"))
      (node (ref "R1205") (pin "1") (pinfunction "1_1") (pintype "passive"))
      (node (ref "R1206") (pin "1") (pinfunction "1_1") (pintype "passive"))
      (node (ref "R1301") (pin "2") (pinfunction "2_2") (pintype "passive"))
      (node (ref "R1302") (pin "2") (pinfunction "2_2") (pintype "passive"))
      (node (ref "R1304") (pin "1") (pinfunction "1_1") (pintype "passive"))
      (node (ref "R1305") (pin "1") (pinfunction "1_1") (pintype "passive"))
      (node (ref "R1306") (pin "1") (pinfunction "1_1") (pintype "passive"))
      (node (ref "R1401") (pin "2") (pinfunction "2_2") (pintype "passive"))
      (node (ref "R1403") (pin "2") (pinfunction "2_2") (pintype "passive"))
      (node (ref "R1404") (pin "1") (pinfunction "1_1") (pintype "passive"))
      (node (ref "R1405") (pin "1") (pinfunction "1_1") (pintype "passive"))
      (node (ref "R1406") (pin "1") (pinfunction "1_1") (pintype "passive"))
      (node (ref "R1501") (pin "1") (pinfunction "1_1") (pintype "passive"))
      (node (ref "R1502") (pin "1") (pinfunction "1_1") (pintype "passive"))
      (node (ref "R1503") (pin "1") (pinfunction "1_1") (pintype "passive"))
      (node (ref "R202") (pin "2") (pinfunction "2_2") (pintype "passive"))
      (node (ref "R205") (pin "1") (pinfunction "1_1") (pintype "passive"))
      (node (ref "R206") (pin "1") (pinfunction "1_1") (pintype "passive"))
      (node (ref "R207") (pin "1") (pinfunction "1_1") (pintype "passive"))
      (node (ref "R301") (pin "1") (pinfunction "1_1") (pintype "passive"))
      (node (ref "R305") (pin "1") (pinfunction "1_1") (pintype "passive"))
      (node (ref "R306") (pin "1") (pinfunction "1_1") (pintype "passive"))
      (node (ref "R307") (pin "1") (pinfunction "1_1") (pintype "passive"))
      (node (ref "R401") (pin "1") (pinfunction "1_1") (pintype "passive"))
      (node (ref "R404") (pin "2") (pinfunction "2_2") (pintype "passive"))
      (node (ref "R406") (pin "1") (pinfunction "1_1") (pintype "passive"))
      (node (ref "R407") (pin "1") (pinfunction "1_1") (pintype "passive"))
      (node (ref "R408") (pin "1") (pinfunction "1_1") (pintype "passive"))
      (node (ref "R503") (pin "2") (pinfunction "2_2") (pintype "passive"))
      (node (ref "R505") (pin "1") (pinfunction "1_1") (pintype "passive"))
      (node (ref "R506") (pin "1") (pinfunction "1_1") (pintype "passive"))
      (node (ref "R507") (pin "1") (pinfunction "1_1") (pintype "passive"))
      (node (ref "R602") (pin "2") (pinfunction "2_2") (pintype "passive"))
      (node (ref "R605") (pin "1") (pinfunction "1_1") (pintype "passive"))
      (node (ref "R606") (pin "1") (pinfunction "1_1") (pintype "passive"))
      (node (ref "R607") (pin "1") (pinfunction "1_1") (pintype "passive"))
      (node (ref "R705") (pin "1") (pinfunction "1_1") (pintype "passive"))
      (node (ref "R706") (pin "1") (pinfunction "1_1") (pintype "passive"))
      (node (ref "R707") (pin "1") (pinfunction "1_1") (pintype "passive"))
      (node (ref "R801") (pin "1") (pinfunction "1_1") (pintype "passive"))
      (node (ref "R803") (pin "2") (pinfunction "2_2") (pintype "passive"))
      (node (ref "R804") (pin "1") (pinfunction "1_1") (pintype "passive"))
      (node (ref "R805") (pin "1") (pinfunction "1_1") (pintype "passive"))
      (node (ref "R806") (pin "1") (pinfunction "1_1") (pintype "passive"))
      (node (ref "R902") (pin "2") (pinfunction "2_2") (pintype "passive"))
      (node (ref "R903") (pin "2") (pinfunction "2_2") (pintype "passive"))
      (node (ref "R905") (pin "1") (pinfunction "1_1") (pintype "passive"))
      (node (ref "R906") (pin "1") (pinfunction "1_1") (pintype "passive"))
      (node (ref "R907") (pin "1") (pinfunction "1_1") (pintype "passive"))
      (node (ref "S1001") (pin "1") (pinfunction "1_1") (pintype "passive"))
      (node (ref "S1001") (pin "2") (pinfunction "1_2") (pintype "passive"))
      (node (ref "S101") (pin "P$1") (pinfunction "1_P$1") (pintype "passive"))
      (node (ref "S1101") (pin "1") (pinfunction "1_1") (pintype "passive"))
      (node (ref "S1101") (pin "2") (pinfunction "1_2") (pintype "passive"))
      (node (ref "S1201") (pin "1") (pinfunction "1_1") (pintype "passive"))
      (node (ref "S1201") (pin "2") (pinfunction "1_2") (pintype "passive"))
      (node (ref "S1301") (pin "1") (pinfunction "1_1") (pintype "passive"))
      (node (ref "S1301") (pin "2") (pinfunction "1_2") (pintype "passive"))
      (node (ref "S201") (pin "1") (pinfunction "1_1") (pintype "passive"))
      (node (ref "S201") (pin "2") (pinfunction "1_2") (pintype "passive"))
      (node (ref "S301") (pin "1") (pinfunction "1_1") (pintype "passive"))
      (node (ref "S301") (pin "2") (pinfunction "1_2") (pintype "passive"))
      (node (ref "S401") (pin "1") (pinfunction "1_1") (pintype "passive"))
      (node (ref "S401") (pin "2") (pinfunction "1_2") (pintype "passive"))
      (node (ref "S501") (pin "1") (pinfunction "1_1") (pintype "passive"))
      (node (ref "S501") (pin "2") (pinfunction "1_2") (pintype "passive"))
      (node (ref "S601") (pin "1") (pinfunction "1_1") (pintype "passive"))
      (node (ref "S601") (pin "2") (pinfunction "1_2") (pintype "passive"))
      (node (ref "S701") (pin "1") (pinfunction "1_1") (pintype "passive"))
      (node (ref "S701") (pin "2") (pinfunction "1_2") (pintype "passive"))
      (node (ref "S702") (pin "1") (pinfunction "1_1") (pintype "passive"))
      (node (ref "S702") (pin "2") (pinfunction "1_2") (pintype "passive"))
      (node (ref "S901") (pin "1") (pinfunction "1_1") (pintype "passive"))
      (node (ref "S901") (pin "2") (pinfunction "1_2") (pintype "passive"))
      (node (ref "U1001") (pin "4") (pinfunction "GND_4") (pintype "bidirectional"))
      (node (ref "U1002") (pin "2") (pinfunction "GND_2") (pintype "input"))
      (node (ref "U101") (pin "3") (pinfunction "P$V-_3") (pintype "bidirectional"))
      (node (ref "U102") (pin "2") (pinfunction "GND_2") (pintype "input"))
      (node (ref "U1101") (pin "6") (pinfunction "VSS_6") (pintype "bidirectional"))
      (node (ref "U1101") (pin "PAD") (pinfunction "VSS_PAD") (pintype "bidirectional"))
      (node (ref "U1102") (pin "4") (pinfunction "GND_4") (pintype "bidirectional"))
      (node (ref "U1201") (pin "6") (pinfunction "VSS_6") (pintype "bidirectional"))
      (node (ref "U1201") (pin "PAD") (pinfunction "VSS_PAD") (pintype "bidirectional"))
      (node (ref "U1202") (pin "4") (pinfunction "GND_4") (pintype "bidirectional"))
      (node (ref "U1301") (pin "6") (pinfunction "VSS_6") (pintype "bidirectional"))
      (node (ref "U1301") (pin "PAD") (pinfunction "VSS_PAD") (pintype "bidirectional"))
      (node (ref "U1302") (pin "4") (pinfunction "GND_4") (pintype "bidirectional"))
      (node (ref "U1401") (pin "3") (pinfunction "P$V-_3") (pintype "bidirectional"))
      (node (ref "U1402") (pin "2") (pinfunction "GND_2") (pintype "input"))
      (node (ref "U201") (pin "3") (pinfunction "P$V-_3") (pintype "bidirectional"))
      (node (ref "U202") (pin "4") (pinfunction "GND_4") (pintype "bidirectional"))
      (node (ref "U203") (pin "2") (pinfunction "GND_2") (pintype "input"))
      (node (ref "U301") (pin "3") (pinfunction "P$V-_3") (pintype "bidirectional"))
      (node (ref "U302") (pin "3") (pinfunction "GND_3") (pintype "power_in"))
      (node (ref "U303") (pin "4") (pinfunction "GND_4") (pintype "bidirectional"))
      (node (ref "U304") (pin "2") (pinfunction "GND_2") (pintype "input"))
      (node (ref "U401") (pin "3") (pinfunction "P$V-_3") (pintype "bidirectional"))
      (node (ref "U402") (pin "3") (pinfunction "GND_3") (pintype "power_in"))
      (node (ref "U403") (pin "4") (pinfunction "GND_4") (pintype "bidirectional"))
      (node (ref "U404") (pin "2") (pinfunction "GND_2") (pintype "input"))
      (node (ref "U501") (pin "3") (pinfunction "P$V-_3") (pintype "bidirectional"))
      (node (ref "U502") (pin "3") (pinfunction "GND_3") (pintype "power_in"))
      (node (ref "U503") (pin "4") (pinfunction "GND_4") (pintype "bidirectional"))
      (node (ref "U504") (pin "2") (pinfunction "GND_2") (pintype "input"))
      (node (ref "U601") (pin "3") (pinfunction "P$V-_3") (pintype "bidirectional"))
      (node (ref "U602") (pin "3") (pinfunction "GND_3") (pintype "power_in"))
      (node (ref "U603") (pin "4") (pinfunction "GND_4") (pintype "bidirectional"))
      (node (ref "U604") (pin "2") (pinfunction "GND_2") (pintype "input"))
      (node (ref "U701") (pin "4") (pinfunction "GND_4") (pintype "bidirectional"))
      (node (ref "U702") (pin "4") (pinfunction "GND_4") (pintype "bidirectional"))
      (node (ref "U703") (pin "2") (pinfunction "GND_2") (pintype "input"))
      (node (ref "U801") (pin "3") (pinfunction "P$V-_3") (pintype "bidirectional"))
      (node (ref "U802") (pin "3") (pinfunction "GND_3") (pintype "power_in"))
      (node (ref "U803") (pin "2") (pinfunction "GND_2") (pintype "input"))
      (node (ref "U901") (pin "4") (pinfunction "GND_4") (pintype "bidirectional"))
      (node (ref "U902") (pin "2") (pinfunction "GND_2") (pintype "input"))
      (node (ref "X1601") (pin "2") (pinfunction "1_2") (pintype "passive"))
    )
    (net (code "45") (name "IMA0.5_IN") (class "Default")
      (node (ref "D1403") (pin "A") (pinfunction "A_A") (pintype "passive"))
      (node (ref "J1613") (pin "1") (pinfunction "1_1") (pintype "passive"))
      (node (ref "JP1401") (pin "1") (pinfunction "1_1") (pintype "passive"))
      (node (ref "U1401") (pin "2") (pinfunction "A_2") (pintype "bidirectional"))
    )
    (net (code "46") (name "IMA0.5_OUT") (class "Default")
      (node (ref "D1402") (pin "A") (pinfunction "A_A") (pintype "passive"))
      (node (ref "J1401") (pin "2") (pinfunction "2_2") (pintype "passive"))
      (node (ref "J1614") (pin "2") (pinfunction "2_2") (pintype "passive"))
      (node (ref "R1401") (pin "1") (pinfunction "1_1") (pintype "passive"))
      (node (ref "S1401") (pin "2") (pinfunction "P_2") (pintype "passive"))
    )
    (net (code "47") (name "IMA0.5_VCC") (class "Default")
      (node (ref "C1401") (pin "+") (pinfunction "+_+") (pintype "passive"))
      (node (ref "D1404") (pin "A") (pinfunction "A_A") (pintype "passive"))
      (node (ref "J1401") (pin "1") (pinfunction "1_1") (pintype "passive"))
      (node (ref "S1401") (pin "1") (pinfunction "O_1") (pintype "passive"))
      (node (ref "TP1402") (pin "TP") (pinfunction "TP_TP") (pintype "input"))
      (node (ref "U1401") (pin "5") (pinfunction "P$V+_5") (pintype "bidirectional"))
      (node (ref "U1402") (pin "5") (pinfunction "OUT_5") (pintype "passive"))
    )
    (net (code "48") (name "IMA7_IN") (class "Default")
      (node (ref "D1302") (pin "A") (pinfunction "A_A") (pintype "passive"))
      (node (ref "J1612") (pin "1") (pinfunction "1_1") (pintype "passive"))
      (node (ref "U1302") (pin "2") (pinfunction "PB3(ADC3)_2") (pintype "bidirectional"))
    )
    (net (code "49") (name "IMA7_MISO") (class "Default")
      (node (ref "J1304") (pin "1") (pinfunction "1_1") (pintype "passive"))
      (node (ref "U1301") (pin "9") (pinfunction "AIN2/EN_9") (pintype "bidirectional"))
      (node (ref "U1302") (pin "6") (pinfunction "PB1(MISO)_6") (pintype "bidirectional"))
    )
    (net (code "50") (name "IMA7_MOSI") (class "Default")
      (node (ref "J1304") (pin "4") (pinfunction "4_4") (pintype "passive"))
      (node (ref "U1301") (pin "10") (pinfunction "AIN1/PH_10") (pintype "bidirectional"))
      (node (ref "U1302") (pin "5") (pinfunction "PB0(MOSI)_5") (pintype "bidirectional"))
    )
    (net (code "51") (name "IMA7_OUT") (class "Default")
      (node (ref "D1301") (pin "A") (pinfunction "A_A") (pintype "passive"))
      (node (ref "J1301") (pin "2") (pinfunction "2_2") (pintype "passive"))
      (node (ref "J1613") (pin "2") (pinfunction "2_2") (pintype "passive"))
      (node (ref "R1301") (pin "1") (pinfunction "1_1") (pintype "passive"))
      (node (ref "S1302") (pin "2") (pinfunction "P_2") (pintype "passive"))
    )
    (net (code "52") (name "IMA7_RST") (class "Default")
      (node (ref "J1304") (pin "5") (pinfunction "5_5") (pintype "passive"))
      (node (ref "R1303") (pin "1") (pinfunction "1_1") (pintype "passive"))
      (node (ref "S1301") (pin "3") (pinfunction "2_3") (pintype "passive"))
      (node (ref "S1301") (pin "4") (pinfunction "2_4") (pintype "passive"))
      (node (ref "U1302") (pin "1") (pinfunction "PB5(NRES)_1") (pintype "bidirectional"))
    )
    (net (code "53") (name "IMA7_SCK") (class "Default")
      (node (ref "J1302") (pin "2") (pinfunction "2_2") (pintype "passive"))
      (node (ref "J1304") (pin "3") (pinfunction "3_3") (pintype "passive"))
      (node (ref "R1302") (pin "1") (pinfunction "1_1") (pintype "passive"))
      (node (ref "U1302") (pin "7") (pinfunction "PB2(SCK/ADC1)_7") (pintype "bidirectional"))
    )
    (net (code "54") (name "IMA7_VCC") (class "Default")
      (node (ref "C1301") (pin "2") (pinfunction "2_2") (pintype "passive"))
      (node (ref "C1303") (pin "1") (pinfunction "1_1") (pintype "passive"))
      (node (ref "D1303") (pin "A") (pinfunction "A_A") (pintype "passive"))
      (node (ref "IC1301") (pin "2") (pinfunction "VO_2") (pintype "passive"))
      (node (ref "J1301") (pin "1") (pinfunction "1_1") (pintype "passive"))
      (node (ref "J1302") (pin "1") (pinfunction "1_1") (pintype "passive"))
      (node (ref "J1304") (pin "2") (pinfunction "2_2") (pintype "passive"))
      (node (ref "R1303") (pin "2") (pinfunction "2_2") (pintype "passive"))
      (node (ref "S1302") (pin "1") (pinfunction "O_1") (pintype "passive"))
      (node (ref "TP1301") (pin "TP") (pinfunction "TP_TP") (pintype "input"))
      (node (ref "U1301") (pin "1") (pinfunction "VM_1") (pintype "bidirectional"))
      (node (ref "U1301") (pin "11") (pinfunction "MODE_11") (pintype "bidirectional"))
      (node (ref "U1301") (pin "12") (pinfunction "VCC_12") (pintype "bidirectional"))
      (node (ref "U1302") (pin "8") (pinfunction "VCC_8") (pintype "bidirectional"))
    )
    (net (code "55") (name "IR_1_MISO") (class "Default")
      (node (ref "J702") (pin "1") (pinfunction "1_1") (pintype "passive"))
      (node (ref "J704") (pin "1") (pinfunction "1_1") (pintype "passive"))
      (node (ref "U702") (pin "6") (pinfunction "PB1(MISO)_6") (pintype "bidirectional"))
    )
    (net (code "56") (name "IR_1_MOSI") (class "Default")
      (node (ref "J704") (pin "4") (pinfunction "4_4") (pintype "passive"))
      (node (ref "U702") (pin "5") (pinfunction "PB0(MOSI)_5") (pintype "bidirectional"))
    )
    (net (code "57") (name "IR_1_RST") (class "Default")
      (node (ref "J704") (pin "5") (pinfunction "5_5") (pintype "passive"))
      (node (ref "R704") (pin "1") (pinfunction "1_1") (pintype "passive"))
      (node (ref "S702") (pin "3") (pinfunction "2_3") (pintype "passive"))
      (node (ref "S702") (pin "4") (pinfunction "2_4") (pintype "passive"))
      (node (ref "U702") (pin "1") (pinfunction "PB5(NRES)_1") (pintype "bidirectional"))
    )
    (net (code "58") (name "IR_1_SCK") (class "Default")
      (node (ref "J704") (pin "3") (pinfunction "3_3") (pintype "passive"))
      (node (ref "U702") (pin "7") (pinfunction "PB2(SCK/ADC1)_7") (pintype "bidirectional"))
    )
    (net (code "59") (name "IR_2_MISO") (class "Default")
      (node (ref "J703") (pin "1") (pinfunction "1_1") (pintype "passive"))
      (node (ref "U701") (pin "6") (pinfunction "PB1(MISO)_6") (pintype "bidirectional"))
    )
    (net (code "60") (name "IR_2_MOSI") (class "Default")
      (node (ref "J703") (pin "4") (pinfunction "4_4") (pintype "passive"))
      (node (ref "U701") (pin "5") (pinfunction "PB0(MOSI)_5") (pintype "bidirectional"))
    )
    (net (code "61") (name "IR_2_RST") (class "Default")
      (node (ref "J703") (pin "5") (pinfunction "5_5") (pintype "passive"))
      (node (ref "R703") (pin "1") (pinfunction "1_1") (pintype "passive"))
      (node (ref "S701") (pin "3") (pinfunction "2_3") (pintype "passive"))
      (node (ref "S701") (pin "4") (pinfunction "2_4") (pintype "passive"))
      (node (ref "U701") (pin "1") (pinfunction "PB5(NRES)_1") (pintype "bidirectional"))
    )
    (net (code "62") (name "IR_2_SCK") (class "Default")
      (node (ref "J703") (pin "3") (pinfunction "3_3") (pintype "passive"))
      (node (ref "R702") (pin "1") (pinfunction "1_1") (pintype "passive"))
      (node (ref "U701") (pin "7") (pinfunction "PB2(SCK/ADC1)_7") (pintype "bidirectional"))
    )
    (net (code "63") (name "IR_IN") (class "Default")
      (node (ref "D702") (pin "A") (pinfunction "A_A") (pintype "passive"))
      (node (ref "J1606") (pin "1") (pinfunction "1_1") (pintype "passive"))
      (node (ref "U702") (pin "2") (pinfunction "PB3(ADC3)_2") (pintype "bidirectional"))
    )
    (net (code "64") (name "IR_OUT") (class "Default")
      (node (ref "D701") (pin "A") (pinfunction "A_A") (pintype "passive"))
      (node (ref "J1607") (pin "2") (pinfunction "2_2") (pintype "passive"))
      (node (ref "S703") (pin "2") (pinfunction "P_2") (pintype "passive"))
    )
    (net (code "65") (name "IR_OUT_SWITCH") (class "Default")
      (node (ref "S703") (pin "3") (pinfunction "S_3") (pintype "passive"))
      (node (ref "U701") (pin "3") (pinfunction "PB4(ADC2)_3") (pintype "bidirectional"))
    )
    (net (code "66") (name "IR_VCC") (class "Default")
      (node (ref "C701") (pin "2") (pinfunction "2_2") (pintype "passive"))
      (node (ref "C702") (pin "2") (pinfunction "2_2") (pintype "passive"))
      (node (ref "C703") (pin "+") (pinfunction "+_+") (pintype "passive"))
      (node (ref "D703") (pin "A") (pinfunction "A_A") (pintype "passive"))
      (node (ref "J701") (pin "3") (pinfunction "3_3") (pintype "passive"))
      (node (ref "J703") (pin "2") (pinfunction "2_2") (pintype "passive"))
      (node (ref "J704") (pin "2") (pinfunction "2_2") (pintype "passive"))
      (node (ref "R701") (pin "1") (pinfunction "1_1") (pintype "passive"))
      (node (ref "R703") (pin "2") (pinfunction "2_2") (pintype "passive"))
      (node (ref "R704") (pin "2") (pinfunction "2_2") (pintype "passive"))
      (node (ref "S703") (pin "1") (pinfunction "O_1") (pintype "passive"))
      (node (ref "TP701") (pin "TP") (pinfunction "TP_TP") (pintype "input"))
      (node (ref "U701") (pin "8") (pinfunction "VCC_8") (pintype "bidirectional"))
      (node (ref "U702") (pin "8") (pinfunction "VCC_8") (pintype "bidirectional"))
      (node (ref "U703") (pin "5") (pinfunction "OUT_5") (pintype "passive"))
    )
    (net (code "67") (name "LEVER_IN") (class "Default")
      (node (ref "D903") (pin "A") (pinfunction "A_A") (pintype "passive"))
      (node (ref "J1608") (pin "1") (pinfunction "1_1") (pintype "passive"))
      (node (ref "U901") (pin "2") (pinfunction "PB3(ADC3)_2") (pintype "bidirectional"))
    )
    (net (code "68") (name "LEVER_MISO") (class "Default")
      (node (ref "J903") (pin "1") (pinfunction "1_1") (pintype "passive"))
      (node (ref "U901") (pin "6") (pinfunction "PB1(MISO)_6") (pintype "bidirectional"))
    )
    (net (code "69") (name "LEVER_MOSI") (class "Default")
      (node (ref "J903") (pin "4") (pinfunction "4_4") (pintype "passive"))
      (node (ref "U901") (pin "5") (pinfunction "PB0(MOSI)_5") (pintype "bidirectional"))
    )
    (net (code "70") (name "LEVER_OUT") (class "Default")
      (node (ref "D902") (pin "A") (pinfunction "A_A") (pintype "passive"))
      (node (ref "J1609") (pin "2") (pinfunction "2_2") (pintype "passive"))
      (node (ref "J901") (pin "2") (pinfunction "2_2") (pintype "passive"))
      (node (ref "R903") (pin "1") (pinfunction "1_1") (pintype "passive"))
      (node (ref "S902") (pin "2") (pinfunction "P_2") (pintype "passive"))
    )
    (net (code "71") (name "LEVER_RST") (class "Default")
      (node (ref "J903") (pin "5") (pinfunction "5_5") (pintype "passive"))
      (node (ref "R904") (pin "1") (pinfunction "1_1") (pintype "passive"))
      (node (ref "S901") (pin "3") (pinfunction "2_3") (pintype "passive"))
      (node (ref "S901") (pin "4") (pinfunction "2_4") (pintype "passive"))
      (node (ref "U901") (pin "1") (pinfunction "PB5(NRES)_1") (pintype "bidirectional"))
    )
    (net (code "72") (name "LEVER_SCK") (class "Default")
      (node (ref "J903") (pin "3") (pinfunction "3_3") (pintype "passive"))
      (node (ref "R901") (pin "1") (pinfunction "1_1") (pintype "passive"))
      (node (ref "R902") (pin "1") (pinfunction "1_1") (pintype "passive"))
      (node (ref "U901") (pin "7") (pinfunction "PB2(SCK/ADC1)_7") (pintype "bidirectional"))
    )
    (net (code "73") (name "LEVER_VCC") (class "Default")
      (node (ref "C901") (pin "2") (pinfunction "2_2") (pintype "passive"))
      (node (ref "C902") (pin "+") (pinfunction "+_+") (pintype "passive"))
      (node (ref "D904") (pin "A") (pinfunction "A_A") (pintype "passive"))
      (node (ref "J901") (pin "1") (pinfunction "1_1") (pintype "passive"))
      (node (ref "J903") (pin "2") (pinfunction "2_2") (pintype "passive"))
      (node (ref "R904") (pin "2") (pinfunction "2_2") (pintype "passive"))
      (node (ref "S902") (pin "1") (pinfunction "O_1") (pintype "passive"))
      (node (ref "TP901") (pin "TP") (pinfunction "TP_TP") (pintype "input"))
      (node (ref "U901") (pin "8") (pinfunction "VCC_8") (pintype "bidirectional"))
      (node (ref "U902") (pin "5") (pinfunction "OUT_5") (pintype "passive"))
    )
    (net (code "74") (name "LIGHT_IN") (class "Default")
      (node (ref "D403") (pin "A") (pinfunction "A_A") (pintype "passive"))
      (node (ref "J1603") (pin "1") (pinfunction "1_1") (pintype "passive"))
      (node (ref "U402") (pin "1") (pinfunction "A_1") (pintype "input"))
    )
    (net (code "75") (name "LIGHT_MISO") (class "Default")
      (node (ref "J401") (pin "1") (pinfunction "1_1") (pintype "passive"))
      (node (ref "U403") (pin "6") (pinfunction "PB1(MISO)_6") (pintype "bidirectional"))
    )
    (net (code "76") (name "LIGHT_MOSI") (class "Default")
      (node (ref "J401") (pin "4") (pinfunction "4_4") (pintype "passive"))
      (node (ref "U403") (pin "5") (pinfunction "PB0(MOSI)_5") (pintype "bidirectional"))
    )
    (net (code "77") (name "LIGHT_OUT") (class "Default")
      (node (ref "D402") (pin "A") (pinfunction "A_A") (pintype "passive"))
      (node (ref "J1604") (pin "2") (pinfunction "2_2") (pintype "passive"))
      (node (ref "S402") (pin "2") (pinfunction "P_2") (pintype "passive"))
      (node (ref "U401") (pin "2") (pinfunction "A_2") (pintype "bidirectional"))
    )
    (net (code "78") (name "LIGHT_OUT_SWITCH") (class "Default")
      (node (ref "S402") (pin "3") (pinfunction "S_3") (pintype "passive"))
      (node (ref "U403") (pin "3") (pinfunction "PB4(ADC2)_3") (pintype "bidirectional"))
    )
    (net (code "79") (name "LIGHT_RST") (class "Default")
      (node (ref "J401") (pin "5") (pinfunction "5_5") (pintype "passive"))
      (node (ref "R405") (pin "1") (pinfunction "1_1") (pintype "passive"))
      (node (ref "S401") (pin "3") (pinfunction "2_3") (pintype "passive"))
      (node (ref "S401") (pin "4") (pinfunction "2_4") (pintype "passive"))
      (node (ref "U403") (pin "1") (pinfunction "PB5(NRES)_1") (pintype "bidirectional"))
    )
    (net (code "80") (name "LIGHT_SCK") (class "Default")
      (node (ref "J401") (pin "3") (pinfunction "3_3") (pintype "passive"))
      (node (ref "R401") (pin "2") (pinfunction "2_2") (pintype "passive"))
      (node (ref "R402") (pin "1") (pinfunction "P$1_1") (pintype "bidirectional"))
      (node (ref "U403") (pin "7") (pinfunction "PB2(SCK/ADC1)_7") (pintype "bidirectional"))
    )
    (net (code "81") (name "LIGHT_VCC") (class "Default")
      (node (ref "C401") (pin "2") (pinfunction "2_2") (pintype "passive"))
      (node (ref "C402") (pin "+") (pinfunction "+_+") (pintype "passive"))
      (node (ref "D404") (pin "A") (pinfunction "A_A") (pintype "passive"))
      (node (ref "J401") (pin "2") (pinfunction "2_2") (pintype "passive"))
      (node (ref "Q401") (pin "3") (pinfunction "C_3") (pintype "passive"))
      (node (ref "R402") (pin "2") (pinfunction "P$2_2") (pintype "bidirectional"))
      (node (ref "R405") (pin "2") (pinfunction "2_2") (pintype "passive"))
      (node (ref "S402") (pin "1") (pinfunction "O_1") (pintype "passive"))
      (node (ref "TP403") (pin "TP") (pinfunction "TP_TP") (pintype "input"))
      (node (ref "U401") (pin "5") (pinfunction "P$V+_5") (pintype "bidirectional"))
      (node (ref "U402") (pin "5") (pinfunction "VCC_5") (pintype "power_in"))
      (node (ref "U403") (pin "8") (pinfunction "VCC_8") (pintype "bidirectional"))
      (node (ref "U404") (pin "5") (pinfunction "OUT_5") (pintype "passive"))
    )
    (net (code "82") (name "Net-(D101-PadC)") (class "Default")
      (node (ref "D101") (pin "C") (pinfunction "C_C") (pintype "passive"))
      (node (ref "R102") (pin "2") (pinfunction "2_2") (pintype "passive"))
    )
    (net (code "83") (name "Net-(D102-PadC)") (class "Default")
      (node (ref "D102") (pin "C") (pinfunction "C_C") (pintype "passive"))
      (node (ref "R103") (pin "2") (pinfunction "2_2") (pintype "passive"))
    )
    (net (code "84") (name "Net-(D202-PadC)") (class "Default")
      (node (ref "D202") (pin "C") (pinfunction "C_C") (pintype "passive"))
      (node (ref "R205") (pin "2") (pinfunction "2_2") (pintype "passive"))
    )
    (net (code "85") (name "Net-(D203-PadC)") (class "Default")
      (node (ref "D203") (pin "C") (pinfunction "C_C") (pintype "passive"))
      (node (ref "R206") (pin "2") (pinfunction "2_2") (pintype "passive"))
    )
    (net (code "86") (name "Net-(D204-PadC)") (class "Default")
      (node (ref "D204") (pin "C") (pinfunction "C_C") (pintype "passive"))
      (node (ref "R207") (pin "2") (pinfunction "2_2") (pintype "passive"))
    )
    (net (code "87") (name "Net-(D302-PadC)") (class "Default")
      (node (ref "D302") (pin "C") (pinfunction "C_C") (pintype "passive"))
      (node (ref "R305") (pin "2") (pinfunction "2_2") (pintype "passive"))
    )
    (net (code "88") (name "Net-(D303-PadC)") (class "Default")
      (node (ref "D303") (pin "C") (pinfunction "C_C") (pintype "passive"))
      (node (ref "R306") (pin "2") (pinfunction "2_2") (pintype "passive"))
    )
    (net (code "89") (name "Net-(D304-PadC)") (class "Default")
      (node (ref "D304") (pin "C") (pinfunction "C_C") (pintype "passive"))
      (node (ref "R307") (pin "2") (pinfunction "2_2") (pintype "passive"))
    )
    (net (code "90") (name "Net-(D401-C)") (class "Default")
      (node (ref "D401") (pin "K") (pinfunction "C_K") (pintype "passive"))
      (node (ref "R404") (pin "1") (pinfunction "1_1") (pintype "passive"))
    )
    (net (code "91") (name "Net-(D402-PadC)") (class "Default")
      (node (ref "D402") (pin "C") (pinfunction "C_C") (pintype "passive"))
      (node (ref "R406") (pin "2") (pinfunction "2_2") (pintype "passive"))
    )
    (net (code "92") (name "Net-(D403-PadC)") (class "Default")
      (node (ref "D403") (pin "C") (pinfunction "C_C") (pintype "passive"))
      (node (ref "R407") (pin "2") (pinfunction "2_2") (pintype "passive"))
    )
    (net (code "93") (name "Net-(D404-PadC)") (class "Default")
      (node (ref "D404") (pin "C") (pinfunction "C_C") (pintype "passive"))
      (node (ref "R408") (pin "2") (pinfunction "2_2") (pintype "passive"))
    )
    (net (code "94") (name "Net-(D502-PadC)") (class "Default")
      (node (ref "D502") (pin "C") (pinfunction "C_C") (pintype "passive"))
      (node (ref "R505") (pin "2") (pinfunction "2_2") (pintype "passive"))
    )
    (net (code "95") (name "Net-(D503-PadC)") (class "Default")
      (node (ref "D503") (pin "C") (pinfunction "C_C") (pintype "passive"))
      (node (ref "R506") (pin "2") (pinfunction "2_2") (pintype "passive"))
    )
    (net (code "96") (name "Net-(D504-PadC)") (class "Default")
      (node (ref "D504") (pin "C") (pinfunction "C_C") (pintype "passive"))
      (node (ref "R507") (pin "2") (pinfunction "2_2") (pintype "passive"))
    )
    (net (code "97") (name "Net-(D602-PadC)") (class "Default")
      (node (ref "D602") (pin "C") (pinfunction "C_C") (pintype "passive"))
      (node (ref "R605") (pin "2") (pinfunction "2_2") (pintype "passive"))
    )
    (net (code "98") (name "Net-(D603-PadC)") (class "Default")
      (node (ref "D603") (pin "C") (pinfunction "C_C") (pintype "passive"))
      (node (ref "R606") (pin "2") (pinfunction "2_2") (pintype "passive"))
    )
    (net (code "99") (name "Net-(D604-PadC)") (class "Default")
      (node (ref "D604") (pin "C") (pinfunction "C_C") (pintype "passive"))
      (node (ref "R607") (pin "2") (pinfunction "2_2") (pintype "passive"))
    )
    (net (code "100") (name "Net-(D701-PadC)") (class "Default")
      (node (ref "D701") (pin "C") (pinfunction "C_C") (pintype "passive"))
      (node (ref "R705") (pin "2") (pinfunction "2_2") (pintype "passive"))
    )
    (net (code "101") (name "Net-(D702-PadC)") (class "Default")
      (node (ref "D702") (pin "C") (pinfunction "C_C") (pintype "passive"))
      (node (ref "R706") (pin "2") (pinfunction "2_2") (pintype "passive"))
    )
    (net (code "102") (name "Net-(D703-PadC)") (class "Default")
      (node (ref "D703") (pin "C") (pinfunction "C_C") (pintype "passive"))
      (node (ref "R707") (pin "2") (pinfunction "2_2") (pintype "passive"))
    )
    (net (code "103") (name "Net-(D802-PadC)") (class "Default")
      (node (ref "D802") (pin "C") (pinfunction "C_C") (pintype "passive"))
      (node (ref "R804") (pin "2") (pinfunction "2_2") (pintype "passive"))
    )
    (net (code "104") (name "Net-(D803-PadC)") (class "Default")
      (node (ref "D803") (pin "C") (pinfunction "C_C") (pintype "passive"))
      (node (ref "R805") (pin "2") (pinfunction "2_2") (pintype "passive"))
    )
    (net (code "105") (name "Net-(D804-PadC)") (class "Default")
      (node (ref "D804") (pin "C") (pinfunction "C_C") (pintype "passive"))
      (node (ref "R806") (pin "2") (pinfunction "2_2") (pintype "passive"))
    )
    (net (code "106") (name "Net-(D902-PadC)") (class "Default")
      (node (ref "D902") (pin "C") (pinfunction "C_C") (pintype "passive"))
      (node (ref "R905") (pin "2") (pinfunction "2_2") (pintype "passive"))
    )
    (net (code "107") (name "Net-(D903-PadC)") (class "Default")
      (node (ref "D903") (pin "C") (pinfunction "C_C") (pintype "passive"))
      (node (ref "R906") (pin "2") (pinfunction "2_2") (pintype "passive"))
    )
    (net (code "108") (name "Net-(D904-PadC)") (class "Default")
      (node (ref "D904") (pin "C") (pinfunction "C_C") (pintype "passive"))
      (node (ref "R907") (pin "2") (pinfunction "2_2") (pintype "passive"))
    )
    (net (code "109") (name "Net-(D1002-PadC)") (class "Default")
      (node (ref "D1002") (pin "C") (pinfunction "C_C") (pintype "passive"))
      (node (ref "R1006") (pin "2") (pinfunction "2_2") (pintype "passive"))
    )
    (net (code "110") (name "Net-(D1003-PadC)") (class "Default")
      (node (ref "D1003") (pin "C") (pinfunction "C_C") (pintype "passive"))
      (node (ref "R1007") (pin "2") (pinfunction "2_2") (pintype "passive"))
    )
    (net (code "111") (name "Net-(D1004-PadC)") (class "Default")
      (node (ref "D1004") (pin "C") (pinfunction "C_C") (pintype "passive"))
      (node (ref "R1008") (pin "2") (pinfunction "2_2") (pintype "passive"))
    )
    (net (code "112") (name "Net-(D1101-PadC)") (class "Default")
      (node (ref "D1101") (pin "C") (pinfunction "C_C") (pintype "passive"))
      (node (ref "R1104") (pin "2") (pinfunction "2_2") (pintype "passive"))
    )
    (net (code "113") (name "Net-(D1102-PadC)") (class "Default")
      (node (ref "D1102") (pin "C") (pinfunction "C_C") (pintype "passive"))
      (node (ref "R1105") (pin "2") (pinfunction "2_2") (pintype "passive"))
    )
    (net (code "114") (name "Net-(D1103-PadC)") (class "Default")
      (node (ref "D1103") (pin "C") (pinfunction "C_C") (pintype "passive"))
      (node (ref "R1106") (pin "2") (pinfunction "2_2") (pintype "passive"))
    )
    (net (code "115") (name "Net-(D1201-PadC)") (class "Default")
      (node (ref "D1201") (pin "C") (pinfunction "C_C") (pintype "passive"))
      (node (ref "R1204") (pin "2") (pinfunction "2_2") (pintype "passive"))
    )
    (net (code "116") (name "Net-(D1202-PadC)") (class "Default")
      (node (ref "D1202") (pin "C") (pinfunction "C_C") (pintype "passive"))
      (node (ref "R1205") (pin "2") (pinfunction "2_2") (pintype "passive"))
    )
    (net (code "117") (name "Net-(D1203-PadC)") (class "Default")
      (node (ref "D1203") (pin "C") (pinfunction "C_C") (pintype "passive"))
      (node (ref "R1206") (pin "2") (pinfunction "2_2") (pintype "passive"))
    )
    (net (code "118") (name "Net-(D1301-PadC)") (class "Default")
      (node (ref "D1301") (pin "C") (pinfunction "C_C") (pintype "passive"))
      (node (ref "R1304") (pin "2") (pinfunction "2_2") (pintype "passive"))
    )
    (net (code "119") (name "Net-(D1302-PadC)") (class "Default")
      (node (ref "D1302") (pin "C") (pinfunction "C_C") (pintype "passive"))
      (node (ref "R1305") (pin "2") (pinfunction "2_2") (pintype "passive"))
    )
    (net (code "120") (name "Net-(D1303-PadC)") (class "Default")
      (node (ref "D1303") (pin "C") (pinfunction "C_C") (pintype "passive"))
      (node (ref "R1306") (pin "2") (pinfunction "2_2") (pintype "passive"))
    )
    (net (code "121") (name "Net-(D1402-PadC)") (class "Default")
      (node (ref "D1402") (pin "C") (pinfunction "C_C") (pintype "passive"))
      (node (ref "R1404") (pin "2") (pinfunction "2_2") (pintype "passive"))
    )
    (net (code "122") (name "Net-(D1403-PadC)") (class "Default")
      (node (ref "D1403") (pin "C") (pinfunction "C_C") (pintype "passive"))
      (node (ref "R1405") (pin "2") (pinfunction "2_2") (pintype "passive"))
    )
    (net (code "123") (name "Net-(D1404-PadC)") (class "Default")
      (node (ref "D1404") (pin "C") (pinfunction "C_C") (pintype "passive"))
      (node (ref "R1406") (pin "2") (pinfunction "2_2") (pintype "passive"))
    )
    (net (code "124") (name "Net-(D1501-PadC)") (class "Default")
      (node (ref "D1501") (pin "C") (pinfunction "C_C") (pintype "passive"))
      (node (ref "R1502") (pin "2") (pinfunction "2_2") (pintype "passive"))
    )
    (net (code "125") (name "Net-(D1502-PadC)") (class "Default")
      (node (ref "D1502") (pin "C") (pinfunction "C_C") (pintype "passive"))
      (node (ref "R1503") (pin "2") (pinfunction "2_2") (pintype "passive"))
    )
    (net (code "126") (name "Net-(J501-Pad1)") (class "Default")
      (node (ref "J501") (pin "1") (pinfunction "1_1") (pintype "passive"))
      (node (ref "R501") (pin "1") (pinfunction "1_1") (pintype "passive"))
    )
    (net (code "127") (name "Net-(J701-Pad1)") (class "Default")
      (node (ref "J701") (pin "1") (pinfunction "1_1") (pintype "passive"))
      (node (ref "R702") (pin "2") (pinfunction "2_2") (pintype "passive"))
    )
    (net (code "128") (name "Net-(J702-Pad2)") (class "Default")
      (node (ref "J702") (pin "2") (pinfunction "2_2") (pintype "passive"))
      (node (ref "R701") (pin "2") (pinfunction "2_2") (pintype "passive"))
    )
    (net (code "129") (name "Net-(J1002-Pad1)") (class "Default")
      (node (ref "J1002") (pin "1") (pinfunction "1_1") (pintype "passive"))
      (node (ref "R1003") (pin "1") (pinfunction "1_1") (pintype "passive"))
    )
    (net (code "130") (name "Net-(JP201-Pad2)") (class "Default")
      (node (ref "JP201") (pin "2") (pinfunction "2_2") (pintype "passive"))
      (node (ref "JP202") (pin "2") (pinfunction "2_2") (pintype "passive"))
      (node (ref "R201") (pin "1") (pinfunction "1_1") (pintype "passive"))
      (node (ref "R202") (pin "1") (pinfunction "1_1") (pintype "passive"))
      (node (ref "TP201") (pin "TP") (pinfunction "TP_TP") (pintype "input"))
    )
    (net (code "131") (name "Net-(JP1401-Pad2)") (class "Default")
      (node (ref "JP1401") (pin "2") (pinfunction "2_2") (pintype "passive"))
      (node (ref "JP1402") (pin "2") (pinfunction "2_2") (pintype "passive"))
      (node (ref "R1402") (pin "1") (pinfunction "1_1") (pintype "passive"))
      (node (ref "R1403") (pin "1") (pinfunction "1_1") (pintype "passive"))
      (node (ref "TP1401") (pin "TP") (pinfunction "TP_TP") (pintype "input"))
    )
    (net (code "132") (name "Net-(Q201-D)") (class "Default")
      (node (ref "D201") (pin "A") (pinfunction "A_A") (pintype "passive"))
      (node (ref "J203") (pin "2") (pinfunction "2_2") (pintype "passive"))
      (node (ref "Q201") (pin "MB") (pinfunction "D_MB") (pintype "passive"))
    )
    (net (code "133") (name "Net-(Q201-G)") (class "Default")
      (node (ref "Q201") (pin "4") (pinfunction "G_4") (pintype "passive"))
      (node (ref "R201") (pin "2") (pinfunction "2_2") (pintype "passive"))
    )
    (net (code "134") (name "Net-(Q301-B)") (class "Default")
      (node (ref "Q301") (pin "1") (pinfunction "B_1") (pintype "passive"))
      (node (ref "R302") (pin "2") (pinfunction "2_2") (pintype "passive"))
    )
    (net (code "135") (name "Net-(Q301-E)") (class "Default")
      (node (ref "D301") (pin "A") (pinfunction "A_A") (pintype "passive"))
      (node (ref "Q301") (pin "2") (pinfunction "E_2") (pintype "passive"))
    )
    (net (code "136") (name "Net-(Q401-B)") (class "Default")
      (node (ref "Q401") (pin "1") (pinfunction "B_1") (pintype "passive"))
      (node (ref "R403") (pin "2") (pinfunction "2_2") (pintype "passive"))
    )
    (net (code "137") (name "Net-(Q401-E)") (class "Default")
      (node (ref "D401") (pin "A") (pinfunction "A_A") (pintype "passive"))
      (node (ref "Q401") (pin "2") (pinfunction "E_2") (pintype "passive"))
    )
    (net (code "138") (name "Net-(Q501-D)") (class "Default")
      (node (ref "D501") (pin "A") (pinfunction "A_A") (pintype "passive"))
      (node (ref "J502") (pin "2") (pinfunction "2_2") (pintype "passive"))
      (node (ref "Q501") (pin "MB") (pinfunction "D_MB") (pintype "passive"))
    )
    (net (code "139") (name "Net-(Q501-G)") (class "Default")
      (node (ref "Q501") (pin "4") (pinfunction "G_4") (pintype "passive"))
      (node (ref "R502") (pin "2") (pinfunction "2_2") (pintype "passive"))
    )
    (net (code "140") (name "Net-(Q601-D)") (class "Default")
      (node (ref "D601") (pin "A") (pinfunction "A_A") (pintype "passive"))
      (node (ref "J602") (pin "2") (pinfunction "2_2") (pintype "passive"))
      (node (ref "Q601") (pin "MB") (pinfunction "D_MB") (pintype "passive"))
    )
    (net (code "141") (name "Net-(Q601-G)") (class "Default")
      (node (ref "Q601") (pin "4") (pinfunction "G_4") (pintype "passive"))
      (node (ref "R601") (pin "2") (pinfunction "2_2") (pintype "passive"))
    )
    (net (code "142") (name "Net-(Q801-D)") (class "Default")
      (node (ref "D801") (pin "A") (pinfunction "A_A") (pintype "passive"))
      (node (ref "J802") (pin "2") (pinfunction "2_2") (pintype "passive"))
      (node (ref "Q801") (pin "MB") (pinfunction "D_MB") (pintype "passive"))
    )
    (net (code "143") (name "Net-(Q801-G)") (class "Default")
      (node (ref "Q801") (pin "4") (pinfunction "G_4") (pintype "passive"))
      (node (ref "R802") (pin "2") (pinfunction "2_2") (pintype "passive"))
    )
    (net (code "144") (name "Net-(Q901-D)") (class "Default")
      (node (ref "D901") (pin "A") (pinfunction "A_A") (pintype "passive"))
      (node (ref "J902") (pin "2") (pinfunction "2_2") (pintype "passive"))
      (node (ref "Q901") (pin "MB") (pinfunction "D_MB") (pintype "passive"))
    )
    (net (code "145") (name "Net-(Q901-G)") (class "Default")
      (node (ref "Q901") (pin "4") (pinfunction "G_4") (pintype "passive"))
      (node (ref "R901") (pin "2") (pinfunction "2_2") (pintype "passive"))
    )
    (net (code "146") (name "Net-(Q1001-D)") (class "Default")
      (node (ref "D1001") (pin "A") (pinfunction "A_A") (pintype "passive"))
      (node (ref "J1001") (pin "2") (pinfunction "2_2") (pintype "passive"))
      (node (ref "Q1001") (pin "MB") (pinfunction "D_MB") (pintype "passive"))
    )
    (net (code "147") (name "Net-(Q1001-G)") (class "Default")
      (node (ref "Q1001") (pin "4") (pinfunction "G_4") (pintype "passive"))
      (node (ref "R1001") (pin "2") (pinfunction "2_2") (pintype "passive"))
    )
    (net (code "148") (name "Net-(Q1401-D)") (class "Default")
      (node (ref "D1401") (pin "A") (pinfunction "A_A") (pintype "passive"))
      (node (ref "J1402") (pin "2") (pinfunction "2_2") (pintype "passive"))
      (node (ref "Q1401") (pin "MB") (pinfunction "D_MB") (pintype "passive"))
    )
    (net (code "149") (name "Net-(Q1401-G)") (class "Default")
      (node (ref "Q1401") (pin "4") (pinfunction "G_4") (pintype "passive"))
      (node (ref "R1402") (pin "2") (pinfunction "2_2") (pintype "passive"))
    )
    (net (code "150") (name "Net-(S101-2)") (class "Default")
      (node (ref "JP101") (pin "1") (pinfunction "1_1") (pintype "passive"))
      (node (ref "R101") (pin "2") (pinfunction "2_2") (pintype "passive"))
      (node (ref "S101") (pin "P$2") (pinfunction "2_P$2") (pintype "passive"))
      (node (ref "U101") (pin "2") (pinfunction "A_2") (pintype "bidirectional"))
    )
    (net (code "151") (name "Net-(U101A-Y)") (class "Default")
      (node (ref "JP102") (pin "1") (pinfunction "1_1") (pintype "passive"))
      (node (ref "U101") (pin "4") (pinfunction "Y_4") (pintype "bidirectional"))
    )
    (net (code "152") (name "Net-(U201A-Y)") (class "Default")
      (node (ref "JP202") (pin "1") (pinfunction "1_1") (pintype "passive"))
      (node (ref "U201") (pin "4") (pinfunction "Y_4") (pintype "bidirectional"))
    )
    (net (code "153") (name "Net-(U202-PB3(ADC3))") (class "Default")
      (node (ref "TP203") (pin "TP") (pinfunction "TP_TP") (pintype "input"))
      (node (ref "U202") (pin "2") (pinfunction "PB3(ADC3)_2") (pintype "bidirectional"))
    )
    (net (code "154") (name "Net-(U301A-Y)") (class "Default")
      (node (ref "TP301") (pin "TP") (pinfunction "TP_TP") (pintype "input"))
      (node (ref "U301") (pin "4") (pinfunction "Y_4") (pintype "bidirectional"))
      (node (ref "U302") (pin "2") (pinfunction "B_2") (pintype "input"))
    )
    (net (code "155") (name "Net-(U302A-Y)") (class "Default")
      (node (ref "R302") (pin "1") (pinfunction "1_1") (pintype "passive"))
      (node (ref "TP302") (pin "TP") (pinfunction "TP_TP") (pintype "input"))
      (node (ref "U302") (pin "4") (pinfunction "Y_4") (pintype "output"))
    )
    (net (code "156") (name "Net-(U303-PB3(ADC3))") (class "Default")
      (node (ref "TP303") (pin "TP") (pinfunction "TP_TP") (pintype "input"))
      (node (ref "U303") (pin "2") (pinfunction "PB3(ADC3)_2") (pintype "bidirectional"))
    )
    (net (code "157") (name "Net-(U401A-Y)") (class "Default")
      (node (ref "TP401") (pin "TP") (pinfunction "TP_TP") (pintype "input"))
      (node (ref "U401") (pin "4") (pinfunction "Y_4") (pintype "bidirectional"))
      (node (ref "U402") (pin "2") (pinfunction "B_2") (pintype "input"))
    )
    (net (code "158") (name "Net-(U402A-Y)") (class "Default")
      (node (ref "R403") (pin "1") (pinfunction "1_1") (pintype "passive"))
      (node (ref "TP402") (pin "TP") (pinfunction "TP_TP") (pintype "input"))
      (node (ref "U402") (pin "4") (pinfunction "Y_4") (pintype "output"))
    )
    (net (code "159") (name "Net-(U403-PB3(ADC3))") (class "Default")
      (node (ref "TP404") (pin "TP") (pinfunction "TP_TP") (pintype "input"))
      (node (ref "U403") (pin "2") (pinfunction "PB3(ADC3)_2") (pintype "bidirectional"))
    )
    (net (code "160") (name "Net-(U501A-Y)") (class "Default")
      (node (ref "TP501") (pin "TP") (pinfunction "TP_TP") (pintype "input"))
      (node (ref "U501") (pin "4") (pinfunction "Y_4") (pintype "bidirectional"))
      (node (ref "U502") (pin "2") (pinfunction "B_2") (pintype "input"))
    )
    (net (code "161") (name "Net-(U502A-Y)") (class "Default")
      (node (ref "R502") (pin "1") (pinfunction "1_1") (pintype "passive"))
      (node (ref "R503") (pin "1") (pinfunction "1_1") (pintype "passive"))
      (node (ref "TP502") (pin "TP") (pinfunction "TP_TP") (pintype "input"))
      (node (ref "U502") (pin "4") (pinfunction "Y_4") (pintype "output"))
    )
    (net (code "162") (name "Net-(U503-PB3(ADC3))") (class "Default")
      (node (ref "TP504") (pin "TP") (pinfunction "TP_TP") (pintype "input"))
      (node (ref "U503") (pin "2") (pinfunction "PB3(ADC3)_2") (pintype "bidirectional"))
    )
    (net (code "163") (name "Net-(U601A-Y)") (class "Default")
      (node (ref "TP602") (pin "TP") (pinfunction "TP_TP") (pintype "input"))
      (node (ref "U601") (pin "4") (pinfunction "Y_4") (pintype "bidirectional"))
      (node (ref "U602") (pin "2") (pinfunction "B_2") (pintype "input"))
    )
    (net (code "164") (name "Net-(U602A-Y)") (class "Default")
      (node (ref "R601") (pin "1") (pinfunction "1_1") (pintype "passive"))
      (node (ref "R602") (pin "1") (pinfunction "1_1") (pintype "passive"))
      (node (ref "TP603") (pin "TP") (pinfunction "TP_TP") (pintype "input"))
      (node (ref "U602") (pin "4") (pinfunction "Y_4") (pintype "output"))
    )
    (net (code "165") (name "Net-(U603-PB3(ADC3))") (class "Default")
      (node (ref "TP604") (pin "TP") (pinfunction "TP_TP") (pintype "input"))
      (node (ref "U603") (pin "2") (pinfunction "PB3(ADC3)_2") (pintype "bidirectional"))
    )
    (net (code "166") (name "Net-(U701-PB3(ADC3))") (class "Default")
      (node (ref "TP702") (pin "TP") (pinfunction "TP_TP") (pintype "input"))
      (node (ref "U701") (pin "2") (pinfunction "PB3(ADC3)_2") (pintype "bidirectional"))
    )
    (net (code "167") (name "Net-(U702-PB4(ADC2))") (class "Default")
      (node (ref "TP703") (pin "TP") (pinfunction "TP_TP") (pintype "input"))
      (node (ref "U702") (pin "3") (pinfunction "PB4(ADC2)_3") (pintype "bidirectional"))
    )
    (net (code "168") (name "Net-(U801A-Y)") (class "Default")
      (node (ref "TP802") (pin "TP") (pinfunction "TP_TP") (pintype "input"))
      (node (ref "U801") (pin "4") (pinfunction "Y_4") (pintype "bidirectional"))
      (node (ref "U802") (pin "2") (pinfunction "B_2") (pintype "input"))
    )
    (net (code "169") (name "Net-(U802A-Y)") (class "Default")
      (node (ref "R802") (pin "1") (pinfunction "1_1") (pintype "passive"))
      (node (ref "R803") (pin "1") (pinfunction "1_1") (pintype "passive"))
      (node (ref "TP803") (pin "TP") (pinfunction "TP_TP") (pintype "input"))
      (node (ref "U802") (pin "4") (pinfunction "Y_4") (pintype "output"))
    )
    (net (code "170") (name "Net-(U901-PB4(ADC2))") (class "Default")
      (node (ref "TP902") (pin "TP") (pinfunction "TP_TP") (pintype "input"))
      (node (ref "U901") (pin "3") (pinfunction "PB4(ADC2)_3") (pintype "bidirectional"))
    )
    (net (code "171") (name "Net-(U1001-PB4(ADC2))") (class "Default")
      (node (ref "TP1002") (pin "TP") (pinfunction "TP_TP") (pintype "input"))
      (node (ref "U1001") (pin "3") (pinfunction "PB4(ADC2)_3") (pintype "bidirectional"))
    )
    (net (code "172") (name "Net-(U1101-AOUT1)") (class "Default")
      (node (ref "J1102") (pin "1") (pinfunction "1_1") (pintype "passive"))
      (node (ref "U1101") (pin "2") (pinfunction "AOUT1_2") (pintype "bidirectional"))
    )
    (net (code "173") (name "Net-(U1101-AOUT2)") (class "Default")
      (node (ref "J1102") (pin "2") (pinfunction "2_2") (pintype "passive"))
      (node (ref "U1101") (pin "3") (pinfunction "AOUT2_3") (pintype "bidirectional"))
    )
    (net (code "174") (name "Net-(U1102-PB4(ADC2))") (class "Default")
      (node (ref "TP1102") (pin "TP") (pinfunction "TP_TP") (pintype "input"))
      (node (ref "U1102") (pin "3") (pinfunction "PB4(ADC2)_3") (pintype "bidirectional"))
    )
    (net (code "175") (name "Net-(U1201-AOUT1)") (class "Default")
      (node (ref "J1203") (pin "1") (pinfunction "1_1") (pintype "passive"))
      (node (ref "U1201") (pin "2") (pinfunction "AOUT1_2") (pintype "bidirectional"))
    )
    (net (code "176") (name "Net-(U1201-AOUT2)") (class "Default")
      (node (ref "J1203") (pin "2") (pinfunction "2_2") (pintype "passive"))
      (node (ref "U1201") (pin "3") (pinfunction "AOUT2_3") (pintype "bidirectional"))
    )
    (net (code "177") (name "Net-(U1202-PB4(ADC2))") (class "Default")
      (node (ref "TP1202") (pin "TP") (pinfunction "TP_TP") (pintype "input"))
      (node (ref "U1202") (pin "3") (pinfunction "PB4(ADC2)_3") (pintype "bidirectional"))
    )
    (net (code "178") (name "Net-(U1301-AOUT1)") (class "Default")
      (node (ref "J1303") (pin "1") (pinfunction "1_1") (pintype "passive"))
      (node (ref "U1301") (pin "2") (pinfunction "AOUT1_2") (pintype "bidirectional"))
    )
    (net (code "179") (name "Net-(U1301-AOUT2)") (class "Default")
      (node (ref "J1303") (pin "2") (pinfunction "2_2") (pintype "passive"))
      (node (ref "U1301") (pin "3") (pinfunction "AOUT2_3") (pintype "bidirectional"))
    )
    (net (code "180") (name "Net-(U1302-PB4(ADC2))") (class "Default")
      (node (ref "TP1302") (pin "TP") (pinfunction "TP_TP") (pintype "input"))
      (node (ref "U1302") (pin "3") (pinfunction "PB4(ADC2)_3") (pintype "bidirectional"))
    )
    (net (code "181") (name "Net-(U1401A-Y)") (class "Default")
      (node (ref "JP1402") (pin "1") (pinfunction "1_1") (pintype "passive"))
      (node (ref "U1401") (pin "4") (pinfunction "Y_4") (pintype "bidirectional"))
    )
    (net (code "182") (name "START_OUT") (class "Default")
      (node (ref "D101") (pin "A") (pinfunction "A_A") (pintype "passive"))
      (node (ref "J1601") (pin "2") (pinfunction "2_2") (pintype "passive"))
      (node (ref "JP101") (pin "2") (pinfunction "2_2") (pintype "passive"))
      (node (ref "JP102") (pin "2") (pinfunction "2_2") (pintype "passive"))
      (node (ref "S102") (pin "2") (pinfunction "P_2") (pintype "passive"))
    )
    (net (code "183") (name "START_VCC") (class "Default")
      (node (ref "C101") (pin "+") (pinfunction "+_+") (pintype "passive"))
      (node (ref "D102") (pin "A") (pinfunction "A_A") (pintype "passive"))
      (node (ref "R101") (pin "1") (pinfunction "1_1") (pintype "passive"))
      (node (ref "S102") (pin "1") (pinfunction "O_1") (pintype "passive"))
      (node (ref "TP101") (pin "TP") (pinfunction "TP_TP") (pintype "input"))
      (node (ref "U101") (pin "5") (pinfunction "P$V+_5") (pintype "bidirectional"))
      (node (ref "U102") (pin "5") (pinfunction "OUT_5") (pintype "passive"))
    )
    (net (code "184") (name "TIMER_IN") (class "Default")
      (node (ref "D1102") (pin "A") (pinfunction "A_A") (pintype "passive"))
      (node (ref "J1610") (pin "1") (pinfunction "1_1") (pintype "passive"))
      (node (ref "U1102") (pin "2") (pinfunction "PB3(ADC3)_2") (pintype "bidirectional"))
    )
    (net (code "185") (name "TIMER_MISO") (class "Default")
      (node (ref "J1104") (pin "1") (pinfunction "1_1") (pintype "passive"))
      (node (ref "U1101") (pin "9") (pinfunction "AIN2/EN_9") (pintype "bidirectional"))
      (node (ref "U1102") (pin "6") (pinfunction "PB1(MISO)_6") (pintype "bidirectional"))
    )
    (net (code "186") (name "TIMER_MOSI") (class "Default")
      (node (ref "J1104") (pin "4") (pinfunction "4_4") (pintype "passive"))
      (node (ref "U1101") (pin "10") (pinfunction "AIN1/PH_10") (pintype "bidirectional"))
      (node (ref "U1102") (pin "5") (pinfunction "PB0(MOSI)_5") (pintype "bidirectional"))
    )
    (net (code "187") (name "TIMER_OUT") (class "Default")
      (node (ref "D1101") (pin "A") (pinfunction "A_A") (pintype "passive"))
      (node (ref "J1101") (pin "2") (pinfunction "2_2") (pintype "passive"))
      (node (ref "J1611") (pin "2") (pinfunction "2_2") (pintype "passive"))
      (node (ref "R1101") (pin "1") (pinfunction "1_1") (pintype "passive"))
      (node (ref "S1102") (pin "2") (pinfunction "P_2") (pintype "passive"))
    )
    (net (code "188") (name "TIMER_RST") (class "Default")
      (node (ref "J1104") (pin "5") (pinfunction "5_5") (pintype "passive"))
      (node (ref "R1103") (pin "1") (pinfunction "1_1") (pintype "passive"))
      (node (ref "S1101") (pin "3") (pinfunction "2_3") (pintype "passive"))
      (node (ref "S1101") (pin "4") (pinfunction "2_4") (pintype "passive"))
      (node (ref "U1102") (pin "1") (pinfunction "PB5(NRES)_1") (pintype "bidirectional"))
    )
    (net (code "189") (name "TIMER_SCK") (class "Default")
      (node (ref "J1103") (pin "2") (pinfunction "2_2") (pintype "passive"))
      (node (ref "J1104") (pin "3") (pinfunction "3_3") (pintype "passive"))
      (node (ref "R1102") (pin "1") (pinfunction "1_1") (pintype "passive"))
      (node (ref "U1102") (pin "7") (pinfunction "PB2(SCK/ADC1)_7") (pintype "bidirectional"))
    )
    (net (code "190") (name "TIMER_VCC") (class "Default")
      (node (ref "C1101") (pin "2") (pinfunction "2_2") (pintype "passive"))
      (node (ref "C1103") (pin "1") (pinfunction "1_1") (pintype "passive"))
      (node (ref "D1103") (pin "A") (pinfunction "A_A") (pintype "passive"))
      (node (ref "IC1101") (pin "2") (pinfunction "VO_2") (pintype "passive"))
      (node (ref "J1101") (pin "1") (pinfunction "1_1") (pintype "passive"))
      (node (ref "J1103") (pin "1") (pinfunction "1_1") (pintype "passive"))
      (node (ref "J1104") (pin "2") (pinfunction "2_2") (pintype "passive"))
      (node (ref "R1103") (pin "2") (pinfunction "2_2") (pintype "passive"))
      (node (ref "S1102") (pin "1") (pinfunction "O_1") (pintype "passive"))
      (node (ref "TP1101") (pin "TP") (pinfunction "TP_TP") (pintype "input"))
      (node (ref "U1101") (pin "1") (pinfunction "VM_1") (pintype "bidirectional"))
      (node (ref "U1101") (pin "11") (pinfunction "MODE_11") (pintype "bidirectional"))
      (node (ref "U1101") (pin "12") (pinfunction "VCC_12") (pintype "bidirectional"))
      (node (ref "U1102") (pin "8") (pinfunction "VCC_8") (pintype "bidirectional"))
    )
    (net (code "191") (name "V_BATT") (class "Default")
      (node (ref "C1102") (pin "2") (pinfunction "2_2") (pintype "passive"))
      (node (ref "C1202") (pin "2") (pinfunction "2_2") (pintype "passive"))
      (node (ref "C1302") (pin "2") (pinfunction "2_2") (pintype "passive"))
      (node (ref "C1501") (pin "2") (pinfunction "2_2") (pintype "passive"))
      (node (ref "C1601") (pin "+") (pinfunction "+_+") (pintype "passive"))
      (node (ref "C1602") (pin "+") (pinfunction "+_+") (pintype "passive"))
      (node (ref "C1603") (pin "+") (pinfunction "+_+") (pintype "passive"))
      (node (ref "C1604") (pin "1") (pinfunction "1_1") (pintype "passive"))
      (node (ref "D1001") (pin "C") (pinfunction "C_C") (pintype "passive"))
      (node (ref "D1401") (pin "C") (pinfunction "C_C") (pintype "passive"))
      (node (ref "D1601") (pin "C") (pinfunction "C_C") (pintype "passive"))
      (node (ref "D201") (pin "C") (pinfunction "C_C") (pintype "passive"))
      (node (ref "D501") (pin "C") (pinfunction "C_C") (pintype "passive"))
      (node (ref "D601") (pin "C") (pinfunction "C_C") (pintype "passive"))
      (node (ref "D801") (pin "C") (pinfunction "C_C") (pintype "passive"))
      (node (ref "D901") (pin "C") (pinfunction "C_C") (pintype "passive"))
      (node (ref "IC1101") (pin "1") (pinfunction "VI_1") (pintype "input"))
      (node (ref "IC1201") (pin "1") (pinfunction "VI_1") (pintype "input"))
      (node (ref "IC1301") (pin "1") (pinfunction "VI_1") (pintype "input"))
      (node (ref "IC1501") (pin "1") (pinfunction "VI_1") (pintype "input"))
      (node (ref "J1001") (pin "1") (pinfunction "1_1") (pintype "passive"))
      (node (ref "J1003") (pin "1") (pinfunction "1_1") (pintype "passive"))
      (node (ref "J1402") (pin "1") (pinfunction "1_1") (pintype "passive"))
      (node (ref "J201") (pin "2") (pinfunction "2_2") (pintype "passive"))
      (node (ref "J202") (pin "1") (pinfunction "1_1") (pintype "passive"))
      (node (ref "J203") (pin "1") (pinfunction "1_1") (pintype "passive"))
      (node (ref "J502") (pin "1") (pinfunction "1_1") (pintype "passive"))
      (node (ref "J602") (pin "1") (pinfunction "1_1") (pintype "passive"))
      (node (ref "J802") (pin "1") (pinfunction "1_1") (pintype "passive"))
      (node (ref "J902") (pin "1") (pinfunction "1_1") (pintype "passive"))
      (node (ref "U1002") (pin "1") (pinfunction "IN_1") (pintype "input"))
      (node (ref "U1002") (pin "3") (pinfunction "EN_3") (pintype "input"))
      (node (ref "U102") (pin "1") (pinfunction "IN_1") (pintype "input"))
      (node (ref "U102") (pin "3") (pinfunction "EN_3") (pintype "input"))
      (node (ref "U1402") (pin "1") (pinfunction "IN_1") (pintype "input"))
      (node (ref "U1402") (pin "3") (pinfunction "EN_3") (pintype "input"))
      (node (ref "U203") (pin "1") (pinfunction "IN_1") (pintype "input"))
      (node (ref "U203") (pin "3") (pinfunction "EN_3") (pintype "input"))
      (node (ref "U304") (pin "1") (pinfunction "IN_1") (pintype "input"))
      (node (ref "U304") (pin "3") (pinfunction "EN_3") (pintype "input"))
      (node (ref "U404") (pin "1") (pinfunction "IN_1") (pintype "input"))
      (node (ref "U404") (pin "3") (pinfunction "EN_3") (pintype "input"))
      (node (ref "U504") (pin "1") (pinfunction "IN_1") (pintype "input"))
      (node (ref "U504") (pin "3") (pinfunction "EN_3") (pintype "input"))
      (node (ref "U604") (pin "1") (pinfunction "IN_1") (pintype "input"))
      (node (ref "U604") (pin "3") (pinfunction "EN_3") (pintype "input"))
      (node (ref "U703") (pin "1") (pinfunction "IN_1") (pintype "input"))
      (node (ref "U703") (pin "3") (pinfunction "EN_3") (pintype "input"))
      (node (ref "U803") (pin "1") (pinfunction "IN_1") (pintype "input"))
      (node (ref "U803") (pin "3") (pinfunction "EN_3") (pintype "input"))
      (node (ref "U902") (pin "1") (pinfunction "IN_1") (pintype "input"))
      (node (ref "U902") (pin "3") (pinfunction "EN_3") (pintype "input"))
      (node (ref "X1601") (pin "1") (pinfunction "1_1") (pintype "passive"))
    )
    (net (code "192") (name "WATER_IN") (class "Default")
      (node (ref "D603") (pin "A") (pinfunction "A_A") (pintype "passive"))
      (node (ref "J1605") (pin "1") (pinfunction "1_1") (pintype "passive"))
      (node (ref "U602") (pin "1") (pinfunction "A_1") (pintype "input"))
    )
    (net (code "193") (name "WATER_MISO") (class "Default")
      (node (ref "J603") (pin "1") (pinfunction "1_1") (pintype "passive"))
      (node (ref "U603") (pin "6") (pinfunction "PB1(MISO)_6") (pintype "bidirectional"))
    )
    (net (code "194") (name "WATER_MOSI") (class "Default")
      (node (ref "J603") (pin "4") (pinfunction "4_4") (pintype "passive"))
      (node (ref "U603") (pin "5") (pinfunction "PB0(MOSI)_5") (pintype "bidirectional"))
    )
    (net (code "195") (name "WATER_OUT") (class "Default")
      (node (ref "D602") (pin "A") (pinfunction "A_A") (pintype "passive"))
      (node (ref "J1606") (pin "2") (pinfunction "2_2") (pintype "passive"))
      (node (ref "S602") (pin "2") (pinfunction "P_2") (pintype "passive"))
      (node (ref "U601") (pin "2") (pinfunction "A_2") (pintype "bidirectional"))
    )
    (net (code "196") (name "WATER_OUT_SWITCH") (class "Default")
      (node (ref "S602") (pin "3") (pinfunction "S_3") (pintype "passive"))
      (node (ref "U603") (pin "3") (pinfunction "PB4(ADC2)_3") (pintype "bidirectional"))
    )
    (net (code "197") (name "WATER_RST") (class "Default")
      (node (ref "J603") (pin "5") (pinfunction "5_5") (pintype "passive"))
      (node (ref "R604") (pin "1") (pinfunction "1_1") (pintype "passive"))
      (node (ref "S601") (pin "3") (pinfunction "2_3") (pintype "passive"))
      (node (ref "S601") (pin "4") (pinfunction "2_4") (pintype "passive"))
      (node (ref "U603") (pin "1") (pinfunction "PB5(NRES)_1") (pintype "bidirectional"))
    )
    (net (code "198") (name "WATER_SCK") (class "Default")
      (node (ref "J601") (pin "1") (pinfunction "1_1") (pintype "passive"))
      (node (ref "J603") (pin "3") (pinfunction "3_3") (pintype "passive"))
      (node (ref "R603") (pin "1") (pinfunction "1_1") (pintype "passive"))
      (node (ref "U603") (pin "7") (pinfunction "PB2(SCK/ADC1)_7") (pintype "bidirectional"))
    )
    (net (code "199") (name "WATER_VCC") (class "Default")
      (node (ref "C601") (pin "2") (pinfunction "2_2") (pintype "passive"))
      (node (ref "C602") (pin "+") (pinfunction "+_+") (pintype "passive"))
      (node (ref "D604") (pin "A") (pinfunction "A_A") (pintype "passive"))
      (node (ref "J603") (pin "2") (pinfunction "2_2") (pintype "passive"))
      (node (ref "R603") (pin "2") (pinfunction "2_2") (pintype "passive"))
      (node (ref "R604") (pin "2") (pinfunction "2_2") (pintype "passive"))
      (node (ref "S602") (pin "1") (pinfunction "O_1") (pintype "passive"))
      (node (ref "TP601") (pin "TP") (pinfunction "TP_TP") (pintype "input"))
      (node (ref "U601") (pin "5") (pinfunction "P$V+_5") (pintype "bidirectional"))
      (node (ref "U602") (pin "5") (pinfunction "VCC_5") (pintype "power_in"))
      (node (ref "U603") (pin "8") (pinfunction "VCC_8") (pintype "bidirectional"))
      (node (ref "U604") (pin "5") (pinfunction "OUT_5") (pintype "passive"))
    )
    (net (code "200") (name "unconnected-(S102-S-Pad3)") (class "Default")
      (node (ref "S102") (pin "3") (pinfunction "S_3") (pintype "passive"))
    )
    (net (code "201") (name "unconnected-(S801-S-Pad3)") (class "Default")
      (node (ref "S801") (pin "3") (pinfunction "S_3") (pintype "passive"))
    )
    (net (code "202") (name "unconnected-(S902-S-Pad3)") (class "Default")
      (node (ref "S902") (pin "3") (pinfunction "S_3") (pintype "passive"))
    )
    (net (code "203") (name "unconnected-(S1002-S-Pad3)") (class "Default")
      (node (ref "S1002") (pin "3") (pinfunction "S_3") (pintype "passive"))
    )
    (net (code "204") (name "unconnected-(S1102-S-Pad3)") (class "Default")
      (node (ref "S1102") (pin "3") (pinfunction "S_3") (pintype "passive"))
    )
    (net (code "205") (name "unconnected-(S1202-S-Pad3)") (class "Default")
      (node (ref "S1202") (pin "3") (pinfunction "S_3") (pintype "passive"))
    )
    (net (code "206") (name "unconnected-(S1302-S-Pad3)") (class "Default")
      (node (ref "S1302") (pin "3") (pinfunction "S_3") (pintype "passive"))
    )
    (net (code "207") (name "unconnected-(S1401-S-Pad3)") (class "Default")
      (node (ref "S1401") (pin "3") (pinfunction "S_3") (pintype "passive"))
    )
    (net (code "208") (name "unconnected-(U102-BP-Pad4)") (class "Default")
      (node (ref "U102") (pin "4") (pinfunction "BP_4") (pintype "input"))
    )
    (net (code "209") (name "unconnected-(U203-BP-Pad4)") (class "Default")
      (node (ref "U203") (pin "4") (pinfunction "BP_4") (pintype "input"))
    )
    (net (code "210") (name "unconnected-(U304-BP-Pad4)") (class "Default")
      (node (ref "U304") (pin "4") (pinfunction "BP_4") (pintype "input"))
    )
    (net (code "211") (name "unconnected-(U404-BP-Pad4)") (class "Default")
      (node (ref "U404") (pin "4") (pinfunction "BP_4") (pintype "input"))
    )
    (net (code "212") (name "unconnected-(U504-BP-Pad4)") (class "Default")
      (node (ref "U504") (pin "4") (pinfunction "BP_4") (pintype "input"))
    )
    (net (code "213") (name "unconnected-(U604-BP-Pad4)") (class "Default")
      (node (ref "U604") (pin "4") (pinfunction "BP_4") (pintype "input"))
    )
    (net (code "214") (name "unconnected-(U703-BP-Pad4)") (class "Default")
      (node (ref "U703") (pin "4") (pinfunction "BP_4") (pintype "input"))
    )
    (net (code "215") (name "unconnected-(U803-BP-Pad4)") (class "Default")
      (node (ref "U803") (pin "4") (pinfunction "BP_4") (pintype "input"))
    )
    (net (code "216") (name "unconnected-(U902-BP-Pad4)") (class "Default")
      (node (ref "U902") (pin "4") (pinfunction "BP_4") (pintype "input"))
    )
    (net (code "217") (name "unconnected-(U1002-BP-Pad4)") (class "Default")
      (node (ref "U1002") (pin "4") (pinfunction "BP_4") (pintype "input"))
    )
    (net (code "218") (name "unconnected-(U1101-BIN1{slash}PH-Pad8)") (class "Default")
      (node (ref "U1101") (pin "8") (pinfunction "BIN1/PH_8") (pintype "bidirectional"))
    )
    (net (code "219") (name "unconnected-(U1101-BIN2{slash}EN-Pad7)") (class "Default")
      (node (ref "U1101") (pin "7") (pinfunction "BIN2/EN_7") (pintype "bidirectional"))
    )
    (net (code "220") (name "unconnected-(U1101-BOUT1-Pad4)") (class "Default")
      (node (ref "U1101") (pin "4") (pinfunction "BOUT1_4") (pintype "bidirectional"))
    )
    (net (code "221") (name "unconnected-(U1101-BOUT2-Pad5)") (class "Default")
      (node (ref "U1101") (pin "5") (pinfunction "BOUT2_5") (pintype "bidirectional"))
    )
    (net (code "222") (name "unconnected-(U1201-BIN1{slash}PH-Pad8)") (class "Default")
      (node (ref "U1201") (pin "8") (pinfunction "BIN1/PH_8") (pintype "bidirectional"))
    )
    (net (code "223") (name "unconnected-(U1201-BIN2{slash}EN-Pad7)") (class "Default")
      (node (ref "U1201") (pin "7") (pinfunction "BIN2/EN_7") (pintype "bidirectional"))
    )
    (net (code "224") (name "unconnected-(U1201-BOUT1-Pad4)") (class "Default")
      (node (ref "U1201") (pin "4") (pinfunction "BOUT1_4") (pintype "bidirectional"))
    )
    (net (code "225") (name "unconnected-(U1201-BOUT2-Pad5)") (class "Default")
      (node (ref "U1201") (pin "5") (pinfunction "BOUT2_5") (pintype "bidirectional"))
    )
    (net (code "226") (name "unconnected-(U1301-BIN1{slash}PH-Pad8)") (class "Default")
      (node (ref "U1301") (pin "8") (pinfunction "BIN1/PH_8") (pintype "bidirectional"))
    )
    (net (code "227") (name "unconnected-(U1301-BIN2{slash}EN-Pad7)") (class "Default")
      (node (ref "U1301") (pin "7") (pinfunction "BIN2/EN_7") (pintype "bidirectional"))
    )
    (net (code "228") (name "unconnected-(U1301-BOUT1-Pad4)") (class "Default")
      (node (ref "U1301") (pin "4") (pinfunction "BOUT1_4") (pintype "bidirectional"))
    )
    (net (code "229") (name "unconnected-(U1301-BOUT2-Pad5)") (class "Default")
      (node (ref "U1301") (pin "5") (pinfunction "BOUT2_5") (pintype "bidirectional"))
    )
    (net (code "230") (name "unconnected-(U1402-BP-Pad4)") (class "Default")
      (node (ref "U1402") (pin "4") (pinfunction "BP_4") (pintype "input"))
    )
  )
)
